# Pinscape_Pico_-_Pro_SMD_Expansion_Board.net
KiCad netlist of a schematic drawn in EAGLE
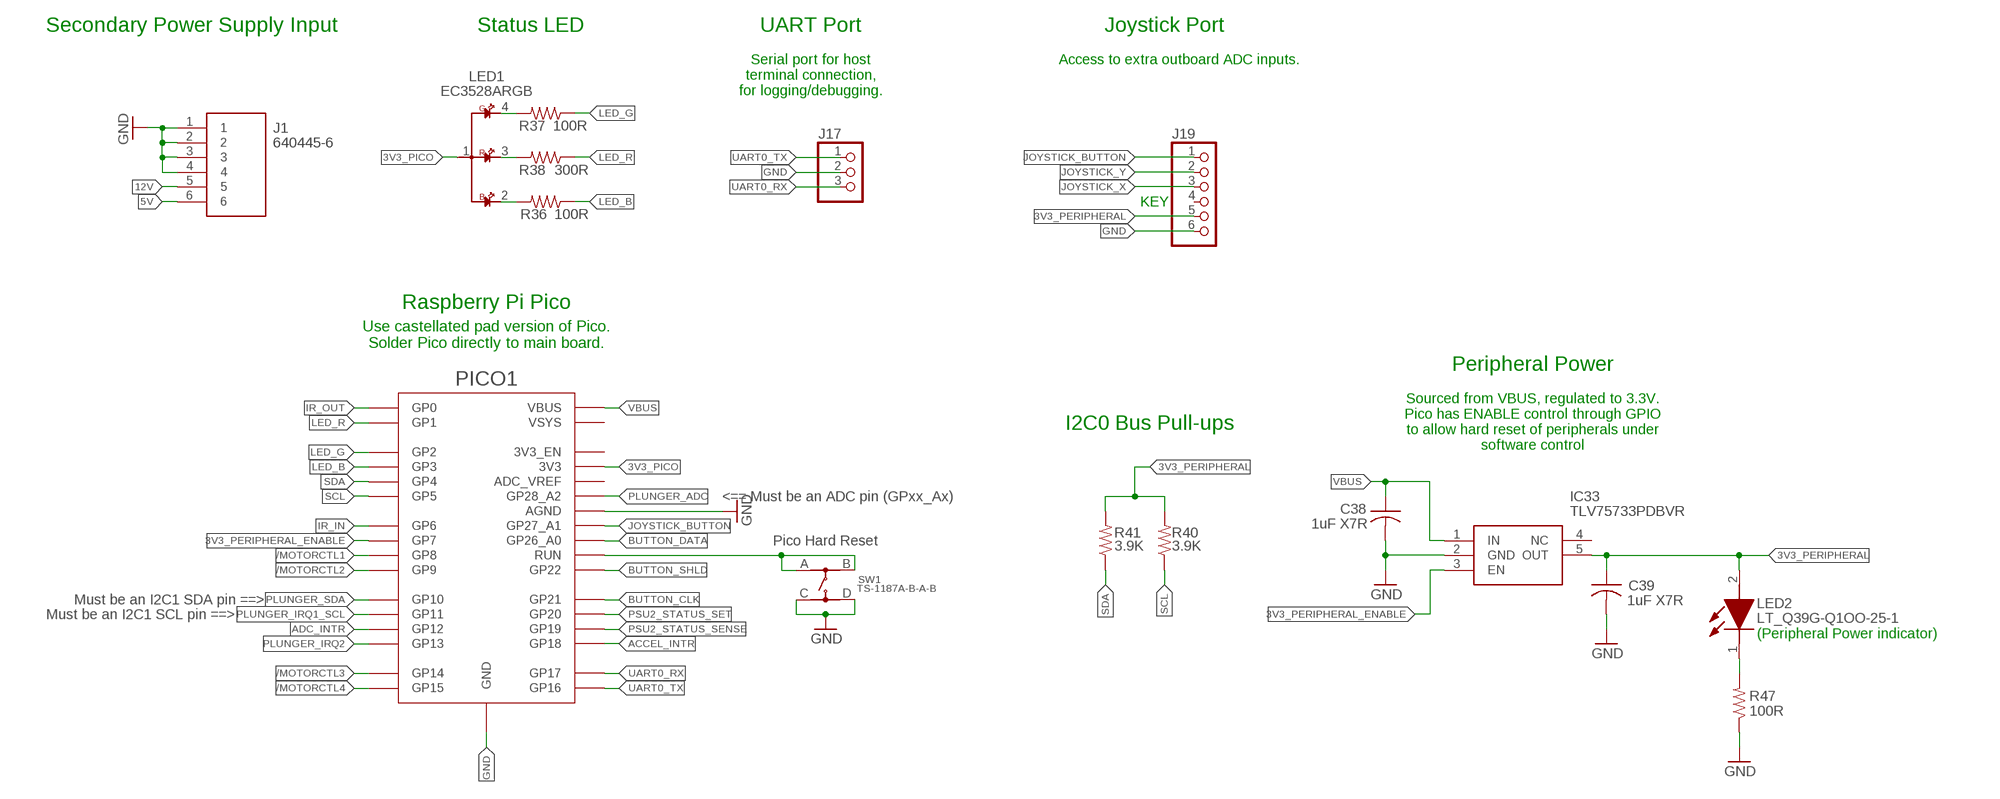
[diagram p0: schematic, sheet 1]
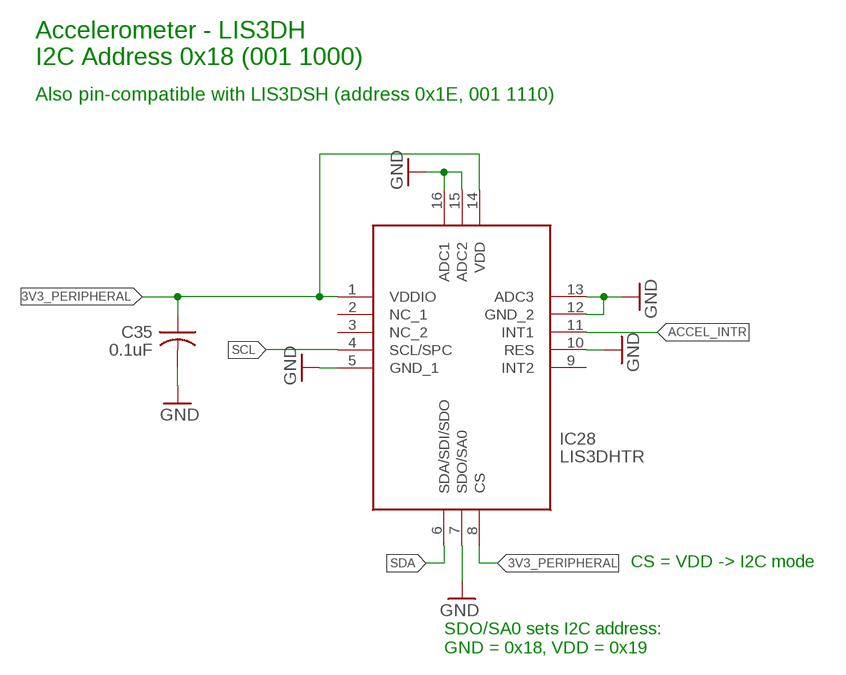
[diagram p1: schematic, sheet 2]
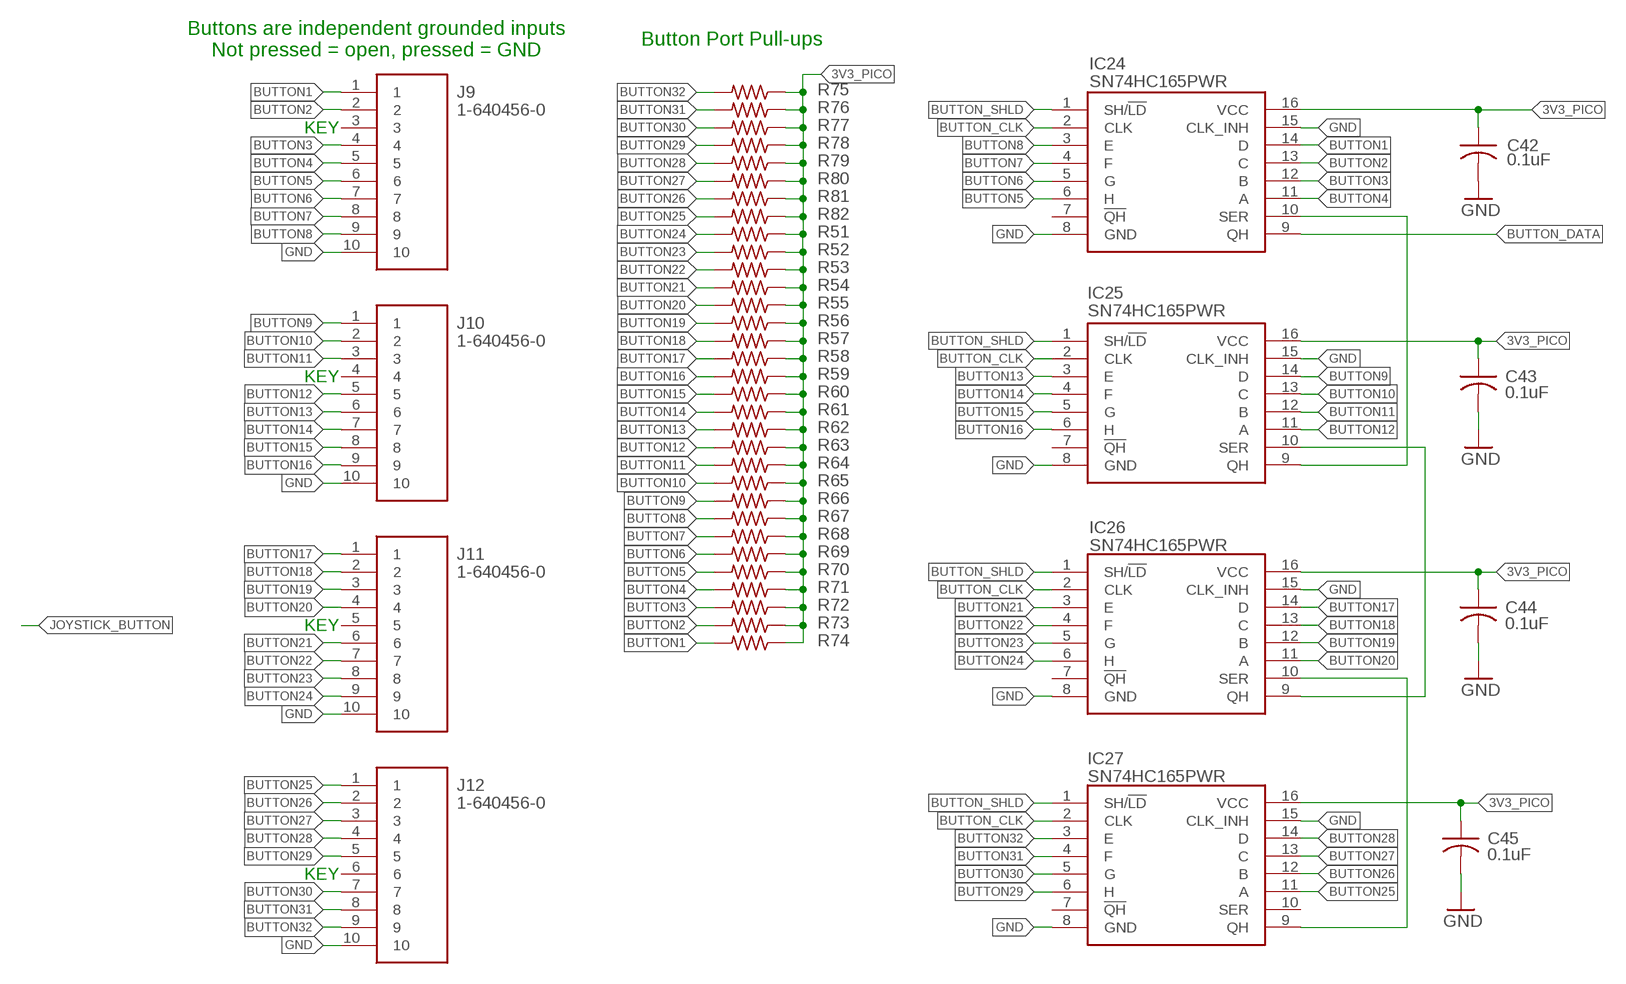
[diagram p2: schematic, sheet 3]
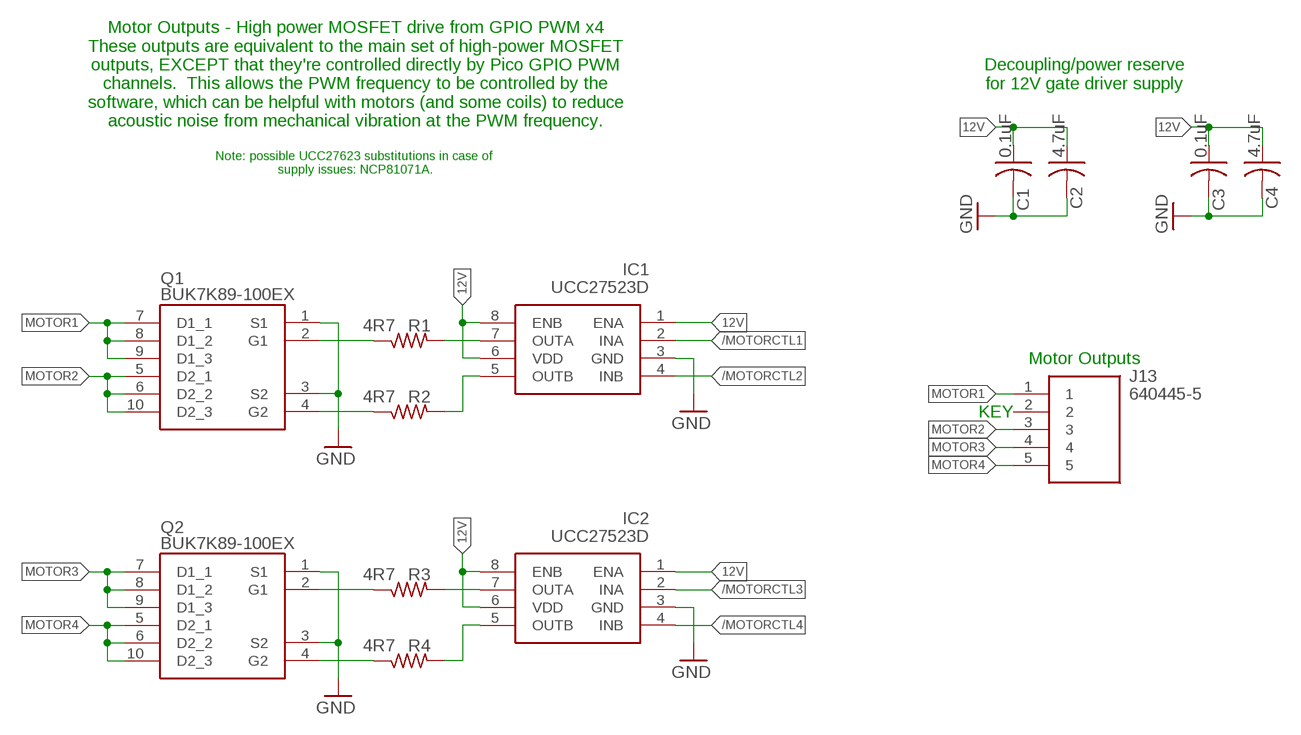
[diagram p3: schematic, sheet 4]
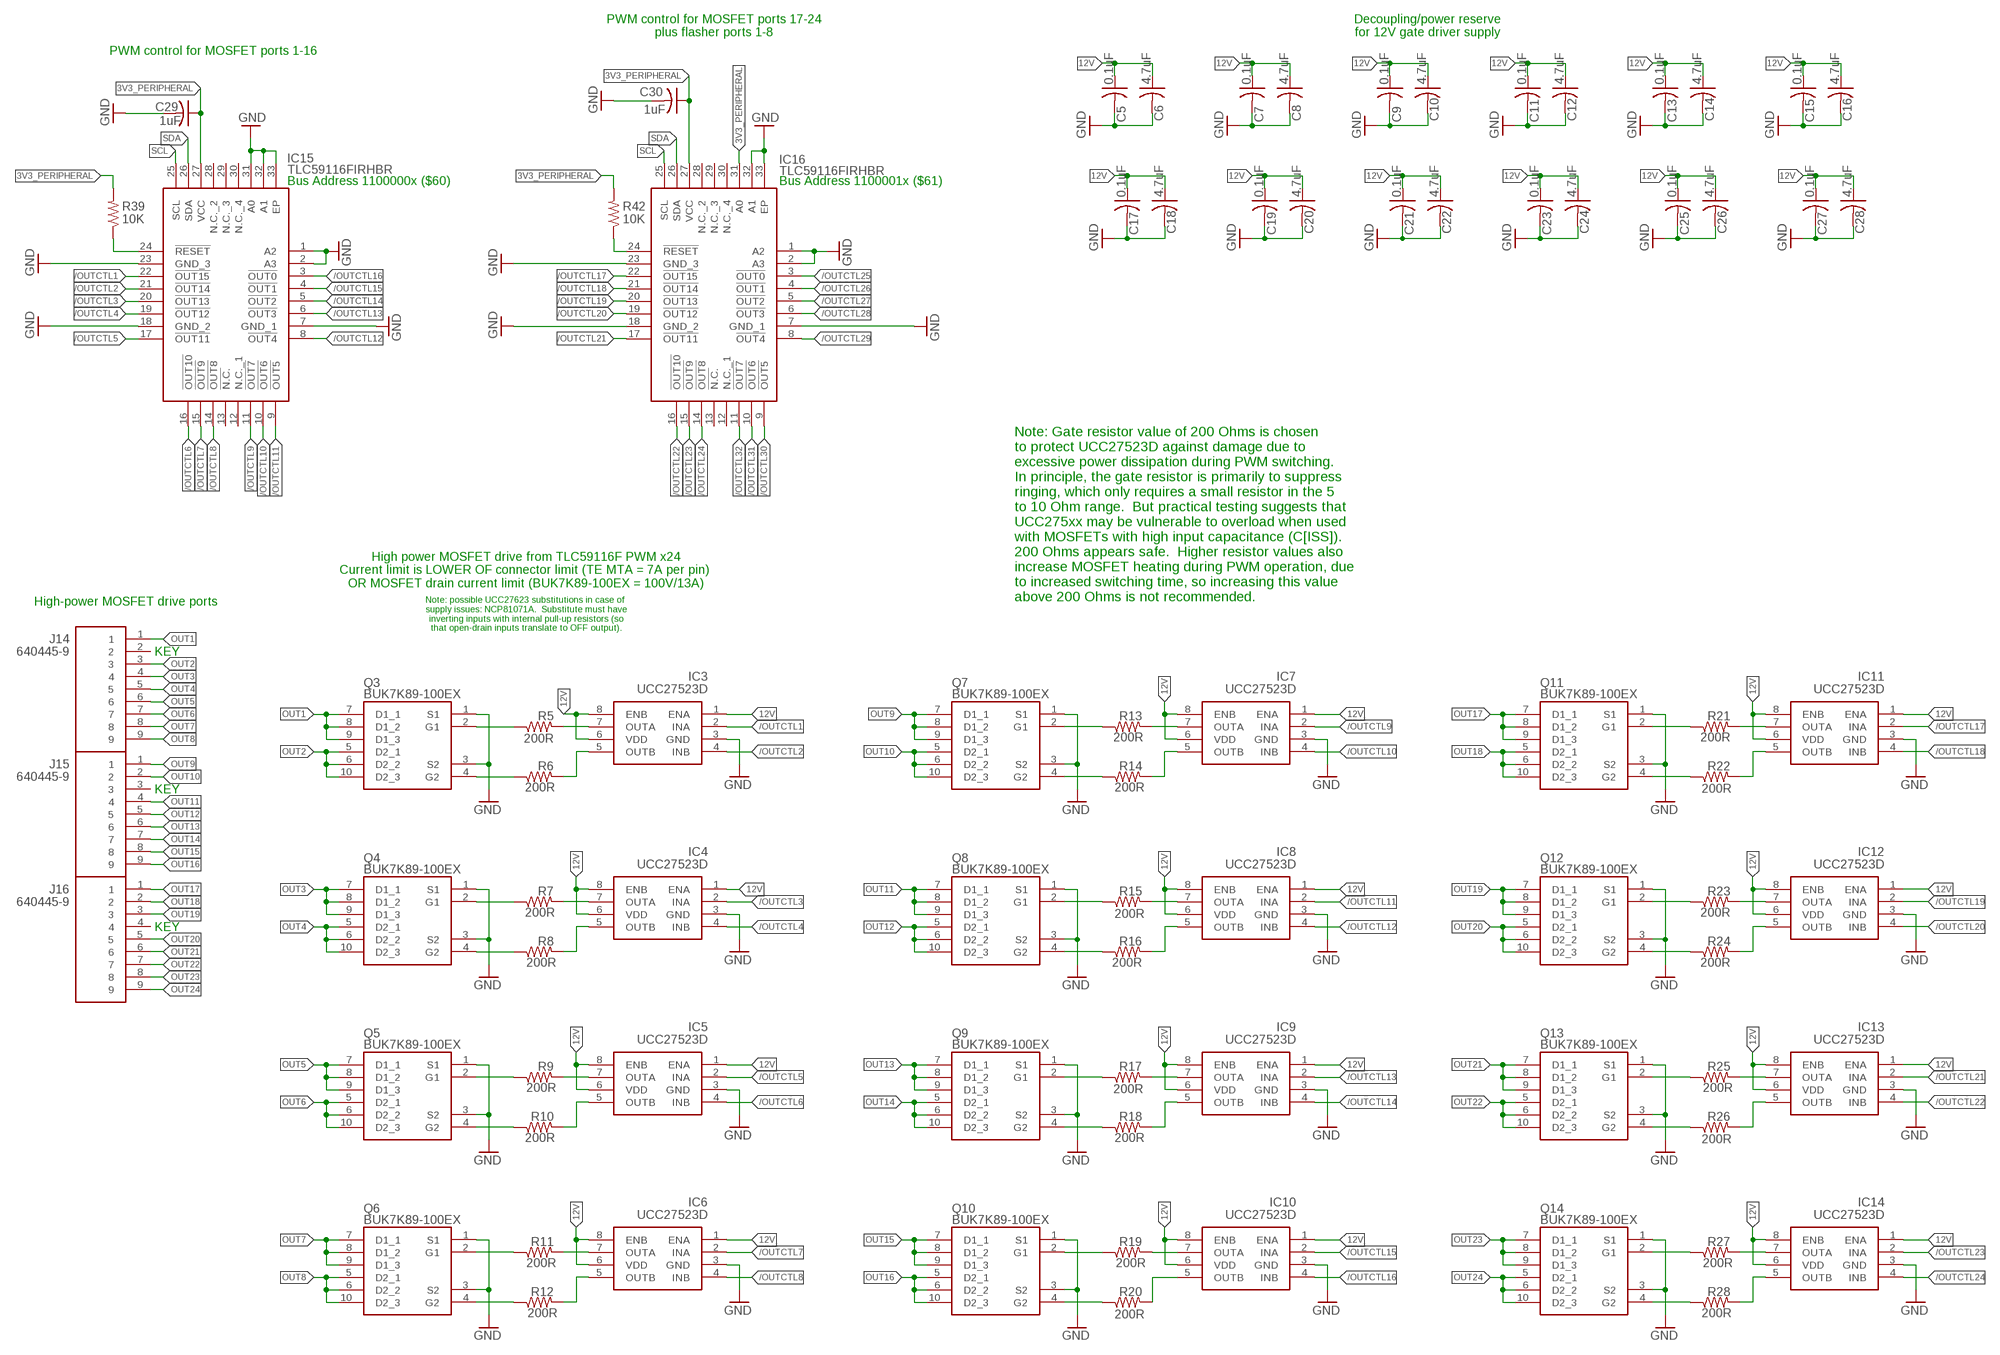
[diagram p4: schematic, sheet 5]
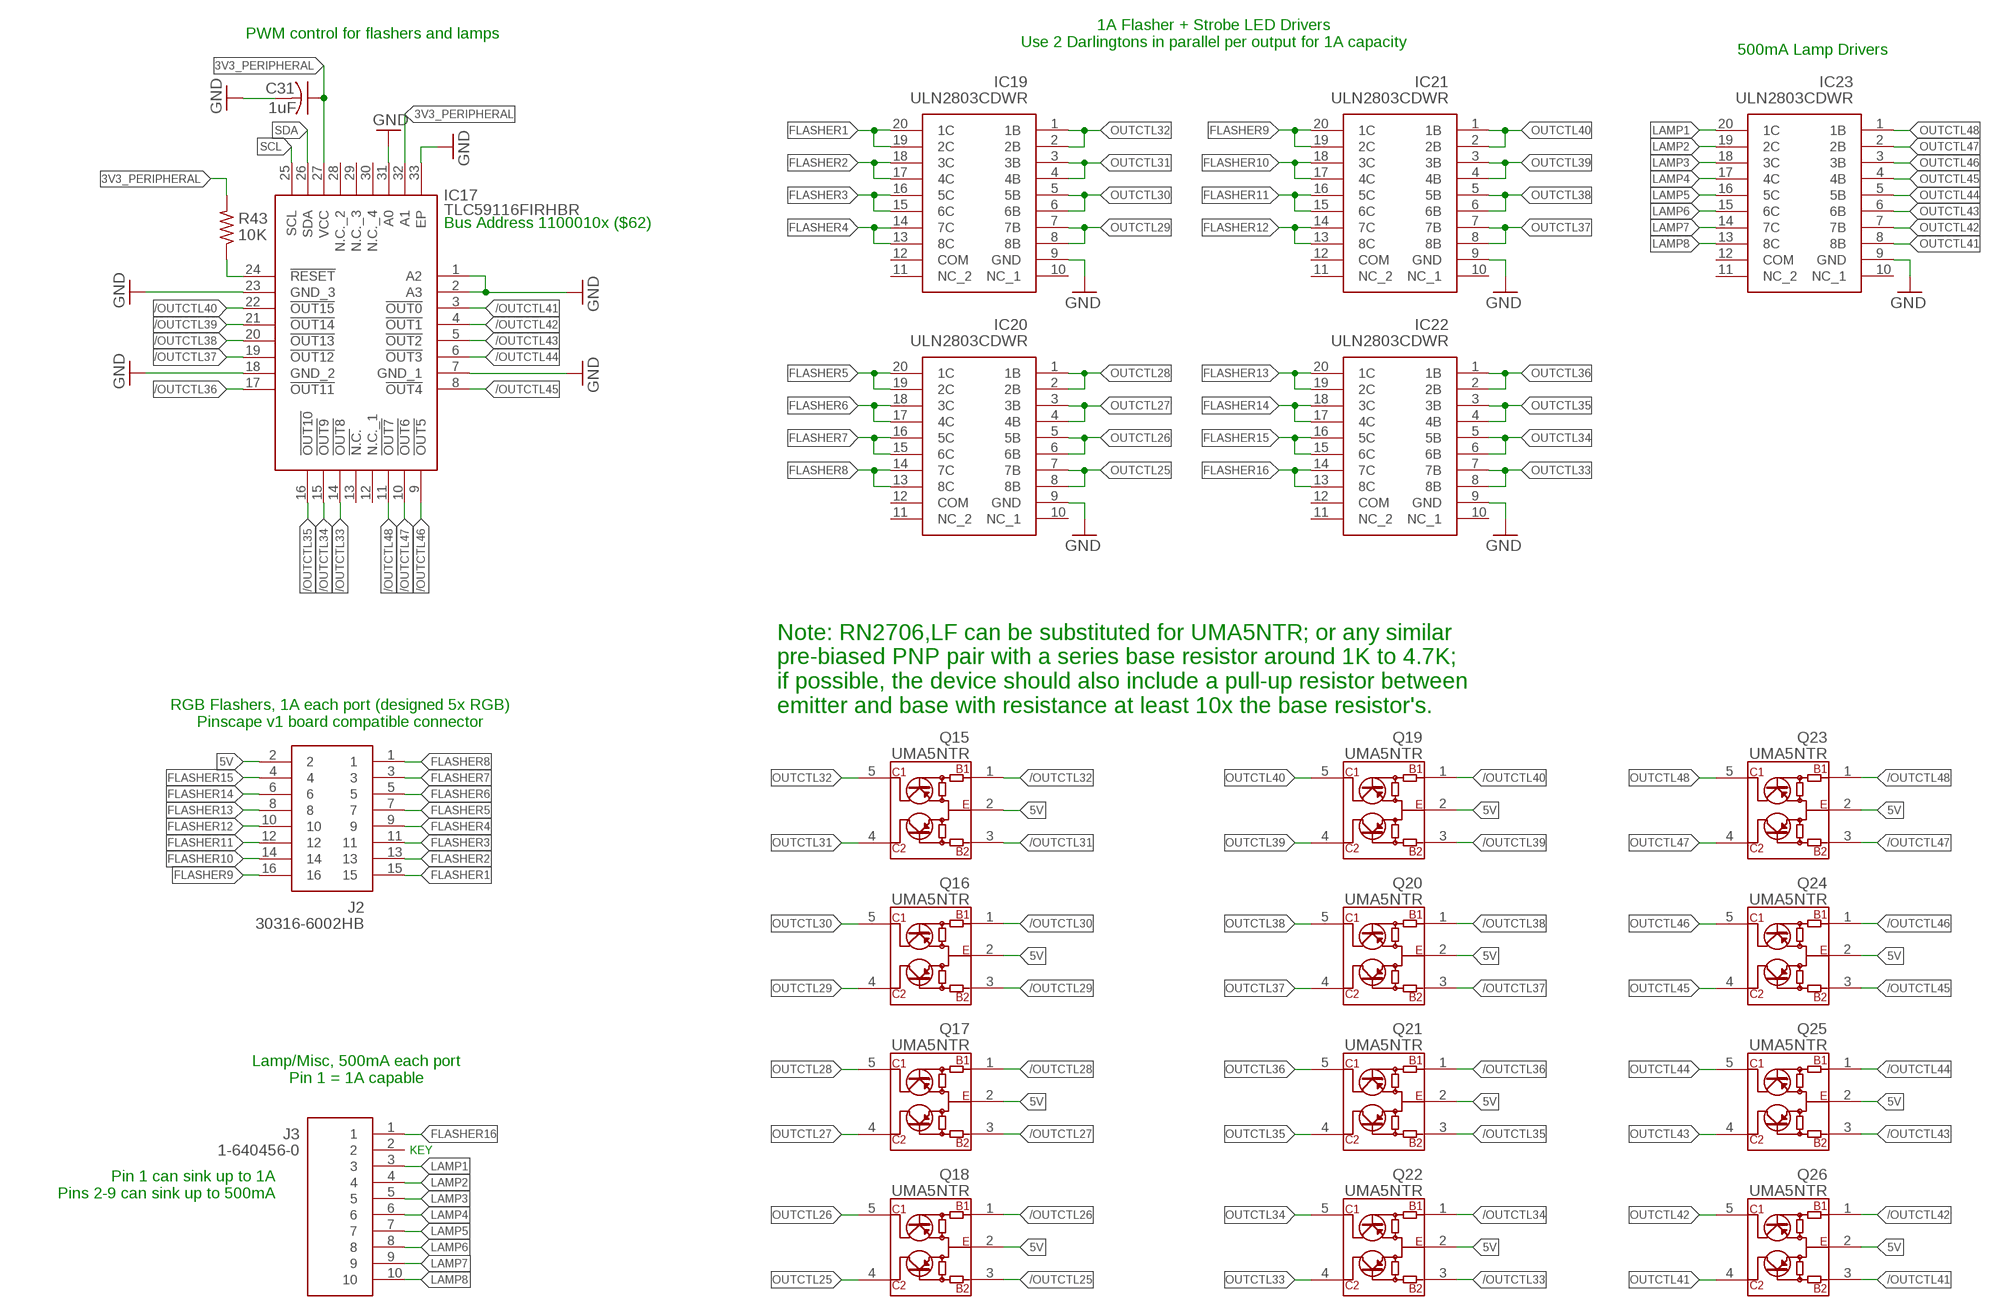
[diagram p5: schematic, sheet 6]
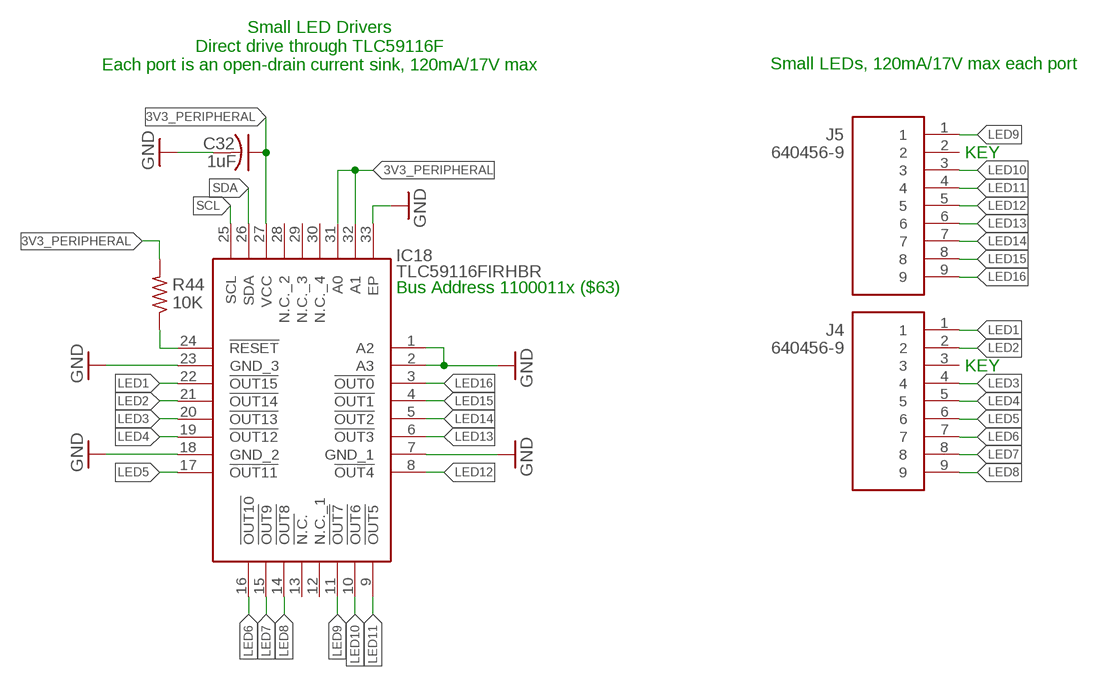
[diagram p6: schematic, sheet 7]
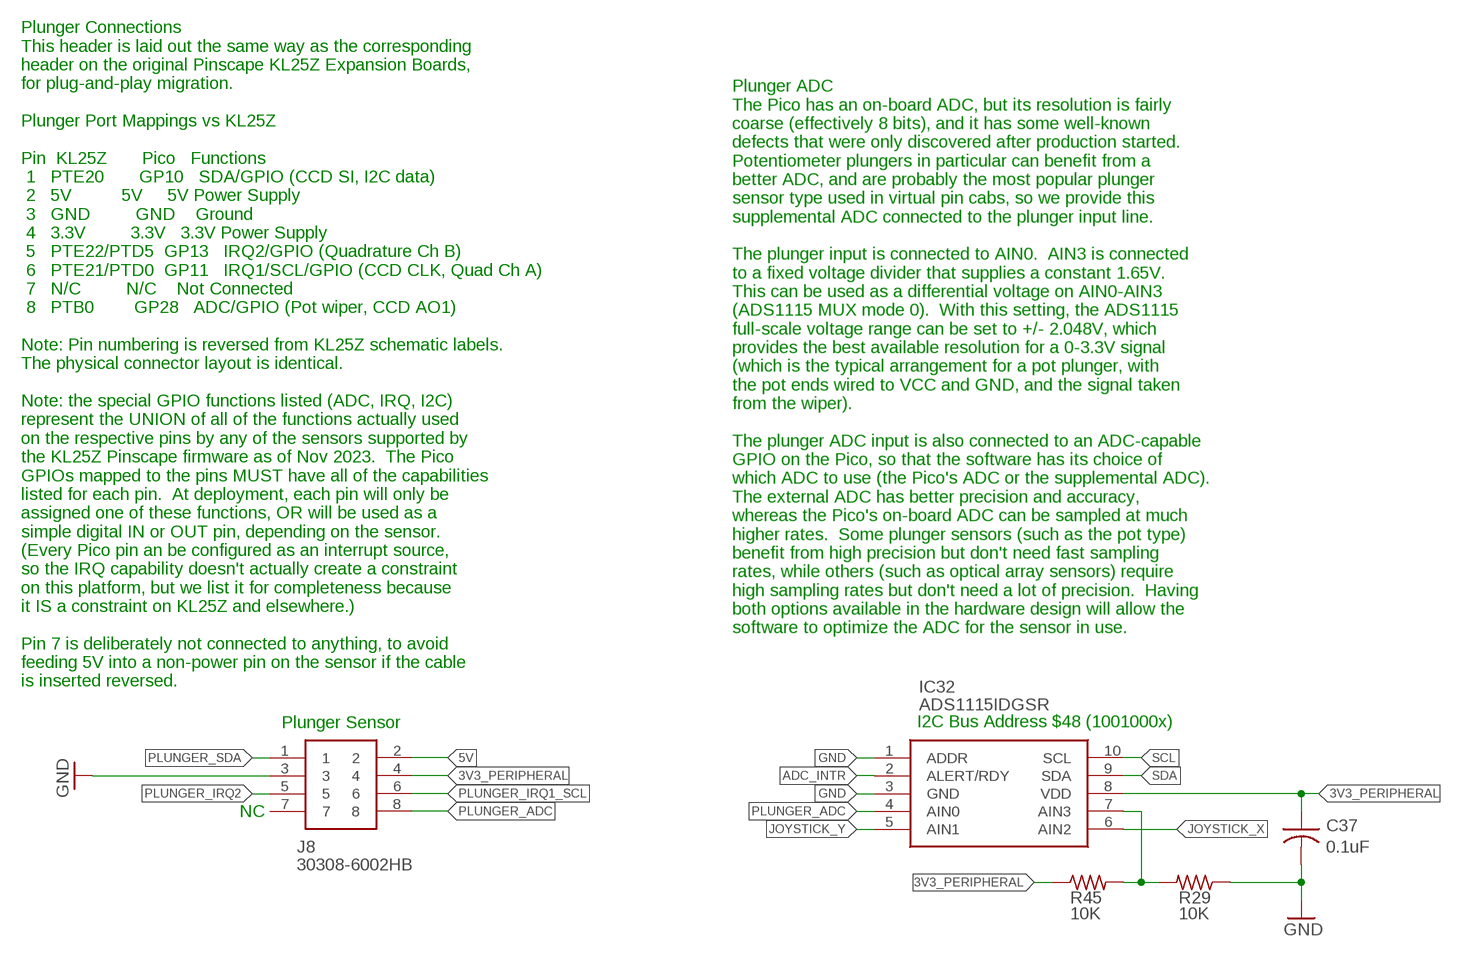
[diagram p7: schematic, sheet 8]
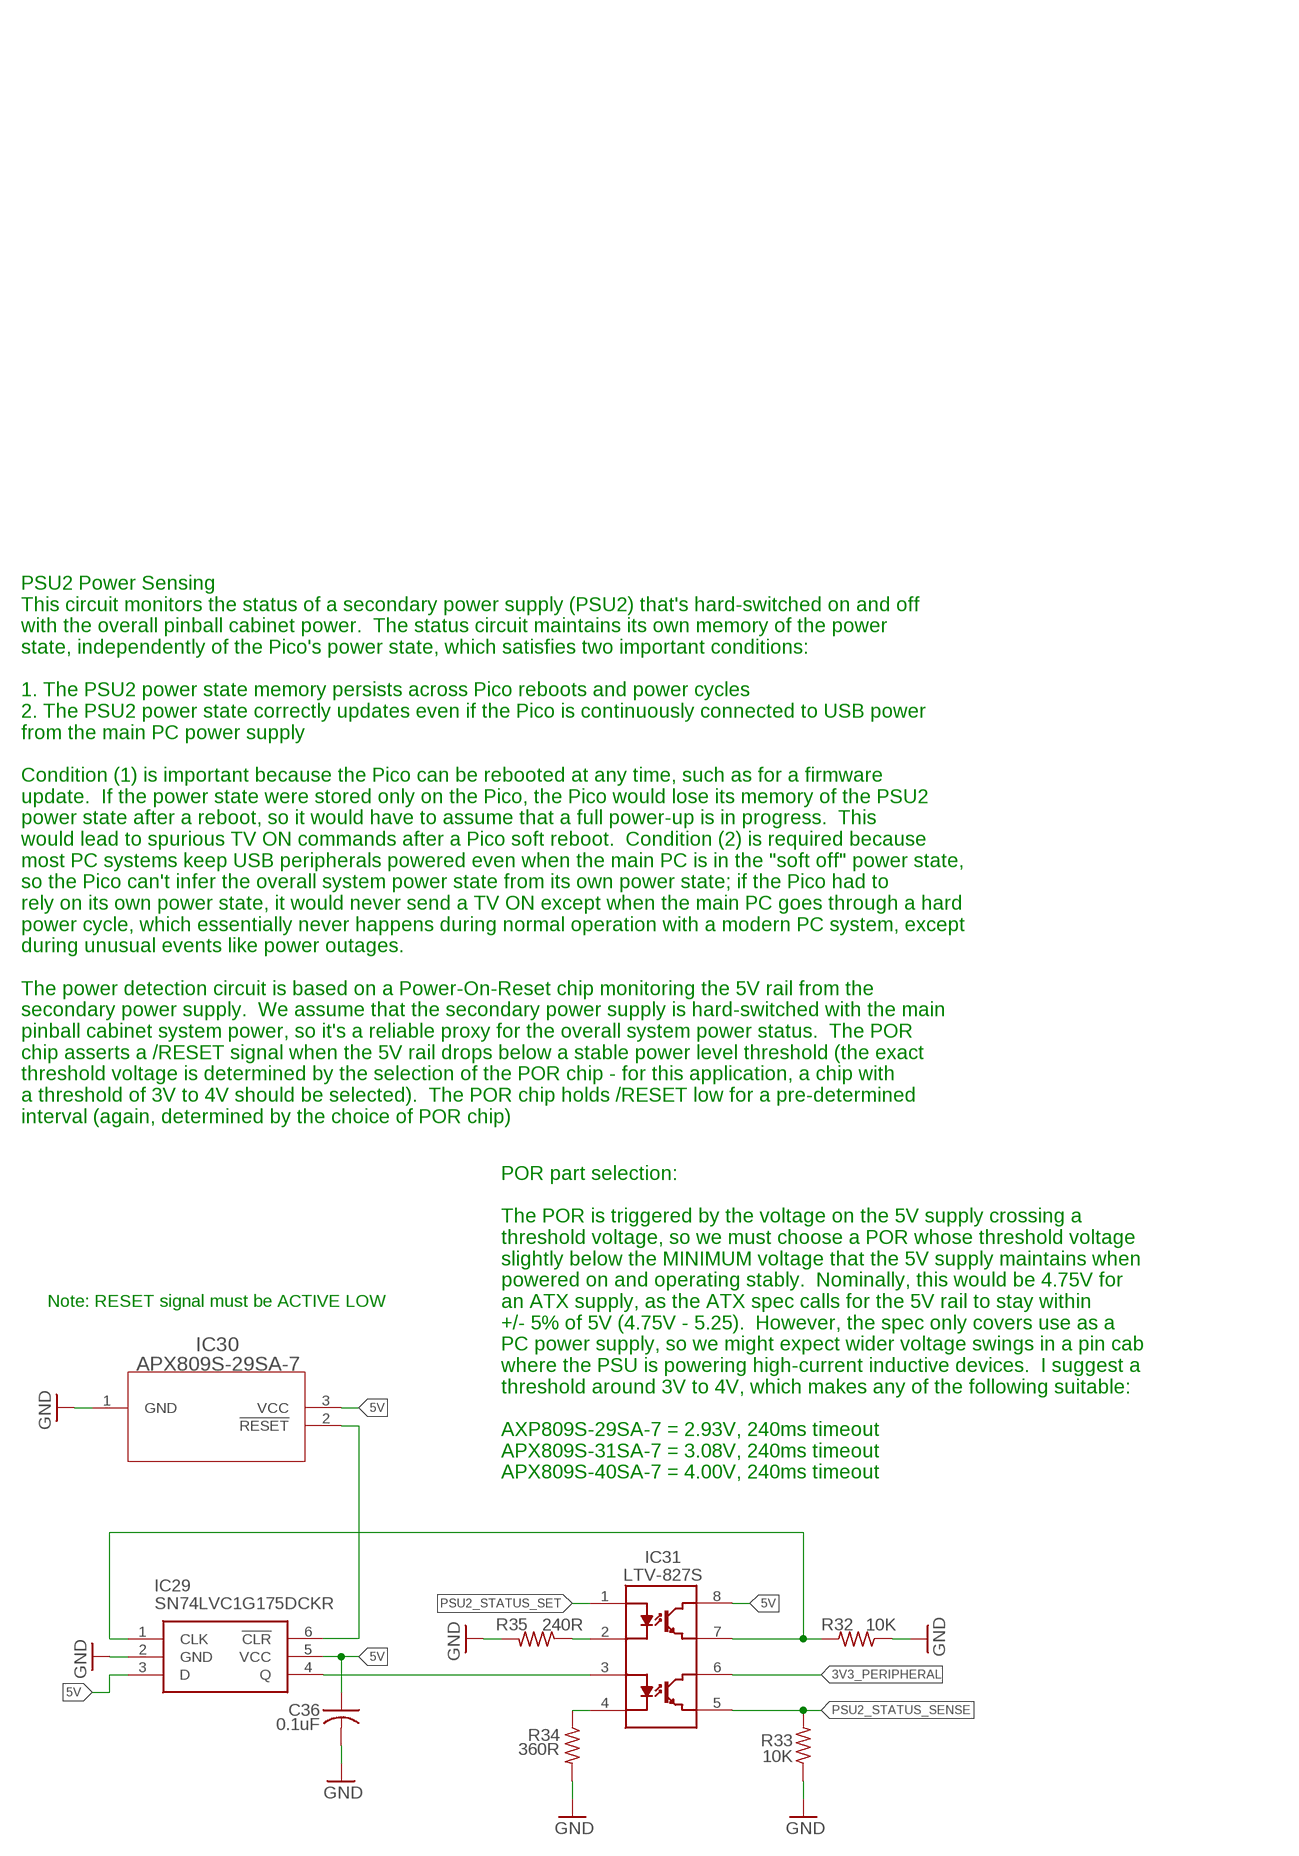
[diagram p8: schematic, sheet 9]
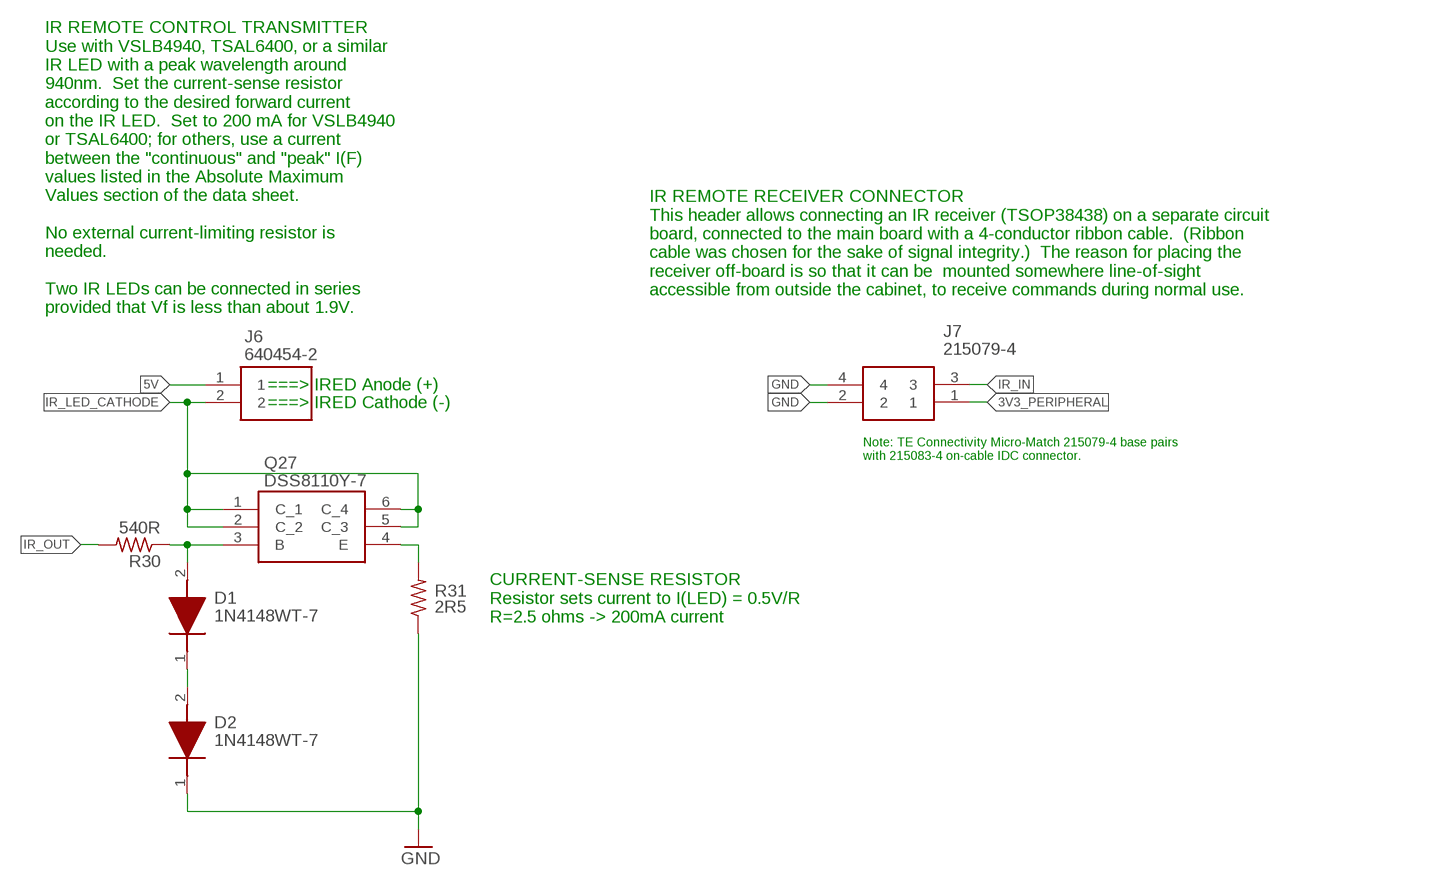
[diagram p9: schematic, sheet 10]
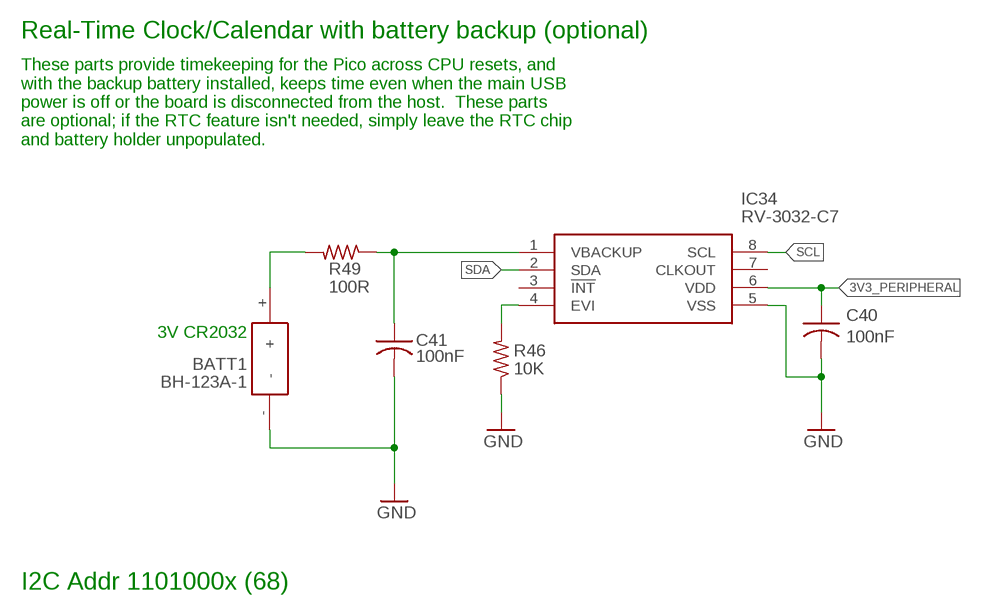
[diagram p10: schematic, sheet 11]
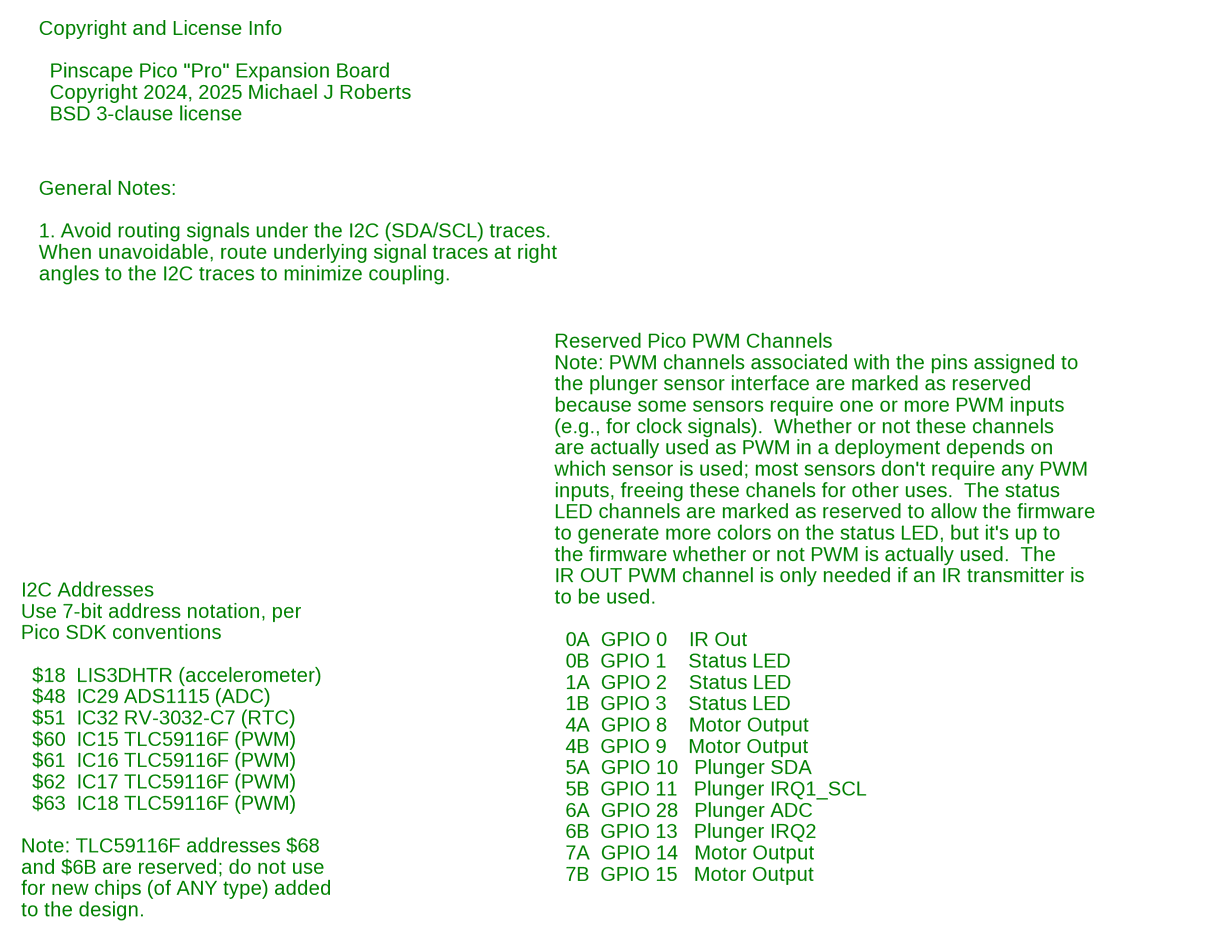
[diagram p11: schematic, sheet 12]

(export (version "E")
  (design (tool "Eeschema 10.0.6"))
  (components
    (comp (ref "C31")
      (value "1uF")
      (footprint "eagle-import:C0402")
      (libsource (lib "eagle-import") (part "C-USC0402"))
    )
    (comp (ref "IC17")
      (value "TLC59116FIRHBR")
      (footprint "eagle-import:QFN50P500X500X100-33N")
      (fields (field (name "MOUSER_PART_NUMBER") "595-TLC59116FIRHBR"))
      (libsource (lib "eagle-import") (part "TLC59116FIRHBR"))
    )
    (comp (ref "IC19")
      (value "ULN2803CDWR")
      (footprint "eagle-import:SOIC127P1030X265-20N")
      (fields (field (name "MOUSER_PART_NUMBER") "595-ULN2803CDWR"))
      (libsource (lib "eagle-import") (part "ULN2803CDWR"))
    )
    (comp (ref "IC20")
      (value "ULN2803CDWR")
      (footprint "eagle-import:SOIC127P1030X265-20N")
      (fields (field (name "MOUSER_PART_NUMBER") "595-ULN2803CDWR"))
      (libsource (lib "eagle-import") (part "ULN2803CDWR"))
    )
    (comp (ref "IC21")
      (value "ULN2803CDWR")
      (footprint "eagle-import:SOIC127P1030X265-20N")
      (fields (field (name "MOUSER_PART_NUMBER") "595-ULN2803CDWR"))
      (libsource (lib "eagle-import") (part "ULN2803CDWR"))
    )
    (comp (ref "IC22")
      (value "ULN2803CDWR")
      (footprint "eagle-import:SOIC127P1030X265-20N")
      (fields (field (name "MOUSER_PART_NUMBER") "595-ULN2803CDWR"))
      (libsource (lib "eagle-import") (part "ULN2803CDWR"))
    )
    (comp (ref "IC23")
      (value "ULN2803CDWR")
      (footprint "eagle-import:SOIC127P1030X265-20N")
      (fields (field (name "MOUSER_PART_NUMBER") "595-ULN2803CDWR"))
      (libsource (lib "eagle-import") (part "ULN2803CDWR"))
    )
    (comp (ref "J2")
      (value "30316-6002HB")
      (footprint "eagle-import:3M-30316-6002HB")
      (fields (field (name "MOUSER_PART_NUMBER") "517-30316-6002"))
      (libsource (lib "eagle-import") (part "30316-6002HB"))
    )
    (comp (ref "J3")
      (value "1-640456-0")
      (footprint "eagle-import:SHDR10W66P0X254_1X10_2540X572X")
      (fields (field (name "MOUSER_PART_NUMBER") "571-16404560"))
      (libsource (lib "eagle-import") (part "1-640456-0"))
    )
    (comp (ref "Q15")
      (value "UMA5NTR")
      (footprint "eagle-import:SOT65P210X100-5N")
      (fields (field (name "MOUSER_PART_NUMBER") "755-UMA5NTR"))
      (libsource (lib "eagle-import") (part "UMA5NTR"))
    )
    (comp (ref "Q16")
      (value "UMA5NTR")
      (footprint "eagle-import:SOT65P210X100-5N")
      (fields (field (name "MOUSER_PART_NUMBER") "755-UMA5NTR"))
      (libsource (lib "eagle-import") (part "UMA5NTR"))
    )
    (comp (ref "Q17")
      (value "UMA5NTR")
      (footprint "eagle-import:SOT65P210X100-5N")
      (fields (field (name "MOUSER_PART_NUMBER") "755-UMA5NTR"))
      (libsource (lib "eagle-import") (part "UMA5NTR"))
    )
    (comp (ref "Q18")
      (value "UMA5NTR")
      (footprint "eagle-import:SOT65P210X100-5N")
      (fields (field (name "MOUSER_PART_NUMBER") "755-UMA5NTR"))
      (libsource (lib "eagle-import") (part "UMA5NTR"))
    )
    (comp (ref "Q19")
      (value "UMA5NTR")
      (footprint "eagle-import:SOT65P210X100-5N")
      (fields (field (name "MOUSER_PART_NUMBER") "755-UMA5NTR"))
      (libsource (lib "eagle-import") (part "UMA5NTR"))
    )
    (comp (ref "Q20")
      (value "UMA5NTR")
      (footprint "eagle-import:SOT65P210X100-5N")
      (fields (field (name "MOUSER_PART_NUMBER") "755-UMA5NTR"))
      (libsource (lib "eagle-import") (part "UMA5NTR"))
    )
    (comp (ref "Q21")
      (value "UMA5NTR")
      (footprint "eagle-import:SOT65P210X100-5N")
      (fields (field (name "MOUSER_PART_NUMBER") "755-UMA5NTR"))
      (libsource (lib "eagle-import") (part "UMA5NTR"))
    )
    (comp (ref "Q22")
      (value "UMA5NTR")
      (footprint "eagle-import:SOT65P210X100-5N")
      (fields (field (name "MOUSER_PART_NUMBER") "755-UMA5NTR"))
      (libsource (lib "eagle-import") (part "UMA5NTR"))
    )
    (comp (ref "Q23")
      (value "UMA5NTR")
      (footprint "eagle-import:SOT65P210X100-5N")
      (fields (field (name "MOUSER_PART_NUMBER") "755-UMA5NTR"))
      (libsource (lib "eagle-import") (part "UMA5NTR"))
    )
    (comp (ref "Q24")
      (value "UMA5NTR")
      (footprint "eagle-import:SOT65P210X100-5N")
      (fields (field (name "MOUSER_PART_NUMBER") "755-UMA5NTR"))
      (libsource (lib "eagle-import") (part "UMA5NTR"))
    )
    (comp (ref "Q25")
      (value "UMA5NTR")
      (footprint "eagle-import:SOT65P210X100-5N")
      (fields (field (name "MOUSER_PART_NUMBER") "755-UMA5NTR"))
      (libsource (lib "eagle-import") (part "UMA5NTR"))
    )
    (comp (ref "Q26")
      (value "UMA5NTR")
      (footprint "eagle-import:SOT65P210X100-5N")
      (fields (field (name "MOUSER_PART_NUMBER") "755-UMA5NTR"))
      (libsource (lib "eagle-import") (part "UMA5NTR"))
    )
    (comp (ref "R43")
      (value "10K")
      (footprint "eagle-import:R0402")
      (libsource (lib "eagle-import") (part "resistor_R-US_R0402"))
    )
    (comp (ref "D1")
      (value "1N4148WT-7")
      (footprint "eagle-import:1N4148WT7")
      (fields (field (name "MOUSER_PART_NUMBER") "621-1N4148WT"))
      (libsource (lib "eagle-import") (part "1N4148WT-7"))
    )
    (comp (ref "D2")
      (value "1N4148WT-7")
      (footprint "eagle-import:1N4148WT7")
      (fields (field (name "MOUSER_PART_NUMBER") "621-1N4148WT"))
      (libsource (lib "eagle-import") (part "1N4148WT-7"))
    )
    (comp (ref "J6")
      (value "640454-2")
      (footprint "eagle-import:HDRV2W66P0X254_1X2_762X572X100")
      (fields (field (name "MOUSER_PART_NUMBER") "571-640454-2"))
      (libsource (lib "eagle-import") (part "640454-2"))
    )
    (comp (ref "J7")
      (value "215079-4")
      (footprint "eagle-import:2150794")
      (fields (field (name "MOUSER_PART_NUMBER") "571-215079-4"))
      (libsource (lib "eagle-import") (part "215079-4"))
    )
    (comp (ref "Q27")
      (value "DSS8110Y-7")
      (footprint "eagle-import:SOT65P210X110-6N")
      (fields (field (name "MOUSER_PART_NUMBER") "621-DSS8110Y-7"))
      (libsource (lib "eagle-import") (part "DSS8110Y-7"))
    )
    (comp (ref "R30")
      (value "540R")
      (footprint "eagle-import:R0402")
      (libsource (lib "eagle-import") (part "resistor_R-US_R0402"))
    )
    (comp (ref "R31")
      (value "2R5")
      (footprint "eagle-import:R0603")
      (libsource (lib "eagle-import") (part "R-US_R0603"))
    )
    (comp (ref "C37")
      (value "0.1uF")
      (footprint "eagle-import:C0402")
      (libsource (lib "eagle-import") (part "C-USC0402"))
    )
    (comp (ref "IC32")
      (value "ADS1115IDGSR")
      (footprint "eagle-import:SOP50P490X110-10N")
      (fields (field (name "MOUSER_PART_NUMBER") "595-ADS1115IDGSR"))
      (libsource (lib "eagle-import") (part "ADS1115IDGSR"))
    )
    (comp (ref "J8")
      (value "30308-6002HB")
      (footprint "eagle-import:SHDR8W69P254_2X4_1780X878X955P")
      (libsource (lib "eagle-import") (part "30308-6002HB"))
    )
    (comp (ref "R29")
      (value "10K")
      (footprint "eagle-import:R0603")
      (libsource (lib "eagle-import") (part "resistor_R-US_R0603"))
    )
    (comp (ref "R45")
      (value "10K")
      (footprint "eagle-import:R0603")
      (libsource (lib "eagle-import") (part "resistor_R-US_R0603"))
    )
    (comp (ref "C36")
      (value "0.1uF")
      (footprint "eagle-import:C0402")
      (libsource (lib "eagle-import") (part "C-USC0402"))
    )
    (comp (ref "IC29")
      (value "SN74LVC1G175DCKR")
      (footprint "eagle-import:SOP65P210X110-6N")
      (fields (field (name "MOUSER_PART_NUMBER") "595-SN74LVC1G175DCKR"))
      (libsource (lib "eagle-import") (part "SN74LVC1G175DCKR"))
    )
    (comp (ref "IC30")
      (value "APX809S-29SA-7")
      (footprint "eagle-import:SOT23_DIO")
      (fields
        (field (name "MANUFACTURER_PART_NUMBER") "APX809S-40SA-7")
        (field (name "MANUFACTURER_PART_NUMBER_1") "APX809S-40SA-7")
        (field (name "COPYRIGHT") "Copyright (C) 2023 Ultra Librarian. All rights reserved.")
      )
      (libsource (lib "eagle-import") (part "APX809S-40SA-7"))
    )
    (comp (ref "IC31")
      (value "LTV-827S")
      (footprint "eagle-import:SOP254P1016X460-8N")
      (fields (field (name "MOUSER_PART_NUMBER") "859-LTV-827S"))
      (libsource (lib "eagle-import") (part "LTV-827S"))
    )
    (comp (ref "R32")
      (value "10K")
      (footprint "eagle-import:R0402")
      (fields (field (name "PARTNO") "660-MS1/4DCT52R1002"))
      (libsource (lib "eagle-import") (part "resistor_R-US_R0402"))
    )
    (comp (ref "R33")
      (value "10K")
      (footprint "eagle-import:R0402")
      (fields (field (name "PARTNO") "660-MS1/4DCT52R1002"))
      (libsource (lib "eagle-import") (part "resistor_R-US_R0402"))
    )
    (comp (ref "R34")
      (value "360R")
      (footprint "eagle-import:R0402")
      (fields (field (name "PARTNO") "660-MS1/4DCT52R1002"))
      (libsource (lib "eagle-import") (part "resistor_R-US_R0402"))
    )
    (comp (ref "R35")
      (value "240R")
      (footprint "eagle-import:R0402")
      (fields (field (name "PARTNO") "594-SFR16S0005600FR5"))
      (libsource (lib "eagle-import") (part "resistor_R-US_R0402"))
    )
    (comp (ref "BATT1")
      (value "BH-123A-1")
      (footprint "eagle-import:BH-123A-1")
      (libsource (lib "eagle-import") (part "BH-123A-1"))
    )
    (comp (ref "C40")
      (value "100nF")
      (footprint "eagle-import:C0402")
      (libsource (lib "eagle-import") (part "C-USC0402"))
    )
    (comp (ref "C41")
      (value "100nF")
      (footprint "eagle-import:C0402")
      (libsource (lib "eagle-import") (part "C-USC0402"))
    )
    (comp (ref "IC34")
      (value "RV-3032-C7")
      (footprint "eagle-import:RV3032C7")
      (fields (field (name "MANUFACTURER_PART_NUMBER") "RV-3032-C7 32.768KHZ-2.5PPM-TA-QC"))
      (libsource (lib "eagle-import") (part "RV-3032-C7_32.768KHZ-2.5PPM-TA"))
    )
    (comp (ref "R46")
      (value "10K")
      (footprint "eagle-import:R0402")
      (libsource (lib "eagle-import") (part "resistor_R-US_R0402"))
    )
    (comp (ref "R49")
      (value "100R")
      (footprint "eagle-import:R0402")
      (libsource (lib "eagle-import") (part "resistor_R-US_R0402"))
    )
    (comp (ref "C1")
      (value "0.1uF")
      (footprint "eagle-import:C0402")
      (libsource (lib "eagle-import") (part "resistor_C-USC0402"))
    )
    (comp (ref "C2")
      (value "4.7uF")
      (footprint "eagle-import:C1206")
      (libsource (lib "eagle-import") (part "resistor_C-USC1206"))
    )
    (comp (ref "C3")
      (value "0.1uF")
      (footprint "eagle-import:C0402")
      (libsource (lib "eagle-import") (part "resistor_C-USC0402"))
    )
    (comp (ref "C4")
      (value "4.7uF")
      (footprint "eagle-import:C1206")
      (libsource (lib "eagle-import") (part "resistor_C-USC1206"))
    )
    (comp (ref "IC1")
      (value "UCC27523D")
      (footprint "eagle-import:SOIC127P600X175-8N")
      (fields
        (field (name "MANUFACTURER_PART_NUMBER") "UCC27523DR")
        (field (name "MOUSER_PART_NUMBER") "595-UCC27523DR")
      )
      (libsource (lib "eagle-import") (part "UCC27523DR"))
    )
    (comp (ref "IC2")
      (value "UCC27523D")
      (footprint "eagle-import:SOIC127P600X175-8N")
      (fields
        (field (name "MANUFACTURER_PART_NUMBER") "UCC27523DR")
        (field (name "MOUSER_PART_NUMBER") "595-UCC27523DR")
      )
      (libsource (lib "eagle-import") (part "UCC27523DR"))
    )
    (comp (ref "J13")
      (value "640445-5")
      (footprint "eagle-import:HDRV5W117P0X396_1X5_1981X762X1")
      (fields (field (name "MOUSER_PART_NUMBER") "571-640445-5"))
      (libsource (lib "eagle-import") (part "640445-5"))
    )
    (comp (ref "Q1")
      (value "BUK7K89-100EX")
      (footprint "eagle-import:BUK7K89100EX")
      (fields (field (name "MOUSER_PART_NUMBER") "771-BUK7K89-100EX"))
      (libsource (lib "eagle-import") (part "BUK7K89-100EX"))
    )
    (comp (ref "Q2")
      (value "BUK7K89-100EX")
      (footprint "eagle-import:BUK7K89100EX")
      (fields (field (name "MOUSER_PART_NUMBER") "771-BUK7K89-100EX"))
      (libsource (lib "eagle-import") (part "BUK7K89-100EX"))
    )
    (comp (ref "R1")
      (value "4R7")
      (footprint "eagle-import:R0603")
      (libsource (lib "eagle-import") (part "resistor_R-US_R0603"))
    )
    (comp (ref "R2")
      (value "4R7")
      (footprint "eagle-import:R0603")
      (libsource (lib "eagle-import") (part "resistor_R-US_R0603"))
    )
    (comp (ref "R3")
      (value "4R7")
      (footprint "eagle-import:R0603")
      (libsource (lib "eagle-import") (part "resistor_R-US_R0603"))
    )
    (comp (ref "R4")
      (value "4R7")
      (footprint "eagle-import:R0603")
      (libsource (lib "eagle-import") (part "resistor_R-US_R0603"))
    )
    (comp (ref "C42")
      (value "0.1uF")
      (footprint "eagle-import:C0402")
      (libsource (lib "eagle-import") (part "C-USC0402"))
    )
    (comp (ref "C43")
      (value "0.1uF")
      (footprint "eagle-import:C0402")
      (libsource (lib "eagle-import") (part "C-USC0402"))
    )
    (comp (ref "C44")
      (value "0.1uF")
      (footprint "eagle-import:C0402")
      (libsource (lib "eagle-import") (part "C-USC0402"))
    )
    (comp (ref "C45")
      (value "0.1uF")
      (footprint "eagle-import:C0402")
      (libsource (lib "eagle-import") (part "C-USC0402"))
    )
    (comp (ref "IC24")
      (value "SN74HC165PWR")
      (footprint "eagle-import:SOP65P640X120-16N")
      (fields (field (name "MOUSER_PART_NUMBER") "595-SN74HC165PWR"))
      (libsource (lib "eagle-import") (part "SN74HC165PWR"))
    )
    (comp (ref "IC25")
      (value "SN74HC165PWR")
      (footprint "eagle-import:SOP65P640X120-16N")
      (fields (field (name "MOUSER_PART_NUMBER") "595-SN74HC165PWR"))
      (libsource (lib "eagle-import") (part "SN74HC165PWR"))
    )
    (comp (ref "IC26")
      (value "SN74HC165PWR")
      (footprint "eagle-import:SOP65P640X120-16N")
      (fields (field (name "MOUSER_PART_NUMBER") "595-SN74HC165PWR"))
      (libsource (lib "eagle-import") (part "SN74HC165PWR"))
    )
    (comp (ref "IC27")
      (value "SN74HC165PWR")
      (footprint "eagle-import:SOP65P640X120-16N")
      (fields (field (name "MOUSER_PART_NUMBER") "595-SN74HC165PWR"))
      (libsource (lib "eagle-import") (part "SN74HC165PWR"))
    )
    (comp (ref "J9")
      (value "1-640456-0")
      (footprint "eagle-import:SHDR10W66P0X254_1X10_2540X572X")
      (fields (field (name "MOUSER_PART_NUMBER") "571-16404560"))
      (libsource (lib "eagle-import") (part "1-640456-0"))
    )
    (comp (ref "J10")
      (value "1-640456-0")
      (footprint "eagle-import:SHDR10W66P0X254_1X10_2540X572X")
      (fields (field (name "MOUSER_PART_NUMBER") "571-16404560"))
      (libsource (lib "eagle-import") (part "1-640456-0"))
    )
    (comp (ref "J11")
      (value "1-640456-0")
      (footprint "eagle-import:SHDR10W66P0X254_1X10_2540X572X")
      (fields (field (name "MOUSER_PART_NUMBER") "571-16404560"))
      (libsource (lib "eagle-import") (part "1-640456-0"))
    )
    (comp (ref "J12")
      (value "1-640456-0")
      (footprint "eagle-import:SHDR10W66P0X254_1X10_2540X572X")
      (fields (field (name "MOUSER_PART_NUMBER") "571-16404560"))
      (libsource (lib "eagle-import") (part "1-640456-0"))
    )
    (comp (ref "R51")
      (value "10k")
      (footprint "eagle-import:R0402")
      (libsource (lib "eagle-import") (part "resistor_R-US_R0402"))
    )
    (comp (ref "R52")
      (value "10k")
      (footprint "eagle-import:R0402")
      (libsource (lib "eagle-import") (part "resistor_R-US_R0402"))
    )
    (comp (ref "R53")
      (value "10k")
      (footprint "eagle-import:R0402")
      (libsource (lib "eagle-import") (part "resistor_R-US_R0402"))
    )
    (comp (ref "R54")
      (value "10k")
      (footprint "eagle-import:R0402")
      (libsource (lib "eagle-import") (part "resistor_R-US_R0402"))
    )
    (comp (ref "R55")
      (value "10k")
      (footprint "eagle-import:R0402")
      (libsource (lib "eagle-import") (part "resistor_R-US_R0402"))
    )
    (comp (ref "R56")
      (value "10k")
      (footprint "eagle-import:R0402")
      (libsource (lib "eagle-import") (part "resistor_R-US_R0402"))
    )
    (comp (ref "R57")
      (value "10k")
      (footprint "eagle-import:R0402")
      (libsource (lib "eagle-import") (part "resistor_R-US_R0402"))
    )
    (comp (ref "R58")
      (value "10k")
      (footprint "eagle-import:R0402")
      (libsource (lib "eagle-import") (part "resistor_R-US_R0402"))
    )
    (comp (ref "R59")
      (value "10k")
      (footprint "eagle-import:R0402")
      (libsource (lib "eagle-import") (part "resistor_R-US_R0402"))
    )
    (comp (ref "R60")
      (value "10k")
      (footprint "eagle-import:R0402")
      (libsource (lib "eagle-import") (part "resistor_R-US_R0402"))
    )
    (comp (ref "R61")
      (value "10k")
      (footprint "eagle-import:R0402")
      (libsource (lib "eagle-import") (part "resistor_R-US_R0402"))
    )
    (comp (ref "R62")
      (value "10k")
      (footprint "eagle-import:R0402")
      (libsource (lib "eagle-import") (part "resistor_R-US_R0402"))
    )
    (comp (ref "R63")
      (value "10k")
      (footprint "eagle-import:R0402")
      (libsource (lib "eagle-import") (part "resistor_R-US_R0402"))
    )
    (comp (ref "R64")
      (value "10k")
      (footprint "eagle-import:R0402")
      (libsource (lib "eagle-import") (part "resistor_R-US_R0402"))
    )
    (comp (ref "R65")
      (value "10k")
      (footprint "eagle-import:R0402")
      (libsource (lib "eagle-import") (part "resistor_R-US_R0402"))
    )
    (comp (ref "R66")
      (value "10k")
      (footprint "eagle-import:R0402")
      (libsource (lib "eagle-import") (part "resistor_R-US_R0402"))
    )
    (comp (ref "R67")
      (value "10k")
      (footprint "eagle-import:R0402")
      (libsource (lib "eagle-import") (part "resistor_R-US_R0402"))
    )
    (comp (ref "R68")
      (value "10k")
      (footprint "eagle-import:R0402")
      (libsource (lib "eagle-import") (part "resistor_R-US_R0402"))
    )
    (comp (ref "R69")
      (value "10k")
      (footprint "eagle-import:R0402")
      (libsource (lib "eagle-import") (part "resistor_R-US_R0402"))
    )
    (comp (ref "R70")
      (value "10k")
      (footprint "eagle-import:R0402")
      (libsource (lib "eagle-import") (part "resistor_R-US_R0402"))
    )
    (comp (ref "R71")
      (value "10k")
      (footprint "eagle-import:R0402")
      (libsource (lib "eagle-import") (part "resistor_R-US_R0402"))
    )
    (comp (ref "R72")
      (value "10k")
      (footprint "eagle-import:R0402")
      (libsource (lib "eagle-import") (part "resistor_R-US_R0402"))
    )
    (comp (ref "R73")
      (value "10k")
      (footprint "eagle-import:R0402")
      (libsource (lib "eagle-import") (part "resistor_R-US_R0402"))
    )
    (comp (ref "R74")
      (value "10k")
      (footprint "eagle-import:R0402")
      (libsource (lib "eagle-import") (part "resistor_R-US_R0402"))
    )
    (comp (ref "R75")
      (value "10k")
      (footprint "eagle-import:R0402")
      (libsource (lib "eagle-import") (part "resistor_R-US_R0402"))
    )
    (comp (ref "R76")
      (value "10k")
      (footprint "eagle-import:R0402")
      (libsource (lib "eagle-import") (part "resistor_R-US_R0402"))
    )
    (comp (ref "R77")
      (value "10k")
      (footprint "eagle-import:R0402")
      (libsource (lib "eagle-import") (part "resistor_R-US_R0402"))
    )
    (comp (ref "R78")
      (value "10k")
      (footprint "eagle-import:R0402")
      (libsource (lib "eagle-import") (part "resistor_R-US_R0402"))
    )
    (comp (ref "R79")
      (value "10k")
      (footprint "eagle-import:R0402")
      (libsource (lib "eagle-import") (part "resistor_R-US_R0402"))
    )
    (comp (ref "R80")
      (value "10k")
      (footprint "eagle-import:R0402")
      (libsource (lib "eagle-import") (part "resistor_R-US_R0402"))
    )
    (comp (ref "R81")
      (value "10k")
      (footprint "eagle-import:R0402")
      (libsource (lib "eagle-import") (part "resistor_R-US_R0402"))
    )
    (comp (ref "R82")
      (value "10k")
      (footprint "eagle-import:R0402")
      (libsource (lib "eagle-import") (part "resistor_R-US_R0402"))
    )
    (comp (ref "C35")
      (value "0.1uF")
      (footprint "eagle-import:C0402")
      (libsource (lib "eagle-import") (part "C-USC0402"))
    )
    (comp (ref "IC28")
      (value "LIS3DHTR")
      (footprint "eagle-import:LIS3DHTR")
      (fields (field (name "MOUSER_PART_NUMBER") "511-LIS3DHTR"))
      (libsource (lib "eagle-import") (part "LIS3DHTR"))
    )
    (comp (ref "C38")
      (value "1uF X7R")
      (footprint "eagle-import:C1206")
      (libsource (lib "eagle-import") (part "resistor_C-USC1206"))
    )
    (comp (ref "C39")
      (value "1uF X7R")
      (footprint "eagle-import:C1206")
      (libsource (lib "eagle-import") (part "resistor_C-USC1206"))
    )
    (comp (ref "IC33")
      (value "TLV75733PDBVR")
      (footprint "eagle-import:SOT95P280X145-5N")
      (fields (field (name "MOUSER_PART_NUMBER") "595-TLV75733PDBVR"))
      (libsource (lib "eagle-import") (part "TLV75733PDBVR"))
    )
    (comp (ref "J1")
      (value "640445-6")
      (footprint "eagle-import:SHDR6W183P0X396_1X6_2377X762X1")
      (fields (field (name "MOUSER_PART_NUMBER") "571-6404456"))
      (libsource (lib "eagle-import") (part "640445-6"))
    )
    (comp (ref "J17")
      (value "PINHD-1X3")
      (footprint "eagle-import:1X03")
      (libsource (lib "eagle-import") (part "PINHD-1X3"))
    )
    (comp (ref "J19")
      (value "PINHD-1X6")
      (footprint "eagle-import:1X06")
      (libsource (lib "eagle-import") (part "PINHD-1X6"))
    )
    (comp (ref "LED1")
      (value "EC3528ARGB")
      (footprint "eagle-import:EC3528ARGB")
      (libsource (lib "eagle-import") (part "EC3528ARGB"))
    )
    (comp (ref "LED2")
      (value "LT_Q39G-Q1OO-25-1")
      (footprint "eagle-import:LEDC1608X40N")
      (fields (field (name "ARROW_PART_NUMBER") "LT Q39G-Q1OO-25-1"))
      (libsource (lib "eagle-import") (part "LT_Q39G-Q1OO-25-1"))
    )
    (comp (ref "PICO1")
      (value "PICO")
      (footprint "eagle-import:RPI_PICO_TH_NO_DEBUG")
      (libsource (lib "eagle-import") (part "RPI_PICO_NO_DEBUG"))
    )
    (comp (ref "R36")
      (value "100R")
      (footprint "eagle-import:R0402")
      (libsource (lib "eagle-import") (part "resistor_R-US_R0402"))
    )
    (comp (ref "R37")
      (value "100R")
      (footprint "eagle-import:R0402")
      (libsource (lib "eagle-import") (part "resistor_R-US_R0402"))
    )
    (comp (ref "R38")
      (value "300R")
      (footprint "eagle-import:R0402")
      (libsource (lib "eagle-import") (part "resistor_R-US_R0402"))
    )
    (comp (ref "R40")
      (value "3.9K")
      (footprint "eagle-import:R0603")
      (libsource (lib "eagle-import") (part "resistor_R-US_R0603"))
    )
    (comp (ref "R41")
      (value "3.9K")
      (footprint "eagle-import:R0603")
      (libsource (lib "eagle-import") (part "resistor_R-US_R0603"))
    )
    (comp (ref "R47")
      (value "100R")
      (footprint "eagle-import:R0402")
      (libsource (lib "eagle-import") (part "resistor_R-US_R0402"))
    )
    (comp (ref "SW1")
      (value "TS-1187A-B-A-B")
      (footprint "eagle-import:TS-1187A-B-A-B")
      (libsource (lib "eagle-import") (part "TS-1187A-B-A-B"))
    )
    (comp (ref "C5")
      (value "0.1uF")
      (footprint "eagle-import:C0402")
      (libsource (lib "eagle-import") (part "resistor_C-USC0402"))
    )
    (comp (ref "C6")
      (value "4.7uF")
      (footprint "eagle-import:C1206")
      (libsource (lib "eagle-import") (part "resistor_C-USC1206"))
    )
    (comp (ref "C7")
      (value "0.1uF")
      (footprint "eagle-import:C0402")
      (libsource (lib "eagle-import") (part "resistor_C-USC0402"))
    )
    (comp (ref "C8")
      (value "4.7uF")
      (footprint "eagle-import:C1206")
      (libsource (lib "eagle-import") (part "resistor_C-USC1206"))
    )
    (comp (ref "C9")
      (value "0.1uF")
      (footprint "eagle-import:C0402")
      (libsource (lib "eagle-import") (part "resistor_C-USC0402"))
    )
    (comp (ref "C10")
      (value "4.7uF")
      (footprint "eagle-import:C1206")
      (libsource (lib "eagle-import") (part "resistor_C-USC1206"))
    )
    (comp (ref "C11")
      (value "0.1uF")
      (footprint "eagle-import:C0402")
      (libsource (lib "eagle-import") (part "resistor_C-USC0402"))
    )
    (comp (ref "C12")
      (value "4.7uF")
      (footprint "eagle-import:C1206")
      (libsource (lib "eagle-import") (part "resistor_C-USC1206"))
    )
    (comp (ref "C13")
      (value "0.1uF")
      (footprint "eagle-import:C0402")
      (libsource (lib "eagle-import") (part "resistor_C-USC0402"))
    )
    (comp (ref "C14")
      (value "4.7uF")
      (footprint "eagle-import:C1206")
      (libsource (lib "eagle-import") (part "resistor_C-USC1206"))
    )
    (comp (ref "C15")
      (value "0.1uF")
      (footprint "eagle-import:C0402")
      (libsource (lib "eagle-import") (part "resistor_C-USC0402"))
    )
    (comp (ref "C16")
      (value "4.7uF")
      (footprint "eagle-import:C1206")
      (libsource (lib "eagle-import") (part "resistor_C-USC1206"))
    )
    (comp (ref "C17")
      (value "0.1uF")
      (footprint "eagle-import:C0402")
      (libsource (lib "eagle-import") (part "resistor_C-USC0402"))
    )
    (comp (ref "C18")
      (value "4.7uF")
      (footprint "eagle-import:C1206")
      (libsource (lib "eagle-import") (part "resistor_C-USC1206"))
    )
    (comp (ref "C19")
      (value "0.1uF")
      (footprint "eagle-import:C0402")
      (libsource (lib "eagle-import") (part "resistor_C-USC0402"))
    )
    (comp (ref "C20")
      (value "4.7uF")
      (footprint "eagle-import:C1206")
      (libsource (lib "eagle-import") (part "resistor_C-USC1206"))
    )
    (comp (ref "C21")
      (value "0.1uF")
      (footprint "eagle-import:C0402")
      (libsource (lib "eagle-import") (part "resistor_C-USC0402"))
    )
    (comp (ref "C22")
      (value "4.7uF")
      (footprint "eagle-import:C1206")
      (libsource (lib "eagle-import") (part "resistor_C-USC1206"))
    )
    (comp (ref "C23")
      (value "0.1uF")
      (footprint "eagle-import:C0402")
      (libsource (lib "eagle-import") (part "resistor_C-USC0402"))
    )
    (comp (ref "C24")
      (value "4.7uF")
      (footprint "eagle-import:C1206")
      (libsource (lib "eagle-import") (part "resistor_C-USC1206"))
    )
    (comp (ref "C25")
      (value "0.1uF")
      (footprint "eagle-import:C0402")
      (libsource (lib "eagle-import") (part "resistor_C-USC0402"))
    )
    (comp (ref "C26")
      (value "4.7uF")
      (footprint "eagle-import:C1206")
      (libsource (lib "eagle-import") (part "resistor_C-USC1206"))
    )
    (comp (ref "C27")
      (value "0.1uF")
      (footprint "eagle-import:C0402")
      (libsource (lib "eagle-import") (part "resistor_C-USC0402"))
    )
    (comp (ref "C28")
      (value "4.7uF")
      (footprint "eagle-import:C1206")
      (libsource (lib "eagle-import") (part "resistor_C-USC1206"))
    )
    (comp (ref "C29")
      (value "1uF")
      (footprint "eagle-import:C0402")
      (libsource (lib "eagle-import") (part "C-USC0402"))
    )
    (comp (ref "C30")
      (value "1uF")
      (footprint "eagle-import:C0402")
      (libsource (lib "eagle-import") (part "C-USC0402"))
    )
    (comp (ref "IC3")
      (value "UCC27523D")
      (footprint "eagle-import:SOIC127P600X175-8N")
      (fields
        (field (name "MANUFACTURER_PART_NUMBER") "UCC27523DR")
        (field (name "MOUSER_PART_NUMBER") "595-UCC27523DR")
      )
      (libsource (lib "eagle-import") (part "UCC27523DR"))
    )
    (comp (ref "IC4")
      (value "UCC27523D")
      (footprint "eagle-import:SOIC127P600X175-8N")
      (fields
        (field (name "MANUFACTURER_PART_NUMBER") "UCC27523DR")
        (field (name "MOUSER_PART_NUMBER") "595-UCC27523DR")
      )
      (libsource (lib "eagle-import") (part "UCC27523DR"))
    )
    (comp (ref "IC5")
      (value "UCC27523D")
      (footprint "eagle-import:SOIC127P600X175-8N")
      (fields
        (field (name "MANUFACTURER_PART_NUMBER") "UCC27523DR")
        (field (name "MOUSER_PART_NUMBER") "595-UCC27523DR")
      )
      (libsource (lib "eagle-import") (part "UCC27523DR"))
    )
    (comp (ref "IC6")
      (value "UCC27523D")
      (footprint "eagle-import:SOIC127P600X175-8N")
      (fields
        (field (name "MANUFACTURER_PART_NUMBER") "UCC27523DR")
        (field (name "MOUSER_PART_NUMBER") "595-UCC27523DR")
      )
      (libsource (lib "eagle-import") (part "UCC27523DR"))
    )
    (comp (ref "IC7")
      (value "UCC27523D")
      (footprint "eagle-import:SOIC127P600X175-8N")
      (fields
        (field (name "MANUFACTURER_PART_NUMBER") "UCC27523DR")
        (field (name "MOUSER_PART_NUMBER") "595-UCC27523DR")
      )
      (libsource (lib "eagle-import") (part "UCC27523DR"))
    )
    (comp (ref "IC8")
      (value "UCC27523D")
      (footprint "eagle-import:SOIC127P600X175-8N")
      (fields
        (field (name "MANUFACTURER_PART_NUMBER") "UCC27523DR")
        (field (name "MOUSER_PART_NUMBER") "595-UCC27523DR")
      )
      (libsource (lib "eagle-import") (part "UCC27523DR"))
    )
    (comp (ref "IC9")
      (value "UCC27523D")
      (footprint "eagle-import:SOIC127P600X175-8N")
      (fields
        (field (name "MANUFACTURER_PART_NUMBER") "UCC27523DR")
        (field (name "MOUSER_PART_NUMBER") "595-UCC27523DR")
      )
      (libsource (lib "eagle-import") (part "UCC27523DR"))
    )
    (comp (ref "IC10")
      (value "UCC27523D")
      (footprint "eagle-import:SOIC127P600X175-8N")
      (fields
        (field (name "MANUFACTURER_PART_NUMBER") "UCC27523DR")
        (field (name "MOUSER_PART_NUMBER") "595-UCC27523DR")
      )
      (libsource (lib "eagle-import") (part "UCC27523DR"))
    )
    (comp (ref "IC11")
      (value "UCC27523D")
      (footprint "eagle-import:SOIC127P600X175-8N")
      (fields
        (field (name "MANUFACTURER_PART_NUMBER") "UCC27523DR")
        (field (name "MOUSER_PART_NUMBER") "595-UCC27523DR")
      )
      (libsource (lib "eagle-import") (part "UCC27523DR"))
    )
    (comp (ref "IC12")
      (value "UCC27523D")
      (footprint "eagle-import:SOIC127P600X175-8N")
      (fields
        (field (name "MANUFACTURER_PART_NUMBER") "UCC27523DR")
        (field (name "MOUSER_PART_NUMBER") "595-UCC27523DR")
      )
      (libsource (lib "eagle-import") (part "UCC27523DR"))
    )
    (comp (ref "IC13")
      (value "UCC27523D")
      (footprint "eagle-import:SOIC127P600X175-8N")
      (fields
        (field (name "MANUFACTURER_PART_NUMBER") "UCC27523DR")
        (field (name "MOUSER_PART_NUMBER") "595-UCC27523DR")
      )
      (libsource (lib "eagle-import") (part "UCC27523DR"))
    )
    (comp (ref "IC14")
      (value "UCC27523D")
      (footprint "eagle-import:SOIC127P600X175-8N")
      (fields
        (field (name "MANUFACTURER_PART_NUMBER") "UCC27523DR")
        (field (name "MOUSER_PART_NUMBER") "595-UCC27523DR")
      )
      (libsource (lib "eagle-import") (part "UCC27523DR"))
    )
    (comp (ref "IC15")
      (value "TLC59116FIRHBR")
      (footprint "eagle-import:QFN50P500X500X100-33N")
      (fields (field (name "MOUSER_PART_NUMBER") "595-TLC59116FIRHBR"))
      (libsource (lib "eagle-import") (part "TLC59116FIRHBR"))
    )
    (comp (ref "IC16")
      (value "TLC59116FIRHBR")
      (footprint "eagle-import:QFN50P500X500X100-33N")
      (fields (field (name "MOUSER_PART_NUMBER") "595-TLC59116FIRHBR"))
      (libsource (lib "eagle-import") (part "TLC59116FIRHBR"))
    )
    (comp (ref "J14")
      (value "640445-9")
      (footprint "eagle-import:SHDR9W117P0X396_1X9_3566X762X1")
      (fields (field (name "MOUSER_PART_NUMBER") "571-6404459"))
      (libsource (lib "eagle-import") (part "640445-9"))
    )
    (comp (ref "J15")
      (value "640445-9")
      (footprint "eagle-import:SHDR9W117P0X396_1X9_3566X762X1")
      (fields (field (name "MOUSER_PART_NUMBER") "571-6404459"))
      (libsource (lib "eagle-import") (part "640445-9"))
    )
    (comp (ref "J16")
      (value "640445-9")
      (footprint "eagle-import:SHDR9W117P0X396_1X9_3566X762X1")
      (fields (field (name "MOUSER_PART_NUMBER") "571-6404459"))
      (libsource (lib "eagle-import") (part "640445-9"))
    )
    (comp (ref "Q3")
      (value "BUK7K89-100EX")
      (footprint "eagle-import:BUK7K89100EX")
      (fields (field (name "MOUSER_PART_NUMBER") "771-BUK7K89-100EX"))
      (libsource (lib "eagle-import") (part "BUK7K89-100EX"))
    )
    (comp (ref "Q4")
      (value "BUK7K89-100EX")
      (footprint "eagle-import:BUK7K89100EX")
      (fields (field (name "MOUSER_PART_NUMBER") "771-BUK7K89-100EX"))
      (libsource (lib "eagle-import") (part "BUK7K89-100EX"))
    )
    (comp (ref "Q5")
      (value "BUK7K89-100EX")
      (footprint "eagle-import:BUK7K89100EX")
      (fields (field (name "MOUSER_PART_NUMBER") "771-BUK7K89-100EX"))
      (libsource (lib "eagle-import") (part "BUK7K89-100EX"))
    )
    (comp (ref "Q6")
      (value "BUK7K89-100EX")
      (footprint "eagle-import:BUK7K89100EX")
      (fields (field (name "MOUSER_PART_NUMBER") "771-BUK7K89-100EX"))
      (libsource (lib "eagle-import") (part "BUK7K89-100EX"))
    )
    (comp (ref "Q7")
      (value "BUK7K89-100EX")
      (footprint "eagle-import:BUK7K89100EX")
      (fields (field (name "MOUSER_PART_NUMBER") "771-BUK7K89-100EX"))
      (libsource (lib "eagle-import") (part "BUK7K89-100EX"))
    )
    (comp (ref "Q8")
      (value "BUK7K89-100EX")
      (footprint "eagle-import:BUK7K89100EX")
      (fields (field (name "MOUSER_PART_NUMBER") "771-BUK7K89-100EX"))
      (libsource (lib "eagle-import") (part "BUK7K89-100EX"))
    )
    (comp (ref "Q9")
      (value "BUK7K89-100EX")
      (footprint "eagle-import:BUK7K89100EX")
      (fields (field (name "MOUSER_PART_NUMBER") "771-BUK7K89-100EX"))
      (libsource (lib "eagle-import") (part "BUK7K89-100EX"))
    )
    (comp (ref "Q10")
      (value "BUK7K89-100EX")
      (footprint "eagle-import:BUK7K89100EX")
      (fields (field (name "MOUSER_PART_NUMBER") "771-BUK7K89-100EX"))
      (libsource (lib "eagle-import") (part "BUK7K89-100EX"))
    )
    (comp (ref "Q11")
      (value "BUK7K89-100EX")
      (footprint "eagle-import:BUK7K89100EX")
      (fields (field (name "MOUSER_PART_NUMBER") "771-BUK7K89-100EX"))
      (libsource (lib "eagle-import") (part "BUK7K89-100EX"))
    )
    (comp (ref "Q12")
      (value "BUK7K89-100EX")
      (footprint "eagle-import:BUK7K89100EX")
      (fields (field (name "MOUSER_PART_NUMBER") "771-BUK7K89-100EX"))
      (libsource (lib "eagle-import") (part "BUK7K89-100EX"))
    )
    (comp (ref "Q13")
      (value "BUK7K89-100EX")
      (footprint "eagle-import:BUK7K89100EX")
      (fields (field (name "MOUSER_PART_NUMBER") "771-BUK7K89-100EX"))
      (libsource (lib "eagle-import") (part "BUK7K89-100EX"))
    )
    (comp (ref "Q14")
      (value "BUK7K89-100EX")
      (footprint "eagle-import:BUK7K89100EX")
      (fields (field (name "MOUSER_PART_NUMBER") "771-BUK7K89-100EX"))
      (libsource (lib "eagle-import") (part "BUK7K89-100EX"))
    )
    (comp (ref "R5")
      (value "200R")
      (footprint "eagle-import:R0603")
      (libsource (lib "eagle-import") (part "resistor_R-US_R0603"))
    )
    (comp (ref "R6")
      (value "200R")
      (footprint "eagle-import:R0603")
      (libsource (lib "eagle-import") (part "resistor_R-US_R0603"))
    )
    (comp (ref "R7")
      (value "200R")
      (footprint "eagle-import:R0603")
      (libsource (lib "eagle-import") (part "resistor_R-US_R0603"))
    )
    (comp (ref "R8")
      (value "200R")
      (footprint "eagle-import:R0603")
      (libsource (lib "eagle-import") (part "resistor_R-US_R0603"))
    )
    (comp (ref "R9")
      (value "200R")
      (footprint "eagle-import:R0603")
      (libsource (lib "eagle-import") (part "resistor_R-US_R0603"))
    )
    (comp (ref "R10")
      (value "200R")
      (footprint "eagle-import:R0603")
      (libsource (lib "eagle-import") (part "resistor_R-US_R0603"))
    )
    (comp (ref "R11")
      (value "200R")
      (footprint "eagle-import:R0603")
      (libsource (lib "eagle-import") (part "resistor_R-US_R0603"))
    )
    (comp (ref "R12")
      (value "200R")
      (footprint "eagle-import:R0603")
      (libsource (lib "eagle-import") (part "resistor_R-US_R0603"))
    )
    (comp (ref "R13")
      (value "200R")
      (footprint "eagle-import:R0603")
      (libsource (lib "eagle-import") (part "resistor_R-US_R0603"))
    )
    (comp (ref "R14")
      (value "200R")
      (footprint "eagle-import:R0603")
      (libsource (lib "eagle-import") (part "resistor_R-US_R0603"))
    )
    (comp (ref "R15")
      (value "200R")
      (footprint "eagle-import:R0603")
      (libsource (lib "eagle-import") (part "resistor_R-US_R0603"))
    )
    (comp (ref "R16")
      (value "200R")
      (footprint "eagle-import:R0603")
      (libsource (lib "eagle-import") (part "resistor_R-US_R0603"))
    )
    (comp (ref "R17")
      (value "200R")
      (footprint "eagle-import:R0603")
      (libsource (lib "eagle-import") (part "resistor_R-US_R0603"))
    )
    (comp (ref "R18")
      (value "200R")
      (footprint "eagle-import:R0603")
      (libsource (lib "eagle-import") (part "resistor_R-US_R0603"))
    )
    (comp (ref "R19")
      (value "200R")
      (footprint "eagle-import:R0603")
      (libsource (lib "eagle-import") (part "resistor_R-US_R0603"))
    )
    (comp (ref "R20")
      (value "200R")
      (footprint "eagle-import:R0603")
      (libsource (lib "eagle-import") (part "resistor_R-US_R0603"))
    )
    (comp (ref "R21")
      (value "200R")
      (footprint "eagle-import:R0603")
      (libsource (lib "eagle-import") (part "resistor_R-US_R0603"))
    )
    (comp (ref "R22")
      (value "200R")
      (footprint "eagle-import:R0603")
      (libsource (lib "eagle-import") (part "resistor_R-US_R0603"))
    )
    (comp (ref "R23")
      (value "200R")
      (footprint "eagle-import:R0603")
      (libsource (lib "eagle-import") (part "resistor_R-US_R0603"))
    )
    (comp (ref "R24")
      (value "200R")
      (footprint "eagle-import:R0603")
      (libsource (lib "eagle-import") (part "resistor_R-US_R0603"))
    )
    (comp (ref "R25")
      (value "200R")
      (footprint "eagle-import:R0603")
      (libsource (lib "eagle-import") (part "resistor_R-US_R0603"))
    )
    (comp (ref "R26")
      (value "200R")
      (footprint "eagle-import:R0603")
      (libsource (lib "eagle-import") (part "resistor_R-US_R0603"))
    )
    (comp (ref "R27")
      (value "200R")
      (footprint "eagle-import:R0603")
      (libsource (lib "eagle-import") (part "resistor_R-US_R0603"))
    )
    (comp (ref "R28")
      (value "200R")
      (footprint "eagle-import:R0603")
      (libsource (lib "eagle-import") (part "resistor_R-US_R0603"))
    )
    (comp (ref "R39")
      (value "10K")
      (footprint "eagle-import:R0402")
      (libsource (lib "eagle-import") (part "resistor_R-US_R0402"))
    )
    (comp (ref "R42")
      (value "10K")
      (footprint "eagle-import:R0402")
      (libsource (lib "eagle-import") (part "resistor_R-US_R0402"))
    )
    (comp (ref "C32")
      (value "1uF")
      (footprint "eagle-import:C0402")
      (libsource (lib "eagle-import") (part "C-USC0402"))
    )
    (comp (ref "IC18")
      (value "TLC59116FIRHBR")
      (footprint "eagle-import:QFN50P500X500X100-33N")
      (fields (field (name "MOUSER_PART_NUMBER") "595-TLC59116FIRHBR"))
      (libsource (lib "eagle-import") (part "TLC59116FIRHBR"))
    )
    (comp (ref "J4")
      (value "640456-9")
      (footprint "eagle-import:SHDR9W66P0X254_1X9_2286X572X10")
      (fields (field (name "MOUSER_PART_NUMBER") "571-6404569"))
      (libsource (lib "eagle-import") (part "640456-9"))
    )
    (comp (ref "J5")
      (value "640456-9")
      (footprint "eagle-import:SHDR9W66P0X254_1X9_2286X572X10")
      (fields (field (name "MOUSER_PART_NUMBER") "571-6404569"))
      (libsource (lib "eagle-import") (part "640456-9"))
    )
    (comp (ref "R44")
      (value "10K")
      (footprint "eagle-import:R0402")
      (libsource (lib "eagle-import") (part "resistor_R-US_R0402"))
    )
  )
  (nets
    (net (code "1") (name "3V3_PERIPHERAL") (class "Default")
      (node (ref "C29") (pin "1") (pinfunction "1_1") (pintype "passive"))
      (node (ref "C30") (pin "1") (pinfunction "1_1") (pintype "passive"))
      (node (ref "C31") (pin "1") (pinfunction "1_1") (pintype "passive"))
      (node (ref "C32") (pin "1") (pinfunction "1_1") (pintype "passive"))
      (node (ref "C35") (pin "1") (pinfunction "1_1") (pintype "passive"))
      (node (ref "C37") (pin "1") (pinfunction "1_1") (pintype "passive"))
      (node (ref "C39") (pin "1") (pinfunction "1_1") (pintype "passive"))
      (node (ref "C40") (pin "1") (pinfunction "1_1") (pintype "passive"))
      (node (ref "IC15") (pin "27") (pinfunction "VCC_27") (pintype "bidirectional"))
      (node (ref "IC16") (pin "27") (pinfunction "VCC_27") (pintype "bidirectional"))
      (node (ref "IC16") (pin "31") (pinfunction "A0_31") (pintype "bidirectional"))
      (node (ref "IC17") (pin "27") (pinfunction "VCC_27") (pintype "bidirectional"))
      (node (ref "IC17") (pin "32") (pinfunction "A1_32") (pintype "bidirectional"))
      (node (ref "IC18") (pin "27") (pinfunction "VCC_27") (pintype "bidirectional"))
      (node (ref "IC18") (pin "31") (pinfunction "A0_31") (pintype "bidirectional"))
      (node (ref "IC18") (pin "32") (pinfunction "A1_32") (pintype "bidirectional"))
      (node (ref "IC28") (pin "1") (pinfunction "VDDIO_1") (pintype "power_in"))
      (node (ref "IC28") (pin "14") (pinfunction "VDD_14") (pintype "power_in"))
      (node (ref "IC28") (pin "8") (pinfunction "CS_8") (pintype "input"))
      (node (ref "IC31") (pin "6") (pinfunction "C_1_6") (pintype "bidirectional"))
      (node (ref "IC32") (pin "8") (pinfunction "VDD_8") (pintype "bidirectional"))
      (node (ref "IC33") (pin "5") (pinfunction "OUT_5") (pintype "output"))
      (node (ref "IC34") (pin "6") (pinfunction "VDD_6") (pintype "bidirectional"))
      (node (ref "J19") (pin "5") (pinfunction "5_5") (pintype "passive"))
      (node (ref "J7") (pin "1") (pinfunction "1_1") (pintype "bidirectional"))
      (node (ref "J8") (pin "4") (pinfunction "4_4") (pintype "bidirectional"))
      (node (ref "LED2") (pin "2") (pinfunction "A_2") (pintype "bidirectional"))
      (node (ref "R39") (pin "2") (pinfunction "2_2") (pintype "passive"))
      (node (ref "R40") (pin "2") (pinfunction "2_2") (pintype "passive"))
      (node (ref "R41") (pin "2") (pinfunction "2_2") (pintype "passive"))
      (node (ref "R42") (pin "2") (pinfunction "2_2") (pintype "passive"))
      (node (ref "R43") (pin "2") (pinfunction "2_2") (pintype "passive"))
      (node (ref "R44") (pin "2") (pinfunction "2_2") (pintype "passive"))
      (node (ref "R45") (pin "1") (pinfunction "1_1") (pintype "passive"))
    )
    (net (code "2") (name "3V3_PERIPHERAL_ENABLE") (class "Default")
      (node (ref "IC33") (pin "3") (pinfunction "EN_3") (pintype "input"))
      (node (ref "PICO1") (pin "GP7") (pinfunction "GP7_GP7") (pintype "bidirectional"))
    )
    (net (code "3") (name "3V3_PICO") (class "Default")
      (node (ref "C42") (pin "1") (pinfunction "1_1") (pintype "passive"))
      (node (ref "C43") (pin "1") (pinfunction "1_1") (pintype "passive"))
      (node (ref "C44") (pin "1") (pinfunction "1_1") (pintype "passive"))
      (node (ref "C45") (pin "1") (pinfunction "1_1") (pintype "passive"))
      (node (ref "IC24") (pin "16") (pinfunction "VCC_16") (pintype "bidirectional"))
      (node (ref "IC25") (pin "16") (pinfunction "VCC_16") (pintype "bidirectional"))
      (node (ref "IC26") (pin "16") (pinfunction "VCC_16") (pintype "bidirectional"))
      (node (ref "IC27") (pin "16") (pinfunction "VCC_16") (pintype "bidirectional"))
      (node (ref "LED1") (pin "1") (pinfunction "1_1") (pintype "bidirectional"))
      (node (ref "PICO1") (pin "3V3") (pinfunction "3V3_3V3") (pintype "bidirectional"))
      (node (ref "R51") (pin "1") (pinfunction "1_1") (pintype "passive"))
      (node (ref "R52") (pin "1") (pinfunction "1_1") (pintype "passive"))
      (node (ref "R53") (pin "1") (pinfunction "1_1") (pintype "passive"))
      (node (ref "R54") (pin "1") (pinfunction "1_1") (pintype "passive"))
      (node (ref "R55") (pin "1") (pinfunction "1_1") (pintype "passive"))
      (node (ref "R56") (pin "1") (pinfunction "1_1") (pintype "passive"))
      (node (ref "R57") (pin "1") (pinfunction "1_1") (pintype "passive"))
      (node (ref "R58") (pin "1") (pinfunction "1_1") (pintype "passive"))
      (node (ref "R59") (pin "1") (pinfunction "1_1") (pintype "passive"))
      (node (ref "R60") (pin "1") (pinfunction "1_1") (pintype "passive"))
      (node (ref "R61") (pin "1") (pinfunction "1_1") (pintype "passive"))
      (node (ref "R62") (pin "1") (pinfunction "1_1") (pintype "passive"))
      (node (ref "R63") (pin "1") (pinfunction "1_1") (pintype "passive"))
      (node (ref "R64") (pin "1") (pinfunction "1_1") (pintype "passive"))
      (node (ref "R65") (pin "1") (pinfunction "1_1") (pintype "passive"))
      (node (ref "R66") (pin "1") (pinfunction "1_1") (pintype "passive"))
      (node (ref "R67") (pin "1") (pinfunction "1_1") (pintype "passive"))
      (node (ref "R68") (pin "1") (pinfunction "1_1") (pintype "passive"))
      (node (ref "R69") (pin "1") (pinfunction "1_1") (pintype "passive"))
      (node (ref "R70") (pin "1") (pinfunction "1_1") (pintype "passive"))
      (node (ref "R71") (pin "1") (pinfunction "1_1") (pintype "passive"))
      (node (ref "R72") (pin "1") (pinfunction "1_1") (pintype "passive"))
      (node (ref "R73") (pin "1") (pinfunction "1_1") (pintype "passive"))
      (node (ref "R74") (pin "1") (pinfunction "1_1") (pintype "passive"))
      (node (ref "R75") (pin "1") (pinfunction "1_1") (pintype "passive"))
      (node (ref "R76") (pin "1") (pinfunction "1_1") (pintype "passive"))
      (node (ref "R77") (pin "1") (pinfunction "1_1") (pintype "passive"))
      (node (ref "R78") (pin "1") (pinfunction "1_1") (pintype "passive"))
      (node (ref "R79") (pin "1") (pinfunction "1_1") (pintype "passive"))
      (node (ref "R80") (pin "1") (pinfunction "1_1") (pintype "passive"))
      (node (ref "R81") (pin "1") (pinfunction "1_1") (pintype "passive"))
      (node (ref "R82") (pin "1") (pinfunction "1_1") (pintype "passive"))
    )
    (net (code "4") (name "5V") (class "Default")
      (node (ref "C36") (pin "1") (pinfunction "1_1") (pintype "passive"))
      (node (ref "IC29") (pin "3") (pinfunction "D_3") (pintype "bidirectional"))
      (node (ref "IC29") (pin "5") (pinfunction "VCC_5") (pintype "bidirectional"))
      (node (ref "IC30") (pin "3") (pinfunction "VCC_3") (pintype "power_in"))
      (node (ref "IC31") (pin "8") (pinfunction "C_2_8") (pintype "bidirectional"))
      (node (ref "J1") (pin "6") (pinfunction "6_6") (pintype "bidirectional"))
      (node (ref "J2") (pin "2") (pinfunction "2_2") (pintype "bidirectional"))
      (node (ref "J6") (pin "1") (pinfunction "1_1") (pintype "bidirectional"))
      (node (ref "J8") (pin "2") (pinfunction "2_2") (pintype "bidirectional"))
      (node (ref "Q15") (pin "2") (pinfunction "E_2") (pintype "bidirectional"))
      (node (ref "Q16") (pin "2") (pinfunction "E_2") (pintype "bidirectional"))
      (node (ref "Q17") (pin "2") (pinfunction "E_2") (pintype "bidirectional"))
      (node (ref "Q18") (pin "2") (pinfunction "E_2") (pintype "bidirectional"))
      (node (ref "Q19") (pin "2") (pinfunction "E_2") (pintype "bidirectional"))
      (node (ref "Q20") (pin "2") (pinfunction "E_2") (pintype "bidirectional"))
      (node (ref "Q21") (pin "2") (pinfunction "E_2") (pintype "bidirectional"))
      (node (ref "Q22") (pin "2") (pinfunction "E_2") (pintype "bidirectional"))
      (node (ref "Q23") (pin "2") (pinfunction "E_2") (pintype "bidirectional"))
      (node (ref "Q24") (pin "2") (pinfunction "E_2") (pintype "bidirectional"))
      (node (ref "Q25") (pin "2") (pinfunction "E_2") (pintype "bidirectional"))
      (node (ref "Q26") (pin "2") (pinfunction "E_2") (pintype "bidirectional"))
    )
    (net (code "5") (name "12V") (class "Default")
      (node (ref "C1") (pin "1") (pinfunction "1_1") (pintype "passive"))
      (node (ref "C10") (pin "1") (pinfunction "1_1") (pintype "passive"))
      (node (ref "C11") (pin "1") (pinfunction "1_1") (pintype "passive"))
      (node (ref "C12") (pin "1") (pinfunction "1_1") (pintype "passive"))
      (node (ref "C13") (pin "1") (pinfunction "1_1") (pintype "passive"))
      (node (ref "C14") (pin "1") (pinfunction "1_1") (pintype "passive"))
      (node (ref "C15") (pin "1") (pinfunction "1_1") (pintype "passive"))
      (node (ref "C16") (pin "1") (pinfunction "1_1") (pintype "passive"))
      (node (ref "C17") (pin "1") (pinfunction "1_1") (pintype "passive"))
      (node (ref "C18") (pin "1") (pinfunction "1_1") (pintype "passive"))
      (node (ref "C19") (pin "1") (pinfunction "1_1") (pintype "passive"))
      (node (ref "C2") (pin "1") (pinfunction "1_1") (pintype "passive"))
      (node (ref "C20") (pin "1") (pinfunction "1_1") (pintype "passive"))
      (node (ref "C21") (pin "1") (pinfunction "1_1") (pintype "passive"))
      (node (ref "C22") (pin "1") (pinfunction "1_1") (pintype "passive"))
      (node (ref "C23") (pin "1") (pinfunction "1_1") (pintype "passive"))
      (node (ref "C24") (pin "1") (pinfunction "1_1") (pintype "passive"))
      (node (ref "C25") (pin "1") (pinfunction "1_1") (pintype "passive"))
      (node (ref "C26") (pin "1") (pinfunction "1_1") (pintype "passive"))
      (node (ref "C27") (pin "1") (pinfunction "1_1") (pintype "passive"))
      (node (ref "C28") (pin "1") (pinfunction "1_1") (pintype "passive"))
      (node (ref "C3") (pin "1") (pinfunction "1_1") (pintype "passive"))
      (node (ref "C4") (pin "1") (pinfunction "1_1") (pintype "passive"))
      (node (ref "C5") (pin "1") (pinfunction "1_1") (pintype "passive"))
      (node (ref "C6") (pin "1") (pinfunction "1_1") (pintype "passive"))
      (node (ref "C7") (pin "1") (pinfunction "1_1") (pintype "passive"))
      (node (ref "C8") (pin "1") (pinfunction "1_1") (pintype "passive"))
      (node (ref "C9") (pin "1") (pinfunction "1_1") (pintype "passive"))
      (node (ref "IC1") (pin "1") (pinfunction "ENA_1") (pintype "bidirectional"))
      (node (ref "IC1") (pin "6") (pinfunction "VDD_6") (pintype "bidirectional"))
      (node (ref "IC1") (pin "8") (pinfunction "ENB_8") (pintype "bidirectional"))
      (node (ref "IC10") (pin "1") (pinfunction "ENA_1") (pintype "bidirectional"))
      (node (ref "IC10") (pin "6") (pinfunction "VDD_6") (pintype "bidirectional"))
      (node (ref "IC10") (pin "8") (pinfunction "ENB_8") (pintype "bidirectional"))
      (node (ref "IC11") (pin "1") (pinfunction "ENA_1") (pintype "bidirectional"))
      (node (ref "IC11") (pin "6") (pinfunction "VDD_6") (pintype "bidirectional"))
      (node (ref "IC11") (pin "8") (pinfunction "ENB_8") (pintype "bidirectional"))
      (node (ref "IC12") (pin "1") (pinfunction "ENA_1") (pintype "bidirectional"))
      (node (ref "IC12") (pin "6") (pinfunction "VDD_6") (pintype "bidirectional"))
      (node (ref "IC12") (pin "8") (pinfunction "ENB_8") (pintype "bidirectional"))
      (node (ref "IC13") (pin "1") (pinfunction "ENA_1") (pintype "bidirectional"))
      (node (ref "IC13") (pin "6") (pinfunction "VDD_6") (pintype "bidirectional"))
      (node (ref "IC13") (pin "8") (pinfunction "ENB_8") (pintype "bidirectional"))
      (node (ref "IC14") (pin "1") (pinfunction "ENA_1") (pintype "bidirectional"))
      (node (ref "IC14") (pin "6") (pinfunction "VDD_6") (pintype "bidirectional"))
      (node (ref "IC14") (pin "8") (pinfunction "ENB_8") (pintype "bidirectional"))
      (node (ref "IC2") (pin "1") (pinfunction "ENA_1") (pintype "bidirectional"))
      (node (ref "IC2") (pin "6") (pinfunction "VDD_6") (pintype "bidirectional"))
      (node (ref "IC2") (pin "8") (pinfunction "ENB_8") (pintype "bidirectional"))
      (node (ref "IC3") (pin "1") (pinfunction "ENA_1") (pintype "bidirectional"))
      (node (ref "IC3") (pin "6") (pinfunction "VDD_6") (pintype "bidirectional"))
      (node (ref "IC3") (pin "8") (pinfunction "ENB_8") (pintype "bidirectional"))
      (node (ref "IC4") (pin "1") (pinfunction "ENA_1") (pintype "bidirectional"))
      (node (ref "IC4") (pin "6") (pinfunction "VDD_6") (pintype "bidirectional"))
      (node (ref "IC4") (pin "8") (pinfunction "ENB_8") (pintype "bidirectional"))
      (node (ref "IC5") (pin "1") (pinfunction "ENA_1") (pintype "bidirectional"))
      (node (ref "IC5") (pin "6") (pinfunction "VDD_6") (pintype "bidirectional"))
      (node (ref "IC5") (pin "8") (pinfunction "ENB_8") (pintype "bidirectional"))
      (node (ref "IC6") (pin "1") (pinfunction "ENA_1") (pintype "bidirectional"))
      (node (ref "IC6") (pin "6") (pinfunction "VDD_6") (pintype "bidirectional"))
      (node (ref "IC6") (pin "8") (pinfunction "ENB_8") (pintype "bidirectional"))
      (node (ref "IC7") (pin "1") (pinfunction "ENA_1") (pintype "bidirectional"))
      (node (ref "IC7") (pin "6") (pinfunction "VDD_6") (pintype "bidirectional"))
      (node (ref "IC7") (pin "8") (pinfunction "ENB_8") (pintype "bidirectional"))
      (node (ref "IC8") (pin "1") (pinfunction "ENA_1") (pintype "bidirectional"))
      (node (ref "IC8") (pin "6") (pinfunction "VDD_6") (pintype "bidirectional"))
      (node (ref "IC8") (pin "8") (pinfunction "ENB_8") (pintype "bidirectional"))
      (node (ref "IC9") (pin "1") (pinfunction "ENA_1") (pintype "bidirectional"))
      (node (ref "IC9") (pin "6") (pinfunction "VDD_6") (pintype "bidirectional"))
      (node (ref "IC9") (pin "8") (pinfunction "ENB_8") (pintype "bidirectional"))
      (node (ref "J1") (pin "5") (pinfunction "5_5") (pintype "bidirectional"))
    )
    (net (code "6") (name "ACCEL_INTR") (class "Default")
      (node (ref "IC28") (pin "11") (pinfunction "INT1_11") (pintype "input"))
      (node (ref "PICO1") (pin "GP18") (pinfunction "GP18_GP18") (pintype "bidirectional"))
    )
    (net (code "7") (name "ADC_INTR") (class "Default")
      (node (ref "IC32") (pin "2") (pinfunction "ALERT/RDY_2") (pintype "bidirectional"))
      (node (ref "PICO1") (pin "GP12") (pinfunction "GP12_GP12") (pintype "bidirectional"))
    )
    (net (code "8") (name "BUTTON1") (class "Default")
      (node (ref "IC24") (pin "14") (pinfunction "D_14") (pintype "bidirectional"))
      (node (ref "J9") (pin "1") (pinfunction "1_1") (pintype "bidirectional"))
      (node (ref "R74") (pin "2") (pinfunction "2_2") (pintype "passive"))
    )
    (net (code "9") (name "BUTTON2") (class "Default")
      (node (ref "IC24") (pin "13") (pinfunction "C_13") (pintype "bidirectional"))
      (node (ref "J9") (pin "2") (pinfunction "2_2") (pintype "bidirectional"))
      (node (ref "R73") (pin "2") (pinfunction "2_2") (pintype "passive"))
    )
    (net (code "10") (name "BUTTON3") (class "Default")
      (node (ref "IC24") (pin "12") (pinfunction "B_12") (pintype "bidirectional"))
      (node (ref "J9") (pin "4") (pinfunction "4_4") (pintype "bidirectional"))
      (node (ref "R72") (pin "2") (pinfunction "2_2") (pintype "passive"))
    )
    (net (code "11") (name "BUTTON4") (class "Default")
      (node (ref "IC24") (pin "11") (pinfunction "A_11") (pintype "bidirectional"))
      (node (ref "J9") (pin "5") (pinfunction "5_5") (pintype "bidirectional"))
      (node (ref "R71") (pin "2") (pinfunction "2_2") (pintype "passive"))
    )
    (net (code "12") (name "BUTTON5") (class "Default")
      (node (ref "IC24") (pin "6") (pinfunction "H_6") (pintype "bidirectional"))
      (node (ref "J9") (pin "6") (pinfunction "6_6") (pintype "bidirectional"))
      (node (ref "R70") (pin "2") (pinfunction "2_2") (pintype "passive"))
    )
    (net (code "13") (name "BUTTON6") (class "Default")
      (node (ref "IC24") (pin "5") (pinfunction "G_5") (pintype "bidirectional"))
      (node (ref "J9") (pin "7") (pinfunction "7_7") (pintype "bidirectional"))
      (node (ref "R69") (pin "2") (pinfunction "2_2") (pintype "passive"))
    )
    (net (code "14") (name "BUTTON7") (class "Default")
      (node (ref "IC24") (pin "4") (pinfunction "F_4") (pintype "bidirectional"))
      (node (ref "J9") (pin "8") (pinfunction "8_8") (pintype "bidirectional"))
      (node (ref "R68") (pin "2") (pinfunction "2_2") (pintype "passive"))
    )
    (net (code "15") (name "BUTTON8") (class "Default")
      (node (ref "IC24") (pin "3") (pinfunction "E_3") (pintype "bidirectional"))
      (node (ref "J9") (pin "9") (pinfunction "9_9") (pintype "bidirectional"))
      (node (ref "R67") (pin "2") (pinfunction "2_2") (pintype "passive"))
    )
    (net (code "16") (name "BUTTON9") (class "Default")
      (node (ref "IC25") (pin "14") (pinfunction "D_14") (pintype "bidirectional"))
      (node (ref "J10") (pin "1") (pinfunction "1_1") (pintype "bidirectional"))
      (node (ref "R66") (pin "2") (pinfunction "2_2") (pintype "passive"))
    )
    (net (code "17") (name "BUTTON10") (class "Default")
      (node (ref "IC25") (pin "13") (pinfunction "C_13") (pintype "bidirectional"))
      (node (ref "J10") (pin "2") (pinfunction "2_2") (pintype "bidirectional"))
      (node (ref "R65") (pin "2") (pinfunction "2_2") (pintype "passive"))
    )
    (net (code "18") (name "BUTTON11") (class "Default")
      (node (ref "IC25") (pin "12") (pinfunction "B_12") (pintype "bidirectional"))
      (node (ref "J10") (pin "3") (pinfunction "3_3") (pintype "bidirectional"))
      (node (ref "R64") (pin "2") (pinfunction "2_2") (pintype "passive"))
    )
    (net (code "19") (name "BUTTON12") (class "Default")
      (node (ref "IC25") (pin "11") (pinfunction "A_11") (pintype "bidirectional"))
      (node (ref "J10") (pin "5") (pinfunction "5_5") (pintype "bidirectional"))
      (node (ref "R63") (pin "2") (pinfunction "2_2") (pintype "passive"))
    )
    (net (code "20") (name "BUTTON13") (class "Default")
      (node (ref "IC25") (pin "3") (pinfunction "E_3") (pintype "bidirectional"))
      (node (ref "J10") (pin "6") (pinfunction "6_6") (pintype "bidirectional"))
      (node (ref "R62") (pin "2") (pinfunction "2_2") (pintype "passive"))
    )
    (net (code "21") (name "BUTTON14") (class "Default")
      (node (ref "IC25") (pin "4") (pinfunction "F_4") (pintype "bidirectional"))
      (node (ref "J10") (pin "7") (pinfunction "7_7") (pintype "bidirectional"))
      (node (ref "R61") (pin "2") (pinfunction "2_2") (pintype "passive"))
    )
    (net (code "22") (name "BUTTON15") (class "Default")
      (node (ref "IC25") (pin "5") (pinfunction "G_5") (pintype "bidirectional"))
      (node (ref "J10") (pin "8") (pinfunction "8_8") (pintype "bidirectional"))
      (node (ref "R60") (pin "2") (pinfunction "2_2") (pintype "passive"))
    )
    (net (code "23") (name "BUTTON16") (class "Default")
      (node (ref "IC25") (pin "6") (pinfunction "H_6") (pintype "bidirectional"))
      (node (ref "J10") (pin "9") (pinfunction "9_9") (pintype "bidirectional"))
      (node (ref "R59") (pin "2") (pinfunction "2_2") (pintype "passive"))
    )
    (net (code "24") (name "BUTTON17") (class "Default")
      (node (ref "IC26") (pin "14") (pinfunction "D_14") (pintype "bidirectional"))
      (node (ref "J11") (pin "1") (pinfunction "1_1") (pintype "bidirectional"))
      (node (ref "R58") (pin "2") (pinfunction "2_2") (pintype "passive"))
    )
    (net (code "25") (name "BUTTON18") (class "Default")
      (node (ref "IC26") (pin "13") (pinfunction "C_13") (pintype "bidirectional"))
      (node (ref "J11") (pin "2") (pinfunction "2_2") (pintype "bidirectional"))
      (node (ref "R57") (pin "2") (pinfunction "2_2") (pintype "passive"))
    )
    (net (code "26") (name "BUTTON19") (class "Default")
      (node (ref "IC26") (pin "12") (pinfunction "B_12") (pintype "bidirectional"))
      (node (ref "J11") (pin "3") (pinfunction "3_3") (pintype "bidirectional"))
      (node (ref "R56") (pin "2") (pinfunction "2_2") (pintype "passive"))
    )
    (net (code "27") (name "BUTTON20") (class "Default")
      (node (ref "IC26") (pin "11") (pinfunction "A_11") (pintype "bidirectional"))
      (node (ref "J11") (pin "4") (pinfunction "4_4") (pintype "bidirectional"))
      (node (ref "R55") (pin "2") (pinfunction "2_2") (pintype "passive"))
    )
    (net (code "28") (name "BUTTON21") (class "Default")
      (node (ref "IC26") (pin "3") (pinfunction "E_3") (pintype "bidirectional"))
      (node (ref "J11") (pin "6") (pinfunction "6_6") (pintype "bidirectional"))
      (node (ref "R54") (pin "2") (pinfunction "2_2") (pintype "passive"))
    )
    (net (code "29") (name "BUTTON22") (class "Default")
      (node (ref "IC26") (pin "4") (pinfunction "F_4") (pintype "bidirectional"))
      (node (ref "J11") (pin "7") (pinfunction "7_7") (pintype "bidirectional"))
      (node (ref "R53") (pin "2") (pinfunction "2_2") (pintype "passive"))
    )
    (net (code "30") (name "BUTTON23") (class "Default")
      (node (ref "IC26") (pin "5") (pinfunction "G_5") (pintype "bidirectional"))
      (node (ref "J11") (pin "8") (pinfunction "8_8") (pintype "bidirectional"))
      (node (ref "R52") (pin "2") (pinfunction "2_2") (pintype "passive"))
    )
    (net (code "31") (name "BUTTON24") (class "Default")
      (node (ref "IC26") (pin "6") (pinfunction "H_6") (pintype "bidirectional"))
      (node (ref "J11") (pin "9") (pinfunction "9_9") (pintype "bidirectional"))
      (node (ref "R51") (pin "2") (pinfunction "2_2") (pintype "passive"))
    )
    (net (code "32") (name "BUTTON25") (class "Default")
      (node (ref "IC27") (pin "11") (pinfunction "A_11") (pintype "bidirectional"))
      (node (ref "J12") (pin "1") (pinfunction "1_1") (pintype "bidirectional"))
      (node (ref "R82") (pin "2") (pinfunction "2_2") (pintype "passive"))
    )
    (net (code "33") (name "BUTTON26") (class "Default")
      (node (ref "IC27") (pin "12") (pinfunction "B_12") (pintype "bidirectional"))
      (node (ref "J12") (pin "2") (pinfunction "2_2") (pintype "bidirectional"))
      (node (ref "R81") (pin "2") (pinfunction "2_2") (pintype "passive"))
    )
    (net (code "34") (name "BUTTON27") (class "Default")
      (node (ref "IC27") (pin "13") (pinfunction "C_13") (pintype "bidirectional"))
      (node (ref "J12") (pin "3") (pinfunction "3_3") (pintype "bidirectional"))
      (node (ref "R80") (pin "2") (pinfunction "2_2") (pintype "passive"))
    )
    (net (code "35") (name "BUTTON28") (class "Default")
      (node (ref "IC27") (pin "14") (pinfunction "D_14") (pintype "bidirectional"))
      (node (ref "J12") (pin "4") (pinfunction "4_4") (pintype "bidirectional"))
      (node (ref "R79") (pin "2") (pinfunction "2_2") (pintype "passive"))
    )
    (net (code "36") (name "BUTTON29") (class "Default")
      (node (ref "IC27") (pin "6") (pinfunction "H_6") (pintype "bidirectional"))
      (node (ref "J12") (pin "5") (pinfunction "5_5") (pintype "bidirectional"))
      (node (ref "R78") (pin "2") (pinfunction "2_2") (pintype "passive"))
    )
    (net (code "37") (name "BUTTON30") (class "Default")
      (node (ref "IC27") (pin "5") (pinfunction "G_5") (pintype "bidirectional"))
      (node (ref "J12") (pin "7") (pinfunction "7_7") (pintype "bidirectional"))
      (node (ref "R77") (pin "2") (pinfunction "2_2") (pintype "passive"))
    )
    (net (code "38") (name "BUTTON31") (class "Default")
      (node (ref "IC27") (pin "4") (pinfunction "F_4") (pintype "bidirectional"))
      (node (ref "J12") (pin "8") (pinfunction "8_8") (pintype "bidirectional"))
      (node (ref "R76") (pin "2") (pinfunction "2_2") (pintype "passive"))
    )
    (net (code "39") (name "BUTTON32") (class "Default")
      (node (ref "IC27") (pin "3") (pinfunction "E_3") (pintype "bidirectional"))
      (node (ref "J12") (pin "9") (pinfunction "9_9") (pintype "bidirectional"))
      (node (ref "R75") (pin "2") (pinfunction "2_2") (pintype "passive"))
    )
    (net (code "40") (name "BUTTON_CLK") (class "Default")
      (node (ref "IC24") (pin "2") (pinfunction "CLK_2") (pintype "bidirectional"))
      (node (ref "IC25") (pin "2") (pinfunction "CLK_2") (pintype "bidirectional"))
      (node (ref "IC26") (pin "2") (pinfunction "CLK_2") (pintype "bidirectional"))
      (node (ref "IC27") (pin "2") (pinfunction "CLK_2") (pintype "bidirectional"))
      (node (ref "PICO1") (pin "GP21") (pinfunction "GP21_GP21") (pintype "bidirectional"))
    )
    (net (code "41") (name "BUTTON_DATA") (class "Default")
      (node (ref "IC24") (pin "9") (pinfunction "QH_9") (pintype "bidirectional"))
      (node (ref "PICO1") (pin "GP26_A0") (pinfunction "GP26_A0_GP26_A0") (pintype "bidirectional"))
    )
    (net (code "42") (name "BUTTON_SHLD") (class "Default")
      (node (ref "IC24") (pin "1") (pinfunction "SH/~{LD}_1") (pintype "bidirectional"))
      (node (ref "IC25") (pin "1") (pinfunction "SH/~{LD}_1") (pintype "bidirectional"))
      (node (ref "IC26") (pin "1") (pinfunction "SH/~{LD}_1") (pintype "bidirectional"))
      (node (ref "IC27") (pin "1") (pinfunction "SH/~{LD}_1") (pintype "bidirectional"))
      (node (ref "PICO1") (pin "GP22") (pinfunction "GP22_GP22") (pintype "bidirectional"))
    )
    (net (code "43") (name "FLASHER1") (class "Default")
      (node (ref "IC19") (pin "19") (pinfunction "2C_19") (pintype "bidirectional"))
      (node (ref "IC19") (pin "20") (pinfunction "1C_20") (pintype "bidirectional"))
      (node (ref "J2") (pin "15") (pinfunction "15_15") (pintype "bidirectional"))
    )
    (net (code "44") (name "FLASHER2") (class "Default")
      (node (ref "IC19") (pin "17") (pinfunction "4C_17") (pintype "bidirectional"))
      (node (ref "IC19") (pin "18") (pinfunction "3C_18") (pintype "bidirectional"))
      (node (ref "J2") (pin "13") (pinfunction "13_13") (pintype "bidirectional"))
    )
    (net (code "45") (name "FLASHER3") (class "Default")
      (node (ref "IC19") (pin "15") (pinfunction "6C_15") (pintype "bidirectional"))
      (node (ref "IC19") (pin "16") (pinfunction "5C_16") (pintype "bidirectional"))
      (node (ref "J2") (pin "11") (pinfunction "11_11") (pintype "bidirectional"))
    )
    (net (code "46") (name "FLASHER4") (class "Default")
      (node (ref "IC19") (pin "13") (pinfunction "8C_13") (pintype "bidirectional"))
      (node (ref "IC19") (pin "14") (pinfunction "7C_14") (pintype "bidirectional"))
      (node (ref "J2") (pin "9") (pinfunction "9_9") (pintype "bidirectional"))
    )
    (net (code "47") (name "FLASHER5") (class "Default")
      (node (ref "IC20") (pin "19") (pinfunction "2C_19") (pintype "bidirectional"))
      (node (ref "IC20") (pin "20") (pinfunction "1C_20") (pintype "bidirectional"))
      (node (ref "J2") (pin "7") (pinfunction "7_7") (pintype "bidirectional"))
    )
    (net (code "48") (name "FLASHER6") (class "Default")
      (node (ref "IC20") (pin "17") (pinfunction "4C_17") (pintype "bidirectional"))
      (node (ref "IC20") (pin "18") (pinfunction "3C_18") (pintype "bidirectional"))
      (node (ref "J2") (pin "5") (pinfunction "5_5") (pintype "bidirectional"))
    )
    (net (code "49") (name "FLASHER7") (class "Default")
      (node (ref "IC20") (pin "15") (pinfunction "6C_15") (pintype "bidirectional"))
      (node (ref "IC20") (pin "16") (pinfunction "5C_16") (pintype "bidirectional"))
      (node (ref "J2") (pin "3") (pinfunction "3_3") (pintype "bidirectional"))
    )
    (net (code "50") (name "FLASHER8") (class "Default")
      (node (ref "IC20") (pin "13") (pinfunction "8C_13") (pintype "bidirectional"))
      (node (ref "IC20") (pin "14") (pinfunction "7C_14") (pintype "bidirectional"))
      (node (ref "J2") (pin "1") (pinfunction "1_1") (pintype "bidirectional"))
    )
    (net (code "51") (name "FLASHER9") (class "Default")
      (node (ref "IC21") (pin "19") (pinfunction "2C_19") (pintype "bidirectional"))
      (node (ref "IC21") (pin "20") (pinfunction "1C_20") (pintype "bidirectional"))
      (node (ref "J2") (pin "16") (pinfunction "16_16") (pintype "bidirectional"))
    )
    (net (code "52") (name "FLASHER10") (class "Default")
      (node (ref "IC21") (pin "17") (pinfunction "4C_17") (pintype "bidirectional"))
      (node (ref "IC21") (pin "18") (pinfunction "3C_18") (pintype "bidirectional"))
      (node (ref "J2") (pin "14") (pinfunction "14_14") (pintype "bidirectional"))
    )
    (net (code "53") (name "FLASHER11") (class "Default")
      (node (ref "IC21") (pin "15") (pinfunction "6C_15") (pintype "bidirectional"))
      (node (ref "IC21") (pin "16") (pinfunction "5C_16") (pintype "bidirectional"))
      (node (ref "J2") (pin "12") (pinfunction "12_12") (pintype "bidirectional"))
    )
    (net (code "54") (name "FLASHER12") (class "Default")
      (node (ref "IC21") (pin "13") (pinfunction "8C_13") (pintype "bidirectional"))
      (node (ref "IC21") (pin "14") (pinfunction "7C_14") (pintype "bidirectional"))
      (node (ref "J2") (pin "10") (pinfunction "10_10") (pintype "bidirectional"))
    )
    (net (code "55") (name "FLASHER13") (class "Default")
      (node (ref "IC22") (pin "19") (pinfunction "2C_19") (pintype "bidirectional"))
      (node (ref "IC22") (pin "20") (pinfunction "1C_20") (pintype "bidirectional"))
      (node (ref "J2") (pin "8") (pinfunction "8_8") (pintype "bidirectional"))
    )
    (net (code "56") (name "FLASHER14") (class "Default")
      (node (ref "IC22") (pin "17") (pinfunction "4C_17") (pintype "bidirectional"))
      (node (ref "IC22") (pin "18") (pinfunction "3C_18") (pintype "bidirectional"))
      (node (ref "J2") (pin "6") (pinfunction "6_6") (pintype "bidirectional"))
    )
    (net (code "57") (name "FLASHER15") (class "Default")
      (node (ref "IC22") (pin "15") (pinfunction "6C_15") (pintype "bidirectional"))
      (node (ref "IC22") (pin "16") (pinfunction "5C_16") (pintype "bidirectional"))
      (node (ref "J2") (pin "4") (pinfunction "4_4") (pintype "bidirectional"))
    )
    (net (code "58") (name "FLASHER16") (class "Default")
      (node (ref "IC22") (pin "13") (pinfunction "8C_13") (pintype "bidirectional"))
      (node (ref "IC22") (pin "14") (pinfunction "7C_14") (pintype "bidirectional"))
      (node (ref "J3") (pin "1") (pinfunction "1_1") (pintype "bidirectional"))
    )
    (net (code "59") (name "GND") (class "Default")
      (node (ref "BATT1") (pin "-") (pinfunction "-_-") (pintype "bidirectional"))
      (node (ref "C1") (pin "2") (pinfunction "2_2") (pintype "passive"))
      (node (ref "C10") (pin "2") (pinfunction "2_2") (pintype "passive"))
      (node (ref "C11") (pin "2") (pinfunction "2_2") (pintype "passive"))
      (node (ref "C12") (pin "2") (pinfunction "2_2") (pintype "passive"))
      (node (ref "C13") (pin "2") (pinfunction "2_2") (pintype "passive"))
      (node (ref "C14") (pin "2") (pinfunction "2_2") (pintype "passive"))
      (node (ref "C15") (pin "2") (pinfunction "2_2") (pintype "passive"))
      (node (ref "C16") (pin "2") (pinfunction "2_2") (pintype "passive"))
      (node (ref "C17") (pin "2") (pinfunction "2_2") (pintype "passive"))
      (node (ref "C18") (pin "2") (pinfunction "2_2") (pintype "passive"))
      (node (ref "C19") (pin "2") (pinfunction "2_2") (pintype "passive"))
      (node (ref "C2") (pin "2") (pinfunction "2_2") (pintype "passive"))
      (node (ref "C20") (pin "2") (pinfunction "2_2") (pintype "passive"))
      (node (ref "C21") (pin "2") (pinfunction "2_2") (pintype "passive"))
      (node (ref "C22") (pin "2") (pinfunction "2_2") (pintype "passive"))
      (node (ref "C23") (pin "2") (pinfunction "2_2") (pintype "passive"))
      (node (ref "C24") (pin "2") (pinfunction "2_2") (pintype "passive"))
      (node (ref "C25") (pin "2") (pinfunction "2_2") (pintype "passive"))
      (node (ref "C26") (pin "2") (pinfunction "2_2") (pintype "passive"))
      (node (ref "C27") (pin "2") (pinfunction "2_2") (pintype "passive"))
      (node (ref "C28") (pin "2") (pinfunction "2_2") (pintype "passive"))
      (node (ref "C29") (pin "2") (pinfunction "2_2") (pintype "passive"))
      (node (ref "C3") (pin "2") (pinfunction "2_2") (pintype "passive"))
      (node (ref "C30") (pin "2") (pinfunction "2_2") (pintype "passive"))
      (node (ref "C31") (pin "2") (pinfunction "2_2") (pintype "passive"))
      (node (ref "C32") (pin "2") (pinfunction "2_2") (pintype "passive"))
      (node (ref "C35") (pin "2") (pinfunction "2_2") (pintype "passive"))
      (node (ref "C36") (pin "2") (pinfunction "2_2") (pintype "passive"))
      (node (ref "C37") (pin "2") (pinfunction "2_2") (pintype "passive"))
      (node (ref "C38") (pin "2") (pinfunction "2_2") (pintype "passive"))
      (node (ref "C39") (pin "2") (pinfunction "2_2") (pintype "passive"))
      (node (ref "C4") (pin "2") (pinfunction "2_2") (pintype "passive"))
      (node (ref "C40") (pin "2") (pinfunction "2_2") (pintype "passive"))
      (node (ref "C41") (pin "2") (pinfunction "2_2") (pintype "passive"))
      (node (ref "C42") (pin "2") (pinfunction "2_2") (pintype "passive"))
      (node (ref "C43") (pin "2") (pinfunction "2_2") (pintype "passive"))
      (node (ref "C44") (pin "2") (pinfunction "2_2") (pintype "passive"))
      (node (ref "C45") (pin "2") (pinfunction "2_2") (pintype "passive"))
      (node (ref "C5") (pin "2") (pinfunction "2_2") (pintype "passive"))
      (node (ref "C6") (pin "2") (pinfunction "2_2") (pintype "passive"))
      (node (ref "C7") (pin "2") (pinfunction "2_2") (pintype "passive"))
      (node (ref "C8") (pin "2") (pinfunction "2_2") (pintype "passive"))
      (node (ref "C9") (pin "2") (pinfunction "2_2") (pintype "passive"))
      (node (ref "D2") (pin "1") (pinfunction "K_1") (pintype "bidirectional"))
      (node (ref "IC1") (pin "3") (pinfunction "GND_3") (pintype "bidirectional"))
      (node (ref "IC10") (pin "3") (pinfunction "GND_3") (pintype "bidirectional"))
      (node (ref "IC11") (pin "3") (pinfunction "GND_3") (pintype "bidirectional"))
      (node (ref "IC12") (pin "3") (pinfunction "GND_3") (pintype "bidirectional"))
      (node (ref "IC13") (pin "3") (pinfunction "GND_3") (pintype "bidirectional"))
      (node (ref "IC14") (pin "3") (pinfunction "GND_3") (pintype "bidirectional"))
      (node (ref "IC15") (pin "1") (pinfunction "A2_1") (pintype "bidirectional"))
      (node (ref "IC15") (pin "18") (pinfunction "GND_2_18") (pintype "bidirectional"))
      (node (ref "IC15") (pin "2") (pinfunction "A3_2") (pintype "bidirectional"))
      (node (ref "IC15") (pin "23") (pinfunction "GND_3_23") (pintype "bidirectional"))
      (node (ref "IC15") (pin "31") (pinfunction "A0_31") (pintype "bidirectional"))
      (node (ref "IC15") (pin "32") (pinfunction "A1_32") (pintype "bidirectional"))
      (node (ref "IC15") (pin "33") (pinfunction "EP_33") (pintype "bidirectional"))
      (node (ref "IC15") (pin "7") (pinfunction "GND_1_7") (pintype "bidirectional"))
      (node (ref "IC16") (pin "1") (pinfunction "A2_1") (pintype "bidirectional"))
      (node (ref "IC16") (pin "18") (pinfunction "GND_2_18") (pintype "bidirectional"))
      (node (ref "IC16") (pin "2") (pinfunction "A3_2") (pintype "bidirectional"))
      (node (ref "IC16") (pin "23") (pinfunction "GND_3_23") (pintype "bidirectional"))
      (node (ref "IC16") (pin "32") (pinfunction "A1_32") (pintype "bidirectional"))
      (node (ref "IC16") (pin "33") (pinfunction "EP_33") (pintype "bidirectional"))
      (node (ref "IC16") (pin "7") (pinfunction "GND_1_7") (pintype "bidirectional"))
      (node (ref "IC17") (pin "1") (pinfunction "A2_1") (pintype "bidirectional"))
      (node (ref "IC17") (pin "18") (pinfunction "GND_2_18") (pintype "bidirectional"))
      (node (ref "IC17") (pin "2") (pinfunction "A3_2") (pintype "bidirectional"))
      (node (ref "IC17") (pin "23") (pinfunction "GND_3_23") (pintype "bidirectional"))
      (node (ref "IC17") (pin "31") (pinfunction "A0_31") (pintype "bidirectional"))
      (node (ref "IC17") (pin "33") (pinfunction "EP_33") (pintype "bidirectional"))
      (node (ref "IC17") (pin "7") (pinfunction "GND_1_7") (pintype "bidirectional"))
      (node (ref "IC18") (pin "1") (pinfunction "A2_1") (pintype "bidirectional"))
      (node (ref "IC18") (pin "18") (pinfunction "GND_2_18") (pintype "bidirectional"))
      (node (ref "IC18") (pin "2") (pinfunction "A3_2") (pintype "bidirectional"))
      (node (ref "IC18") (pin "23") (pinfunction "GND_3_23") (pintype "bidirectional"))
      (node (ref "IC18") (pin "33") (pinfunction "EP_33") (pintype "bidirectional"))
      (node (ref "IC18") (pin "7") (pinfunction "GND_1_7") (pintype "bidirectional"))
      (node (ref "IC19") (pin "9") (pinfunction "GND_9") (pintype "bidirectional"))
      (node (ref "IC2") (pin "3") (pinfunction "GND_3") (pintype "bidirectional"))
      (node (ref "IC20") (pin "9") (pinfunction "GND_9") (pintype "bidirectional"))
      (node (ref "IC21") (pin "9") (pinfunction "GND_9") (pintype "bidirectional"))
      (node (ref "IC22") (pin "9") (pinfunction "GND_9") (pintype "bidirectional"))
      (node (ref "IC23") (pin "9") (pinfunction "GND_9") (pintype "bidirectional"))
      (node (ref "IC24") (pin "15") (pinfunction "CLK_INH_15") (pintype "bidirectional"))
      (node (ref "IC24") (pin "8") (pinfunction "GND_8") (pintype "bidirectional"))
      (node (ref "IC25") (pin "15") (pinfunction "CLK_INH_15") (pintype "bidirectional"))
      (node (ref "IC25") (pin "8") (pinfunction "GND_8") (pintype "bidirectional"))
      (node (ref "IC26") (pin "15") (pinfunction "CLK_INH_15") (pintype "bidirectional"))
      (node (ref "IC26") (pin "8") (pinfunction "GND_8") (pintype "bidirectional"))
      (node (ref "IC27") (pin "15") (pinfunction "CLK_INH_15") (pintype "bidirectional"))
      (node (ref "IC27") (pin "8") (pinfunction "GND_8") (pintype "bidirectional"))
      (node (ref "IC28") (pin "10") (pinfunction "RES_10") (pintype "bidirectional"))
      (node (ref "IC28") (pin "12") (pinfunction "GND_2_12") (pintype "power_in"))
      (node (ref "IC28") (pin "13") (pinfunction "ADC3_13") (pintype "bidirectional"))
      (node (ref "IC28") (pin "15") (pinfunction "ADC2_15") (pintype "bidirectional"))
      (node (ref "IC28") (pin "16") (pinfunction "ADC1_16") (pintype "bidirectional"))
      (node (ref "IC28") (pin "5") (pinfunction "GND_1_5") (pintype "power_in"))
      (node (ref "IC28") (pin "7") (pinfunction "SDO/SA0_7") (pintype "bidirectional"))
      (node (ref "IC29") (pin "2") (pinfunction "GND_2") (pintype "bidirectional"))
      (node (ref "IC3") (pin "3") (pinfunction "GND_3") (pintype "bidirectional"))
      (node (ref "IC30") (pin "1") (pinfunction "GND_1") (pintype "passive"))
      (node (ref "IC32") (pin "1") (pinfunction "ADDR_1") (pintype "bidirectional"))
      (node (ref "IC32") (pin "3") (pinfunction "GND_3") (pintype "bidirectional"))
      (node (ref "IC33") (pin "2") (pinfunction "GND_2") (pintype "power_in"))
      (node (ref "IC34") (pin "5") (pinfunction "VSS_5") (pintype "bidirectional"))
      (node (ref "IC4") (pin "3") (pinfunction "GND_3") (pintype "bidirectional"))
      (node (ref "IC5") (pin "3") (pinfunction "GND_3") (pintype "bidirectional"))
      (node (ref "IC6") (pin "3") (pinfunction "GND_3") (pintype "bidirectional"))
      (node (ref "IC7") (pin "3") (pinfunction "GND_3") (pintype "bidirectional"))
      (node (ref "IC8") (pin "3") (pinfunction "GND_3") (pintype "bidirectional"))
      (node (ref "IC9") (pin "3") (pinfunction "GND_3") (pintype "bidirectional"))
      (node (ref "J1") (pin "1") (pinfunction "1_1") (pintype "bidirectional"))
      (node (ref "J1") (pin "2") (pinfunction "2_2") (pintype "bidirectional"))
      (node (ref "J1") (pin "3") (pinfunction "3_3") (pintype "bidirectional"))
      (node (ref "J1") (pin "4") (pinfunction "4_4") (pintype "bidirectional"))
      (node (ref "J10") (pin "10") (pinfunction "10_10") (pintype "bidirectional"))
      (node (ref "J11") (pin "10") (pinfunction "10_10") (pintype "bidirectional"))
      (node (ref "J12") (pin "10") (pinfunction "10_10") (pintype "bidirectional"))
      (node (ref "J17") (pin "2") (pinfunction "2_2") (pintype "passive"))
      (node (ref "J19") (pin "6") (pinfunction "6_6") (pintype "passive"))
      (node (ref "J7") (pin "2") (pinfunction "2_2") (pintype "bidirectional"))
      (node (ref "J7") (pin "4") (pinfunction "4_4") (pintype "bidirectional"))
      (node (ref "J8") (pin "3") (pinfunction "3_3") (pintype "bidirectional"))
      (node (ref "J9") (pin "10") (pinfunction "10_10") (pintype "bidirectional"))
      (node (ref "PICO1") (pin "AGND") (pinfunction "AGND_AGND") (pintype "bidirectional"))
      (node (ref "PICO1") (pin "GND@1") (pinfunction "GND_GND@1") (pintype "bidirectional"))
      (node (ref "PICO1") (pin "GND@2") (pinfunction "GND_GND@2") (pintype "bidirectional"))
      (node (ref "PICO1") (pin "GND@3") (pinfunction "GND_GND@3") (pintype "bidirectional"))
      (node (ref "PICO1") (pin "GND@4") (pinfunction "GND_GND@4") (pintype "bidirectional"))
      (node (ref "PICO1") (pin "GND@6") (pinfunction "GND_GND@6") (pintype "bidirectional"))
      (node (ref "PICO1") (pin "GND@7") (pinfunction "GND_GND@7") (pintype "bidirectional"))
      (node (ref "PICO1") (pin "GND@8") (pinfunction "GND_GND@8") (pintype "bidirectional"))
      (node (ref "Q1") (pin "1") (pinfunction "S1_1") (pintype "bidirectional"))
      (node (ref "Q1") (pin "3") (pinfunction "S2_3") (pintype "bidirectional"))
      (node (ref "Q10") (pin "1") (pinfunction "S1_1") (pintype "bidirectional"))
      (node (ref "Q10") (pin "3") (pinfunction "S2_3") (pintype "bidirectional"))
      (node (ref "Q11") (pin "1") (pinfunction "S1_1") (pintype "bidirectional"))
      (node (ref "Q11") (pin "3") (pinfunction "S2_3") (pintype "bidirectional"))
      (node (ref "Q12") (pin "1") (pinfunction "S1_1") (pintype "bidirectional"))
      (node (ref "Q12") (pin "3") (pinfunction "S2_3") (pintype "bidirectional"))
      (node (ref "Q13") (pin "1") (pinfunction "S1_1") (pintype "bidirectional"))
      (node (ref "Q13") (pin "3") (pinfunction "S2_3") (pintype "bidirectional"))
      (node (ref "Q14") (pin "1") (pinfunction "S1_1") (pintype "bidirectional"))
      (node (ref "Q14") (pin "3") (pinfunction "S2_3") (pintype "bidirectional"))
      (node (ref "Q2") (pin "1") (pinfunction "S1_1") (pintype "bidirectional"))
      (node (ref "Q2") (pin "3") (pinfunction "S2_3") (pintype "bidirectional"))
      (node (ref "Q3") (pin "1") (pinfunction "S1_1") (pintype "bidirectional"))
      (node (ref "Q3") (pin "3") (pinfunction "S2_3") (pintype "bidirectional"))
      (node (ref "Q4") (pin "1") (pinfunction "S1_1") (pintype "bidirectional"))
      (node (ref "Q4") (pin "3") (pinfunction "S2_3") (pintype "bidirectional"))
      (node (ref "Q5") (pin "1") (pinfunction "S1_1") (pintype "bidirectional"))
      (node (ref "Q5") (pin "3") (pinfunction "S2_3") (pintype "bidirectional"))
      (node (ref "Q6") (pin "1") (pinfunction "S1_1") (pintype "bidirectional"))
      (node (ref "Q6") (pin "3") (pinfunction "S2_3") (pintype "bidirectional"))
      (node (ref "Q7") (pin "1") (pinfunction "S1_1") (pintype "bidirectional"))
      (node (ref "Q7") (pin "3") (pinfunction "S2_3") (pintype "bidirectional"))
      (node (ref "Q8") (pin "1") (pinfunction "S1_1") (pintype "bidirectional"))
      (node (ref "Q8") (pin "3") (pinfunction "S2_3") (pintype "bidirectional"))
      (node (ref "Q9") (pin "1") (pinfunction "S1_1") (pintype "bidirectional"))
      (node (ref "Q9") (pin "3") (pinfunction "S2_3") (pintype "bidirectional"))
      (node (ref "R29") (pin "1") (pinfunction "1_1") (pintype "passive"))
      (node (ref "R31") (pin "1") (pinfunction "1_1") (pintype "passive"))
      (node (ref "R32") (pin "1") (pinfunction "1_1") (pintype "passive"))
      (node (ref "R33") (pin "1") (pinfunction "1_1") (pintype "passive"))
      (node (ref "R34") (pin "2") (pinfunction "2_2") (pintype "passive"))
      (node (ref "R35") (pin "2") (pinfunction "2_2") (pintype "passive"))
      (node (ref "R46") (pin "1") (pinfunction "1_1") (pintype "passive"))
      (node (ref "R47") (pin "1") (pinfunction "1_1") (pintype "passive"))
      (node (ref "SW1") (pin "C") (pinfunction "C_C") (pintype "bidirectional"))
      (node (ref "SW1") (pin "D") (pinfunction "D_D") (pintype "bidirectional"))
    )
    (net (code "60") (name "IR_IN") (class "Default")
      (node (ref "J7") (pin "3") (pinfunction "3_3") (pintype "bidirectional"))
      (node (ref "PICO1") (pin "GP6") (pinfunction "GP6_GP6") (pintype "bidirectional"))
    )
    (net (code "61") (name "IR_LED_CATHODE") (class "Default")
      (node (ref "J6") (pin "2") (pinfunction "2_2") (pintype "bidirectional"))
      (node (ref "Q27") (pin "1") (pinfunction "C_1_1") (pintype "bidirectional"))
      (node (ref "Q27") (pin "2") (pinfunction "C_2_2") (pintype "bidirectional"))
      (node (ref "Q27") (pin "5") (pinfunction "C_3_5") (pintype "bidirectional"))
      (node (ref "Q27") (pin "6") (pinfunction "C_4_6") (pintype "bidirectional"))
    )
    (net (code "62") (name "IR_OUT") (class "Default")
      (node (ref "PICO1") (pin "GP0") (pinfunction "GP0_GP0") (pintype "bidirectional"))
      (node (ref "R30") (pin "2") (pinfunction "2_2") (pintype "passive"))
    )
    (net (code "63") (name "JOYSTICK_BUTTON") (class "Default")
      (node (ref "J19") (pin "1") (pinfunction "1_1") (pintype "passive"))
      (node (ref "PICO1") (pin "GP27_A1") (pinfunction "GP27_A1_GP27_A1") (pintype "bidirectional"))
    )
    (net (code "64") (name "JOYSTICK_X") (class "Default")
      (node (ref "IC32") (pin "6") (pinfunction "AIN2_6") (pintype "bidirectional"))
      (node (ref "J19") (pin "3") (pinfunction "3_3") (pintype "passive"))
    )
    (net (code "65") (name "JOYSTICK_Y") (class "Default")
      (node (ref "IC32") (pin "5") (pinfunction "AIN1_5") (pintype "bidirectional"))
      (node (ref "J19") (pin "2") (pinfunction "2_2") (pintype "passive"))
    )
    (net (code "66") (name "LAMP1") (class "Default")
      (node (ref "IC23") (pin "20") (pinfunction "1C_20") (pintype "bidirectional"))
      (node (ref "J3") (pin "3") (pinfunction "3_3") (pintype "bidirectional"))
    )
    (net (code "67") (name "LAMP2") (class "Default")
      (node (ref "IC23") (pin "19") (pinfunction "2C_19") (pintype "bidirectional"))
      (node (ref "J3") (pin "4") (pinfunction "4_4") (pintype "bidirectional"))
    )
    (net (code "68") (name "LAMP3") (class "Default")
      (node (ref "IC23") (pin "18") (pinfunction "3C_18") (pintype "bidirectional"))
      (node (ref "J3") (pin "5") (pinfunction "5_5") (pintype "bidirectional"))
    )
    (net (code "69") (name "LAMP4") (class "Default")
      (node (ref "IC23") (pin "17") (pinfunction "4C_17") (pintype "bidirectional"))
      (node (ref "J3") (pin "6") (pinfunction "6_6") (pintype "bidirectional"))
    )
    (net (code "70") (name "LAMP5") (class "Default")
      (node (ref "IC23") (pin "16") (pinfunction "5C_16") (pintype "bidirectional"))
      (node (ref "J3") (pin "7") (pinfunction "7_7") (pintype "bidirectional"))
    )
    (net (code "71") (name "LAMP6") (class "Default")
      (node (ref "IC23") (pin "15") (pinfunction "6C_15") (pintype "bidirectional"))
      (node (ref "J3") (pin "8") (pinfunction "8_8") (pintype "bidirectional"))
    )
    (net (code "72") (name "LAMP7") (class "Default")
      (node (ref "IC23") (pin "14") (pinfunction "7C_14") (pintype "bidirectional"))
      (node (ref "J3") (pin "9") (pinfunction "9_9") (pintype "bidirectional"))
    )
    (net (code "73") (name "LAMP8") (class "Default")
      (node (ref "IC23") (pin "13") (pinfunction "8C_13") (pintype "bidirectional"))
      (node (ref "J3") (pin "10") (pinfunction "10_10") (pintype "bidirectional"))
    )
    (net (code "74") (name "LED1") (class "Default")
      (node (ref "IC18") (pin "22") (pinfunction "~{OUT15}_22") (pintype "bidirectional"))
      (node (ref "J4") (pin "1") (pinfunction "1_1") (pintype "bidirectional"))
    )
    (net (code "75") (name "LED2") (class "Default")
      (node (ref "IC18") (pin "21") (pinfunction "~{OUT14}_21") (pintype "bidirectional"))
      (node (ref "J4") (pin "2") (pinfunction "2_2") (pintype "bidirectional"))
    )
    (net (code "76") (name "LED3") (class "Default")
      (node (ref "IC18") (pin "20") (pinfunction "~{OUT13}_20") (pintype "bidirectional"))
      (node (ref "J4") (pin "4") (pinfunction "4_4") (pintype "bidirectional"))
    )
    (net (code "77") (name "LED4") (class "Default")
      (node (ref "IC18") (pin "19") (pinfunction "~{OUT12}_19") (pintype "bidirectional"))
      (node (ref "J4") (pin "5") (pinfunction "5_5") (pintype "bidirectional"))
    )
    (net (code "78") (name "LED5") (class "Default")
      (node (ref "IC18") (pin "17") (pinfunction "~{OUT11}_17") (pintype "bidirectional"))
      (node (ref "J4") (pin "6") (pinfunction "6_6") (pintype "bidirectional"))
    )
    (net (code "79") (name "LED6") (class "Default")
      (node (ref "IC18") (pin "16") (pinfunction "~{OUT10}_16") (pintype "bidirectional"))
      (node (ref "J4") (pin "7") (pinfunction "7_7") (pintype "bidirectional"))
    )
    (net (code "80") (name "LED7") (class "Default")
      (node (ref "IC18") (pin "15") (pinfunction "~{OUT9}_15") (pintype "bidirectional"))
      (node (ref "J4") (pin "8") (pinfunction "8_8") (pintype "bidirectional"))
    )
    (net (code "81") (name "LED8") (class "Default")
      (node (ref "IC18") (pin "14") (pinfunction "~{OUT8}_14") (pintype "bidirectional"))
      (node (ref "J4") (pin "9") (pinfunction "9_9") (pintype "bidirectional"))
    )
    (net (code "82") (name "LED9") (class "Default")
      (node (ref "IC18") (pin "11") (pinfunction "~{OUT7}_11") (pintype "bidirectional"))
      (node (ref "J5") (pin "1") (pinfunction "1_1") (pintype "bidirectional"))
    )
    (net (code "83") (name "LED10") (class "Default")
      (node (ref "IC18") (pin "10") (pinfunction "~{OUT6}_10") (pintype "bidirectional"))
      (node (ref "J5") (pin "3") (pinfunction "3_3") (pintype "bidirectional"))
    )
    (net (code "84") (name "LED11") (class "Default")
      (node (ref "IC18") (pin "9") (pinfunction "~{OUT5}_9") (pintype "bidirectional"))
      (node (ref "J5") (pin "4") (pinfunction "4_4") (pintype "bidirectional"))
    )
    (net (code "85") (name "LED12") (class "Default")
      (node (ref "IC18") (pin "8") (pinfunction "~{OUT4}_8") (pintype "bidirectional"))
      (node (ref "J5") (pin "5") (pinfunction "5_5") (pintype "bidirectional"))
    )
    (net (code "86") (name "LED13") (class "Default")
      (node (ref "IC18") (pin "6") (pinfunction "~{OUT3}_6") (pintype "bidirectional"))
      (node (ref "J5") (pin "6") (pinfunction "6_6") (pintype "bidirectional"))
    )
    (net (code "87") (name "LED14") (class "Default")
      (node (ref "IC18") (pin "5") (pinfunction "~{OUT2}_5") (pintype "bidirectional"))
      (node (ref "J5") (pin "7") (pinfunction "7_7") (pintype "bidirectional"))
    )
    (net (code "88") (name "LED15") (class "Default")
      (node (ref "IC18") (pin "4") (pinfunction "~{OUT1}_4") (pintype "bidirectional"))
      (node (ref "J5") (pin "8") (pinfunction "8_8") (pintype "bidirectional"))
    )
    (net (code "89") (name "LED16") (class "Default")
      (node (ref "IC18") (pin "3") (pinfunction "~{OUT0}_3") (pintype "bidirectional"))
      (node (ref "J5") (pin "9") (pinfunction "9_9") (pintype "bidirectional"))
    )
    (net (code "90") (name "LED_B") (class "Default")
      (node (ref "PICO1") (pin "GP3") (pinfunction "GP3_GP3") (pintype "bidirectional"))
      (node (ref "R36") (pin "1") (pinfunction "1_1") (pintype "passive"))
    )
    (net (code "91") (name "LED_G") (class "Default")
      (node (ref "PICO1") (pin "GP2") (pinfunction "GP2_GP2") (pintype "bidirectional"))
      (node (ref "R37") (pin "1") (pinfunction "1_1") (pintype "passive"))
    )
    (net (code "92") (name "LED_R") (class "Default")
      (node (ref "PICO1") (pin "GP1") (pinfunction "GP1_GP1") (pintype "bidirectional"))
      (node (ref "R38") (pin "1") (pinfunction "1_1") (pintype "passive"))
    )
    (net (code "93") (name "MOTOR1") (class "Default")
      (node (ref "J13") (pin "1") (pinfunction "1_1") (pintype "bidirectional"))
      (node (ref "Q1") (pin "7") (pinfunction "D1_1_7") (pintype "bidirectional"))
      (node (ref "Q1") (pin "8") (pinfunction "D1_2_8") (pintype "bidirectional"))
      (node (ref "Q1") (pin "9") (pinfunction "D1_3_9") (pintype "bidirectional"))
    )
    (net (code "94") (name "MOTOR2") (class "Default")
      (node (ref "J13") (pin "3") (pinfunction "3_3") (pintype "bidirectional"))
      (node (ref "Q1") (pin "10") (pinfunction "D2_3_10") (pintype "bidirectional"))
      (node (ref "Q1") (pin "5") (pinfunction "D2_1_5") (pintype "bidirectional"))
      (node (ref "Q1") (pin "6") (pinfunction "D2_2_6") (pintype "bidirectional"))
    )
    (net (code "95") (name "MOTOR3") (class "Default")
      (node (ref "J13") (pin "4") (pinfunction "4_4") (pintype "bidirectional"))
      (node (ref "Q2") (pin "7") (pinfunction "D1_1_7") (pintype "bidirectional"))
      (node (ref "Q2") (pin "8") (pinfunction "D1_2_8") (pintype "bidirectional"))
      (node (ref "Q2") (pin "9") (pinfunction "D1_3_9") (pintype "bidirectional"))
    )
    (net (code "96") (name "MOTOR4") (class "Default")
      (node (ref "J13") (pin "5") (pinfunction "5_5") (pintype "bidirectional"))
      (node (ref "Q2") (pin "10") (pinfunction "D2_3_10") (pintype "bidirectional"))
      (node (ref "Q2") (pin "5") (pinfunction "D2_1_5") (pintype "bidirectional"))
      (node (ref "Q2") (pin "6") (pinfunction "D2_2_6") (pintype "bidirectional"))
    )
    (net (code "97") (name "Net-(BATT1-Pad+)") (class "Default")
      (node (ref "BATT1") (pin "+") (pinfunction "+_+") (pintype "bidirectional"))
      (node (ref "R49") (pin "2") (pinfunction "2_2") (pintype "passive"))
    )
    (net (code "98") (name "Net-(D1-A)") (class "Default")
      (node (ref "D1") (pin "2") (pinfunction "A_2") (pintype "bidirectional"))
      (node (ref "Q27") (pin "3") (pinfunction "B_3") (pintype "bidirectional"))
      (node (ref "R30") (pin "1") (pinfunction "1_1") (pintype "passive"))
    )
    (net (code "99") (name "Net-(D1-K)") (class "Default")
      (node (ref "D1") (pin "1") (pinfunction "K_1") (pintype "bidirectional"))
      (node (ref "D2") (pin "2") (pinfunction "A_2") (pintype "bidirectional"))
    )
    (net (code "100") (name "Net-(IC1-OUTA)") (class "Default")
      (node (ref "IC1") (pin "7") (pinfunction "OUTA_7") (pintype "bidirectional"))
      (node (ref "R1") (pin "2") (pinfunction "2_2") (pintype "passive"))
    )
    (net (code "101") (name "Net-(IC1-OUTB)") (class "Default")
      (node (ref "IC1") (pin "5") (pinfunction "OUTB_5") (pintype "bidirectional"))
      (node (ref "R2") (pin "2") (pinfunction "2_2") (pintype "passive"))
    )
    (net (code "102") (name "Net-(IC2-OUTA)") (class "Default")
      (node (ref "IC2") (pin "7") (pinfunction "OUTA_7") (pintype "bidirectional"))
      (node (ref "R3") (pin "2") (pinfunction "2_2") (pintype "passive"))
    )
    (net (code "103") (name "Net-(IC2-OUTB)") (class "Default")
      (node (ref "IC2") (pin "5") (pinfunction "OUTB_5") (pintype "bidirectional"))
      (node (ref "R4") (pin "2") (pinfunction "2_2") (pintype "passive"))
    )
    (net (code "104") (name "Net-(IC3-OUTA)") (class "Default")
      (node (ref "IC3") (pin "7") (pinfunction "OUTA_7") (pintype "bidirectional"))
      (node (ref "R5") (pin "2") (pinfunction "2_2") (pintype "passive"))
    )
    (net (code "105") (name "Net-(IC3-OUTB)") (class "Default")
      (node (ref "IC3") (pin "5") (pinfunction "OUTB_5") (pintype "bidirectional"))
      (node (ref "R6") (pin "2") (pinfunction "2_2") (pintype "passive"))
    )
    (net (code "106") (name "Net-(IC4-OUTA)") (class "Default")
      (node (ref "IC4") (pin "7") (pinfunction "OUTA_7") (pintype "bidirectional"))
      (node (ref "R7") (pin "2") (pinfunction "2_2") (pintype "passive"))
    )
    (net (code "107") (name "Net-(IC4-OUTB)") (class "Default")
      (node (ref "IC4") (pin "5") (pinfunction "OUTB_5") (pintype "bidirectional"))
      (node (ref "R8") (pin "2") (pinfunction "2_2") (pintype "passive"))
    )
    (net (code "108") (name "Net-(IC5-OUTA)") (class "Default")
      (node (ref "IC5") (pin "7") (pinfunction "OUTA_7") (pintype "bidirectional"))
      (node (ref "R9") (pin "2") (pinfunction "2_2") (pintype "passive"))
    )
    (net (code "109") (name "Net-(IC5-OUTB)") (class "Default")
      (node (ref "IC5") (pin "5") (pinfunction "OUTB_5") (pintype "bidirectional"))
      (node (ref "R10") (pin "2") (pinfunction "2_2") (pintype "passive"))
    )
    (net (code "110") (name "Net-(IC6-OUTA)") (class "Default")
      (node (ref "IC6") (pin "7") (pinfunction "OUTA_7") (pintype "bidirectional"))
      (node (ref "R11") (pin "2") (pinfunction "2_2") (pintype "passive"))
    )
    (net (code "111") (name "Net-(IC6-OUTB)") (class "Default")
      (node (ref "IC6") (pin "5") (pinfunction "OUTB_5") (pintype "bidirectional"))
      (node (ref "R12") (pin "2") (pinfunction "2_2") (pintype "passive"))
    )
    (net (code "112") (name "Net-(IC7-OUTA)") (class "Default")
      (node (ref "IC7") (pin "7") (pinfunction "OUTA_7") (pintype "bidirectional"))
      (node (ref "R13") (pin "2") (pinfunction "2_2") (pintype "passive"))
    )
    (net (code "113") (name "Net-(IC7-OUTB)") (class "Default")
      (node (ref "IC7") (pin "5") (pinfunction "OUTB_5") (pintype "bidirectional"))
      (node (ref "R14") (pin "2") (pinfunction "2_2") (pintype "passive"))
    )
    (net (code "114") (name "Net-(IC8-OUTA)") (class "Default")
      (node (ref "IC8") (pin "7") (pinfunction "OUTA_7") (pintype "bidirectional"))
      (node (ref "R15") (pin "2") (pinfunction "2_2") (pintype "passive"))
    )
    (net (code "115") (name "Net-(IC8-OUTB)") (class "Default")
      (node (ref "IC8") (pin "5") (pinfunction "OUTB_5") (pintype "bidirectional"))
      (node (ref "R16") (pin "2") (pinfunction "2_2") (pintype "passive"))
    )
    (net (code "116") (name "Net-(IC9-OUTA)") (class "Default")
      (node (ref "IC9") (pin "7") (pinfunction "OUTA_7") (pintype "bidirectional"))
      (node (ref "R17") (pin "2") (pinfunction "2_2") (pintype "passive"))
    )
    (net (code "117") (name "Net-(IC9-OUTB)") (class "Default")
      (node (ref "IC9") (pin "5") (pinfunction "OUTB_5") (pintype "bidirectional"))
      (node (ref "R18") (pin "2") (pinfunction "2_2") (pintype "passive"))
    )
    (net (code "118") (name "Net-(IC10-OUTA)") (class "Default")
      (node (ref "IC10") (pin "7") (pinfunction "OUTA_7") (pintype "bidirectional"))
      (node (ref "R19") (pin "2") (pinfunction "2_2") (pintype "passive"))
    )
    (net (code "119") (name "Net-(IC10-OUTB)") (class "Default")
      (node (ref "IC10") (pin "5") (pinfunction "OUTB_5") (pintype "bidirectional"))
      (node (ref "R20") (pin "2") (pinfunction "2_2") (pintype "passive"))
    )
    (net (code "120") (name "Net-(IC11-OUTA)") (class "Default")
      (node (ref "IC11") (pin "7") (pinfunction "OUTA_7") (pintype "bidirectional"))
      (node (ref "R21") (pin "2") (pinfunction "2_2") (pintype "passive"))
    )
    (net (code "121") (name "Net-(IC11-OUTB)") (class "Default")
      (node (ref "IC11") (pin "5") (pinfunction "OUTB_5") (pintype "bidirectional"))
      (node (ref "R22") (pin "2") (pinfunction "2_2") (pintype "passive"))
    )
    (net (code "122") (name "Net-(IC12-OUTA)") (class "Default")
      (node (ref "IC12") (pin "7") (pinfunction "OUTA_7") (pintype "bidirectional"))
      (node (ref "R23") (pin "2") (pinfunction "2_2") (pintype "passive"))
    )
    (net (code "123") (name "Net-(IC12-OUTB)") (class "Default")
      (node (ref "IC12") (pin "5") (pinfunction "OUTB_5") (pintype "bidirectional"))
      (node (ref "R24") (pin "2") (pinfunction "2_2") (pintype "passive"))
    )
    (net (code "124") (name "Net-(IC13-OUTA)") (class "Default")
      (node (ref "IC13") (pin "7") (pinfunction "OUTA_7") (pintype "bidirectional"))
      (node (ref "R25") (pin "2") (pinfunction "2_2") (pintype "passive"))
    )
    (net (code "125") (name "Net-(IC13-OUTB)") (class "Default")
      (node (ref "IC13") (pin "5") (pinfunction "OUTB_5") (pintype "bidirectional"))
      (node (ref "R26") (pin "2") (pinfunction "2_2") (pintype "passive"))
    )
    (net (code "126") (name "Net-(IC14-OUTA)") (class "Default")
      (node (ref "IC14") (pin "7") (pinfunction "OUTA_7") (pintype "bidirectional"))
      (node (ref "R27") (pin "2") (pinfunction "2_2") (pintype "passive"))
    )
    (net (code "127") (name "Net-(IC14-OUTB)") (class "Default")
      (node (ref "IC14") (pin "5") (pinfunction "OUTB_5") (pintype "bidirectional"))
      (node (ref "R28") (pin "2") (pinfunction "2_2") (pintype "passive"))
    )
    (net (code "128") (name "Net-(IC15-~{RESET})") (class "Default")
      (node (ref "IC15") (pin "24") (pinfunction "~{RESET}_24") (pintype "bidirectional"))
      (node (ref "R39") (pin "1") (pinfunction "1_1") (pintype "passive"))
    )
    (net (code "129") (name "Net-(IC16-~{RESET})") (class "Default")
      (node (ref "IC16") (pin "24") (pinfunction "~{RESET}_24") (pintype "bidirectional"))
      (node (ref "R42") (pin "1") (pinfunction "1_1") (pintype "passive"))
    )
    (net (code "130") (name "Net-(IC17-~{RESET})") (class "Default")
      (node (ref "IC17") (pin "24") (pinfunction "~{RESET}_24") (pintype "bidirectional"))
      (node (ref "R43") (pin "1") (pinfunction "1_1") (pintype "passive"))
    )
    (net (code "131") (name "Net-(IC18-~{RESET})") (class "Default")
      (node (ref "IC18") (pin "24") (pinfunction "~{RESET}_24") (pintype "bidirectional"))
      (node (ref "R44") (pin "1") (pinfunction "1_1") (pintype "passive"))
    )
    (net (code "132") (name "Net-(IC24-SER)") (class "Default")
      (node (ref "IC24") (pin "10") (pinfunction "SER_10") (pintype "bidirectional"))
      (node (ref "IC25") (pin "9") (pinfunction "QH_9") (pintype "bidirectional"))
    )
    (net (code "133") (name "Net-(IC25-SER)") (class "Default")
      (node (ref "IC25") (pin "10") (pinfunction "SER_10") (pintype "bidirectional"))
      (node (ref "IC26") (pin "9") (pinfunction "QH_9") (pintype "bidirectional"))
    )
    (net (code "134") (name "Net-(IC26-SER)") (class "Default")
      (node (ref "IC26") (pin "10") (pinfunction "SER_10") (pintype "bidirectional"))
      (node (ref "IC27") (pin "9") (pinfunction "QH_9") (pintype "bidirectional"))
    )
    (net (code "135") (name "Net-(IC29-CLK)") (class "Default")
      (node (ref "IC29") (pin "1") (pinfunction "CLK_1") (pintype "bidirectional"))
      (node (ref "IC31") (pin "7") (pinfunction "E_2_7") (pintype "bidirectional"))
      (node (ref "R32") (pin "2") (pinfunction "2_2") (pintype "passive"))
    )
    (net (code "136") (name "Net-(IC29-Q)") (class "Default")
      (node (ref "IC29") (pin "4") (pinfunction "Q_4") (pintype "bidirectional"))
      (node (ref "IC31") (pin "3") (pinfunction "A_2_3") (pintype "bidirectional"))
    )
    (net (code "137") (name "Net-(IC29-~{CLR})") (class "Default")
      (node (ref "IC29") (pin "6") (pinfunction "~{CLR}_6") (pintype "bidirectional"))
      (node (ref "IC30") (pin "2") (pinfunction "~{RESET}_2") (pintype "output"))
    )
    (net (code "138") (name "Net-(IC31-K_1)") (class "Default")
      (node (ref "IC31") (pin "2") (pinfunction "K_1_2") (pintype "bidirectional"))
      (node (ref "R35") (pin "1") (pinfunction "1_1") (pintype "passive"))
    )
    (net (code "139") (name "Net-(IC31-K_2)") (class "Default")
      (node (ref "IC31") (pin "4") (pinfunction "K_2_4") (pintype "bidirectional"))
      (node (ref "R34") (pin "1") (pinfunction "1_1") (pintype "passive"))
    )
    (net (code "140") (name "Net-(IC32-AIN3)") (class "Default")
      (node (ref "IC32") (pin "7") (pinfunction "AIN3_7") (pintype "bidirectional"))
      (node (ref "R29") (pin "2") (pinfunction "2_2") (pintype "passive"))
      (node (ref "R45") (pin "2") (pinfunction "2_2") (pintype "passive"))
    )
    (net (code "141") (name "Net-(IC34-EVI)") (class "Default")
      (node (ref "IC34") (pin "4") (pinfunction "EVI_4") (pintype "bidirectional"))
      (node (ref "R46") (pin "2") (pinfunction "2_2") (pintype "passive"))
    )
    (net (code "142") (name "Net-(IC34-VBACKUP)") (class "Default")
      (node (ref "C41") (pin "1") (pinfunction "1_1") (pintype "passive"))
      (node (ref "IC34") (pin "1") (pinfunction "VBACKUP_1") (pintype "bidirectional"))
      (node (ref "R49") (pin "1") (pinfunction "1_1") (pintype "passive"))
    )
    (net (code "143") (name "Net-(LED1-Pad2)") (class "Default")
      (node (ref "LED1") (pin "2") (pinfunction "2_2") (pintype "bidirectional"))
      (node (ref "R36") (pin "2") (pinfunction "2_2") (pintype "passive"))
    )
    (net (code "144") (name "Net-(LED1-Pad3)") (class "Default")
      (node (ref "LED1") (pin "3") (pinfunction "3_3") (pintype "bidirectional"))
      (node (ref "R38") (pin "2") (pinfunction "2_2") (pintype "passive"))
    )
    (net (code "145") (name "Net-(LED1-Pad4)") (class "Default")
      (node (ref "LED1") (pin "4") (pinfunction "4_4") (pintype "bidirectional"))
      (node (ref "R37") (pin "2") (pinfunction "2_2") (pintype "passive"))
    )
    (net (code "146") (name "Net-(LED2-K)") (class "Default")
      (node (ref "LED2") (pin "1") (pinfunction "K_1") (pintype "bidirectional"))
      (node (ref "R47") (pin "2") (pinfunction "2_2") (pintype "passive"))
    )
    (net (code "147") (name "Net-(PICO1-PadRUN)") (class "Default")
      (node (ref "PICO1") (pin "RUN") (pinfunction "RUN_RUN") (pintype "bidirectional"))
      (node (ref "SW1") (pin "A") (pinfunction "A_A") (pintype "bidirectional"))
      (node (ref "SW1") (pin "B") (pinfunction "B_B") (pintype "bidirectional"))
    )
    (net (code "148") (name "Net-(Q1-G1)") (class "Default")
      (node (ref "Q1") (pin "2") (pinfunction "G1_2") (pintype "bidirectional"))
      (node (ref "R1") (pin "1") (pinfunction "1_1") (pintype "passive"))
    )
    (net (code "149") (name "Net-(Q1-G2)") (class "Default")
      (node (ref "Q1") (pin "4") (pinfunction "G2_4") (pintype "bidirectional"))
      (node (ref "R2") (pin "1") (pinfunction "1_1") (pintype "passive"))
    )
    (net (code "150") (name "Net-(Q2-G1)") (class "Default")
      (node (ref "Q2") (pin "2") (pinfunction "G1_2") (pintype "bidirectional"))
      (node (ref "R3") (pin "1") (pinfunction "1_1") (pintype "passive"))
    )
    (net (code "151") (name "Net-(Q2-G2)") (class "Default")
      (node (ref "Q2") (pin "4") (pinfunction "G2_4") (pintype "bidirectional"))
      (node (ref "R4") (pin "1") (pinfunction "1_1") (pintype "passive"))
    )
    (net (code "152") (name "Net-(Q3-G1)") (class "Default")
      (node (ref "Q3") (pin "2") (pinfunction "G1_2") (pintype "bidirectional"))
      (node (ref "R5") (pin "1") (pinfunction "1_1") (pintype "passive"))
    )
    (net (code "153") (name "Net-(Q3-G2)") (class "Default")
      (node (ref "Q3") (pin "4") (pinfunction "G2_4") (pintype "bidirectional"))
      (node (ref "R6") (pin "1") (pinfunction "1_1") (pintype "passive"))
    )
    (net (code "154") (name "Net-(Q4-G1)") (class "Default")
      (node (ref "Q4") (pin "2") (pinfunction "G1_2") (pintype "bidirectional"))
      (node (ref "R7") (pin "1") (pinfunction "1_1") (pintype "passive"))
    )
    (net (code "155") (name "Net-(Q4-G2)") (class "Default")
      (node (ref "Q4") (pin "4") (pinfunction "G2_4") (pintype "bidirectional"))
      (node (ref "R8") (pin "1") (pinfunction "1_1") (pintype "passive"))
    )
    (net (code "156") (name "Net-(Q5-G1)") (class "Default")
      (node (ref "Q5") (pin "2") (pinfunction "G1_2") (pintype "bidirectional"))
      (node (ref "R9") (pin "1") (pinfunction "1_1") (pintype "passive"))
    )
    (net (code "157") (name "Net-(Q5-G2)") (class "Default")
      (node (ref "Q5") (pin "4") (pinfunction "G2_4") (pintype "bidirectional"))
      (node (ref "R10") (pin "1") (pinfunction "1_1") (pintype "passive"))
    )
    (net (code "158") (name "Net-(Q6-G1)") (class "Default")
      (node (ref "Q6") (pin "2") (pinfunction "G1_2") (pintype "bidirectional"))
      (node (ref "R11") (pin "1") (pinfunction "1_1") (pintype "passive"))
    )
    (net (code "159") (name "Net-(Q6-G2)") (class "Default")
      (node (ref "Q6") (pin "4") (pinfunction "G2_4") (pintype "bidirectional"))
      (node (ref "R12") (pin "1") (pinfunction "1_1") (pintype "passive"))
    )
    (net (code "160") (name "Net-(Q7-G1)") (class "Default")
      (node (ref "Q7") (pin "2") (pinfunction "G1_2") (pintype "bidirectional"))
      (node (ref "R13") (pin "1") (pinfunction "1_1") (pintype "passive"))
    )
    (net (code "161") (name "Net-(Q7-G2)") (class "Default")
      (node (ref "Q7") (pin "4") (pinfunction "G2_4") (pintype "bidirectional"))
      (node (ref "R14") (pin "1") (pinfunction "1_1") (pintype "passive"))
    )
    (net (code "162") (name "Net-(Q8-G1)") (class "Default")
      (node (ref "Q8") (pin "2") (pinfunction "G1_2") (pintype "bidirectional"))
      (node (ref "R15") (pin "1") (pinfunction "1_1") (pintype "passive"))
    )
    (net (code "163") (name "Net-(Q8-G2)") (class "Default")
      (node (ref "Q8") (pin "4") (pinfunction "G2_4") (pintype "bidirectional"))
      (node (ref "R16") (pin "1") (pinfunction "1_1") (pintype "passive"))
    )
    (net (code "164") (name "Net-(Q9-G1)") (class "Default")
      (node (ref "Q9") (pin "2") (pinfunction "G1_2") (pintype "bidirectional"))
      (node (ref "R17") (pin "1") (pinfunction "1_1") (pintype "passive"))
    )
    (net (code "165") (name "Net-(Q9-G2)") (class "Default")
      (node (ref "Q9") (pin "4") (pinfunction "G2_4") (pintype "bidirectional"))
      (node (ref "R18") (pin "1") (pinfunction "1_1") (pintype "passive"))
    )
    (net (code "166") (name "Net-(Q10-G1)") (class "Default")
      (node (ref "Q10") (pin "2") (pinfunction "G1_2") (pintype "bidirectional"))
      (node (ref "R19") (pin "1") (pinfunction "1_1") (pintype "passive"))
    )
    (net (code "167") (name "Net-(Q10-G2)") (class "Default")
      (node (ref "Q10") (pin "4") (pinfunction "G2_4") (pintype "bidirectional"))
      (node (ref "R20") (pin "1") (pinfunction "1_1") (pintype "passive"))
    )
    (net (code "168") (name "Net-(Q11-G1)") (class "Default")
      (node (ref "Q11") (pin "2") (pinfunction "G1_2") (pintype "bidirectional"))
      (node (ref "R21") (pin "1") (pinfunction "1_1") (pintype "passive"))
    )
    (net (code "169") (name "Net-(Q11-G2)") (class "Default")
      (node (ref "Q11") (pin "4") (pinfunction "G2_4") (pintype "bidirectional"))
      (node (ref "R22") (pin "1") (pinfunction "1_1") (pintype "passive"))
    )
    (net (code "170") (name "Net-(Q12-G1)") (class "Default")
      (node (ref "Q12") (pin "2") (pinfunction "G1_2") (pintype "bidirectional"))
      (node (ref "R23") (pin "1") (pinfunction "1_1") (pintype "passive"))
    )
    (net (code "171") (name "Net-(Q12-G2)") (class "Default")
      (node (ref "Q12") (pin "4") (pinfunction "G2_4") (pintype "bidirectional"))
      (node (ref "R24") (pin "1") (pinfunction "1_1") (pintype "passive"))
    )
    (net (code "172") (name "Net-(Q13-G1)") (class "Default")
      (node (ref "Q13") (pin "2") (pinfunction "G1_2") (pintype "bidirectional"))
      (node (ref "R25") (pin "1") (pinfunction "1_1") (pintype "passive"))
    )
    (net (code "173") (name "Net-(Q13-G2)") (class "Default")
      (node (ref "Q13") (pin "4") (pinfunction "G2_4") (pintype "bidirectional"))
      (node (ref "R26") (pin "1") (pinfunction "1_1") (pintype "passive"))
    )
    (net (code "174") (name "Net-(Q14-G1)") (class "Default")
      (node (ref "Q14") (pin "2") (pinfunction "G1_2") (pintype "bidirectional"))
      (node (ref "R27") (pin "1") (pinfunction "1_1") (pintype "passive"))
    )
    (net (code "175") (name "Net-(Q14-G2)") (class "Default")
      (node (ref "Q14") (pin "4") (pinfunction "G2_4") (pintype "bidirectional"))
      (node (ref "R28") (pin "1") (pinfunction "1_1") (pintype "passive"))
    )
    (net (code "176") (name "Net-(Q27-E)") (class "Default")
      (node (ref "Q27") (pin "4") (pinfunction "E_4") (pintype "bidirectional"))
      (node (ref "R31") (pin "2") (pinfunction "2_2") (pintype "passive"))
    )
    (net (code "177") (name "OUT1") (class "Default")
      (node (ref "J14") (pin "1") (pinfunction "1_1") (pintype "bidirectional"))
      (node (ref "Q3") (pin "7") (pinfunction "D1_1_7") (pintype "bidirectional"))
      (node (ref "Q3") (pin "8") (pinfunction "D1_2_8") (pintype "bidirectional"))
      (node (ref "Q3") (pin "9") (pinfunction "D1_3_9") (pintype "bidirectional"))
    )
    (net (code "178") (name "OUT2") (class "Default")
      (node (ref "J14") (pin "3") (pinfunction "3_3") (pintype "bidirectional"))
      (node (ref "Q3") (pin "10") (pinfunction "D2_3_10") (pintype "bidirectional"))
      (node (ref "Q3") (pin "5") (pinfunction "D2_1_5") (pintype "bidirectional"))
      (node (ref "Q3") (pin "6") (pinfunction "D2_2_6") (pintype "bidirectional"))
    )
    (net (code "179") (name "OUT3") (class "Default")
      (node (ref "J14") (pin "4") (pinfunction "4_4") (pintype "bidirectional"))
      (node (ref "Q4") (pin "7") (pinfunction "D1_1_7") (pintype "bidirectional"))
      (node (ref "Q4") (pin "8") (pinfunction "D1_2_8") (pintype "bidirectional"))
      (node (ref "Q4") (pin "9") (pinfunction "D1_3_9") (pintype "bidirectional"))
    )
    (net (code "180") (name "OUT4") (class "Default")
      (node (ref "J14") (pin "5") (pinfunction "5_5") (pintype "bidirectional"))
      (node (ref "Q4") (pin "10") (pinfunction "D2_3_10") (pintype "bidirectional"))
      (node (ref "Q4") (pin "5") (pinfunction "D2_1_5") (pintype "bidirectional"))
      (node (ref "Q4") (pin "6") (pinfunction "D2_2_6") (pintype "bidirectional"))
    )
    (net (code "181") (name "OUT5") (class "Default")
      (node (ref "J14") (pin "6") (pinfunction "6_6") (pintype "bidirectional"))
      (node (ref "Q5") (pin "7") (pinfunction "D1_1_7") (pintype "bidirectional"))
      (node (ref "Q5") (pin "8") (pinfunction "D1_2_8") (pintype "bidirectional"))
      (node (ref "Q5") (pin "9") (pinfunction "D1_3_9") (pintype "bidirectional"))
    )
    (net (code "182") (name "OUT6") (class "Default")
      (node (ref "J14") (pin "7") (pinfunction "7_7") (pintype "bidirectional"))
      (node (ref "Q5") (pin "10") (pinfunction "D2_3_10") (pintype "bidirectional"))
      (node (ref "Q5") (pin "5") (pinfunction "D2_1_5") (pintype "bidirectional"))
      (node (ref "Q5") (pin "6") (pinfunction "D2_2_6") (pintype "bidirectional"))
    )
    (net (code "183") (name "OUT7") (class "Default")
      (node (ref "J14") (pin "8") (pinfunction "8_8") (pintype "bidirectional"))
      (node (ref "Q6") (pin "7") (pinfunction "D1_1_7") (pintype "bidirectional"))
      (node (ref "Q6") (pin "8") (pinfunction "D1_2_8") (pintype "bidirectional"))
      (node (ref "Q6") (pin "9") (pinfunction "D1_3_9") (pintype "bidirectional"))
    )
    (net (code "184") (name "OUT8") (class "Default")
      (node (ref "J14") (pin "9") (pinfunction "9_9") (pintype "bidirectional"))
      (node (ref "Q6") (pin "10") (pinfunction "D2_3_10") (pintype "bidirectional"))
      (node (ref "Q6") (pin "5") (pinfunction "D2_1_5") (pintype "bidirectional"))
      (node (ref "Q6") (pin "6") (pinfunction "D2_2_6") (pintype "bidirectional"))
    )
    (net (code "185") (name "OUT9") (class "Default")
      (node (ref "J15") (pin "1") (pinfunction "1_1") (pintype "bidirectional"))
      (node (ref "Q7") (pin "7") (pinfunction "D1_1_7") (pintype "bidirectional"))
      (node (ref "Q7") (pin "8") (pinfunction "D1_2_8") (pintype "bidirectional"))
      (node (ref "Q7") (pin "9") (pinfunction "D1_3_9") (pintype "bidirectional"))
    )
    (net (code "186") (name "OUT10") (class "Default")
      (node (ref "J15") (pin "2") (pinfunction "2_2") (pintype "bidirectional"))
      (node (ref "Q7") (pin "10") (pinfunction "D2_3_10") (pintype "bidirectional"))
      (node (ref "Q7") (pin "5") (pinfunction "D2_1_5") (pintype "bidirectional"))
      (node (ref "Q7") (pin "6") (pinfunction "D2_2_6") (pintype "bidirectional"))
    )
    (net (code "187") (name "OUT11") (class "Default")
      (node (ref "J15") (pin "4") (pinfunction "4_4") (pintype "bidirectional"))
      (node (ref "Q8") (pin "7") (pinfunction "D1_1_7") (pintype "bidirectional"))
      (node (ref "Q8") (pin "8") (pinfunction "D1_2_8") (pintype "bidirectional"))
      (node (ref "Q8") (pin "9") (pinfunction "D1_3_9") (pintype "bidirectional"))
    )
    (net (code "188") (name "OUT12") (class "Default")
      (node (ref "J15") (pin "5") (pinfunction "5_5") (pintype "bidirectional"))
      (node (ref "Q8") (pin "10") (pinfunction "D2_3_10") (pintype "bidirectional"))
      (node (ref "Q8") (pin "5") (pinfunction "D2_1_5") (pintype "bidirectional"))
      (node (ref "Q8") (pin "6") (pinfunction "D2_2_6") (pintype "bidirectional"))
    )
    (net (code "189") (name "OUT13") (class "Default")
      (node (ref "J15") (pin "6") (pinfunction "6_6") (pintype "bidirectional"))
      (node (ref "Q9") (pin "7") (pinfunction "D1_1_7") (pintype "bidirectional"))
      (node (ref "Q9") (pin "8") (pinfunction "D1_2_8") (pintype "bidirectional"))
      (node (ref "Q9") (pin "9") (pinfunction "D1_3_9") (pintype "bidirectional"))
    )
    (net (code "190") (name "OUT14") (class "Default")
      (node (ref "J15") (pin "7") (pinfunction "7_7") (pintype "bidirectional"))
      (node (ref "Q9") (pin "10") (pinfunction "D2_3_10") (pintype "bidirectional"))
      (node (ref "Q9") (pin "5") (pinfunction "D2_1_5") (pintype "bidirectional"))
      (node (ref "Q9") (pin "6") (pinfunction "D2_2_6") (pintype "bidirectional"))
    )
    (net (code "191") (name "OUT15") (class "Default")
      (node (ref "J15") (pin "8") (pinfunction "8_8") (pintype "bidirectional"))
      (node (ref "Q10") (pin "7") (pinfunction "D1_1_7") (pintype "bidirectional"))
      (node (ref "Q10") (pin "8") (pinfunction "D1_2_8") (pintype "bidirectional"))
      (node (ref "Q10") (pin "9") (pinfunction "D1_3_9") (pintype "bidirectional"))
    )
    (net (code "192") (name "OUT16") (class "Default")
      (node (ref "J15") (pin "9") (pinfunction "9_9") (pintype "bidirectional"))
      (node (ref "Q10") (pin "10") (pinfunction "D2_3_10") (pintype "bidirectional"))
      (node (ref "Q10") (pin "5") (pinfunction "D2_1_5") (pintype "bidirectional"))
      (node (ref "Q10") (pin "6") (pinfunction "D2_2_6") (pintype "bidirectional"))
    )
    (net (code "193") (name "OUT17") (class "Default")
      (node (ref "J16") (pin "1") (pinfunction "1_1") (pintype "bidirectional"))
      (node (ref "Q11") (pin "7") (pinfunction "D1_1_7") (pintype "bidirectional"))
      (node (ref "Q11") (pin "8") (pinfunction "D1_2_8") (pintype "bidirectional"))
      (node (ref "Q11") (pin "9") (pinfunction "D1_3_9") (pintype "bidirectional"))
    )
    (net (code "194") (name "OUT18") (class "Default")
      (node (ref "J16") (pin "2") (pinfunction "2_2") (pintype "bidirectional"))
      (node (ref "Q11") (pin "10") (pinfunction "D2_3_10") (pintype "bidirectional"))
      (node (ref "Q11") (pin "5") (pinfunction "D2_1_5") (pintype "bidirectional"))
      (node (ref "Q11") (pin "6") (pinfunction "D2_2_6") (pintype "bidirectional"))
    )
    (net (code "195") (name "OUT19") (class "Default")
      (node (ref "J16") (pin "3") (pinfunction "3_3") (pintype "bidirectional"))
      (node (ref "Q12") (pin "7") (pinfunction "D1_1_7") (pintype "bidirectional"))
      (node (ref "Q12") (pin "8") (pinfunction "D1_2_8") (pintype "bidirectional"))
      (node (ref "Q12") (pin "9") (pinfunction "D1_3_9") (pintype "bidirectional"))
    )
    (net (code "196") (name "OUT20") (class "Default")
      (node (ref "J16") (pin "5") (pinfunction "5_5") (pintype "bidirectional"))
      (node (ref "Q12") (pin "10") (pinfunction "D2_3_10") (pintype "bidirectional"))
      (node (ref "Q12") (pin "5") (pinfunction "D2_1_5") (pintype "bidirectional"))
      (node (ref "Q12") (pin "6") (pinfunction "D2_2_6") (pintype "bidirectional"))
    )
    (net (code "197") (name "OUT21") (class "Default")
      (node (ref "J16") (pin "6") (pinfunction "6_6") (pintype "bidirectional"))
      (node (ref "Q13") (pin "7") (pinfunction "D1_1_7") (pintype "bidirectional"))
      (node (ref "Q13") (pin "8") (pinfunction "D1_2_8") (pintype "bidirectional"))
      (node (ref "Q13") (pin "9") (pinfunction "D1_3_9") (pintype "bidirectional"))
    )
    (net (code "198") (name "OUT22") (class "Default")
      (node (ref "J16") (pin "7") (pinfunction "7_7") (pintype "bidirectional"))
      (node (ref "Q13") (pin "10") (pinfunction "D2_3_10") (pintype "bidirectional"))
      (node (ref "Q13") (pin "5") (pinfunction "D2_1_5") (pintype "bidirectional"))
      (node (ref "Q13") (pin "6") (pinfunction "D2_2_6") (pintype "bidirectional"))
    )
    (net (code "199") (name "OUT23") (class "Default")
      (node (ref "J16") (pin "8") (pinfunction "8_8") (pintype "bidirectional"))
      (node (ref "Q14") (pin "7") (pinfunction "D1_1_7") (pintype "bidirectional"))
      (node (ref "Q14") (pin "8") (pinfunction "D1_2_8") (pintype "bidirectional"))
      (node (ref "Q14") (pin "9") (pinfunction "D1_3_9") (pintype "bidirectional"))
    )
    (net (code "200") (name "OUT24") (class "Default")
      (node (ref "J16") (pin "9") (pinfunction "9_9") (pintype "bidirectional"))
      (node (ref "Q14") (pin "10") (pinfunction "D2_3_10") (pintype "bidirectional"))
      (node (ref "Q14") (pin "5") (pinfunction "D2_1_5") (pintype "bidirectional"))
      (node (ref "Q14") (pin "6") (pinfunction "D2_2_6") (pintype "bidirectional"))
    )
    (net (code "201") (name "OUTCTL25") (class "Default")
      (node (ref "IC20") (pin "7") (pinfunction "7B_7") (pintype "bidirectional"))
      (node (ref "IC20") (pin "8") (pinfunction "8B_8") (pintype "bidirectional"))
      (node (ref "Q18") (pin "4") (pinfunction "C2_4") (pintype "bidirectional"))
    )
    (net (code "202") (name "OUTCTL26") (class "Default")
      (node (ref "IC20") (pin "5") (pinfunction "5B_5") (pintype "bidirectional"))
      (node (ref "IC20") (pin "6") (pinfunction "6B_6") (pintype "bidirectional"))
      (node (ref "Q18") (pin "5") (pinfunction "C1_5") (pintype "bidirectional"))
    )
    (net (code "203") (name "OUTCTL27") (class "Default")
      (node (ref "IC20") (pin "3") (pinfunction "3B_3") (pintype "bidirectional"))
      (node (ref "IC20") (pin "4") (pinfunction "4B_4") (pintype "bidirectional"))
      (node (ref "Q17") (pin "4") (pinfunction "C2_4") (pintype "bidirectional"))
    )
    (net (code "204") (name "OUTCTL28") (class "Default")
      (node (ref "IC20") (pin "1") (pinfunction "1B_1") (pintype "bidirectional"))
      (node (ref "IC20") (pin "2") (pinfunction "2B_2") (pintype "bidirectional"))
      (node (ref "Q17") (pin "5") (pinfunction "C1_5") (pintype "bidirectional"))
    )
    (net (code "205") (name "OUTCTL29") (class "Default")
      (node (ref "IC19") (pin "7") (pinfunction "7B_7") (pintype "bidirectional"))
      (node (ref "IC19") (pin "8") (pinfunction "8B_8") (pintype "bidirectional"))
      (node (ref "Q16") (pin "4") (pinfunction "C2_4") (pintype "bidirectional"))
    )
    (net (code "206") (name "OUTCTL30") (class "Default")
      (node (ref "IC19") (pin "5") (pinfunction "5B_5") (pintype "bidirectional"))
      (node (ref "IC19") (pin "6") (pinfunction "6B_6") (pintype "bidirectional"))
      (node (ref "Q16") (pin "5") (pinfunction "C1_5") (pintype "bidirectional"))
    )
    (net (code "207") (name "OUTCTL31") (class "Default")
      (node (ref "IC19") (pin "3") (pinfunction "3B_3") (pintype "bidirectional"))
      (node (ref "IC19") (pin "4") (pinfunction "4B_4") (pintype "bidirectional"))
      (node (ref "Q15") (pin "4") (pinfunction "C2_4") (pintype "bidirectional"))
    )
    (net (code "208") (name "OUTCTL32") (class "Default")
      (node (ref "IC19") (pin "1") (pinfunction "1B_1") (pintype "bidirectional"))
      (node (ref "IC19") (pin "2") (pinfunction "2B_2") (pintype "bidirectional"))
      (node (ref "Q15") (pin "5") (pinfunction "C1_5") (pintype "bidirectional"))
    )
    (net (code "209") (name "OUTCTL33") (class "Default")
      (node (ref "IC22") (pin "7") (pinfunction "7B_7") (pintype "bidirectional"))
      (node (ref "IC22") (pin "8") (pinfunction "8B_8") (pintype "bidirectional"))
      (node (ref "Q22") (pin "4") (pinfunction "C2_4") (pintype "bidirectional"))
    )
    (net (code "210") (name "OUTCTL34") (class "Default")
      (node (ref "IC22") (pin "5") (pinfunction "5B_5") (pintype "bidirectional"))
      (node (ref "IC22") (pin "6") (pinfunction "6B_6") (pintype "bidirectional"))
      (node (ref "Q22") (pin "5") (pinfunction "C1_5") (pintype "bidirectional"))
    )
    (net (code "211") (name "OUTCTL35") (class "Default")
      (node (ref "IC22") (pin "3") (pinfunction "3B_3") (pintype "bidirectional"))
      (node (ref "IC22") (pin "4") (pinfunction "4B_4") (pintype "bidirectional"))
      (node (ref "Q21") (pin "4") (pinfunction "C2_4") (pintype "bidirectional"))
    )
    (net (code "212") (name "OUTCTL36") (class "Default")
      (node (ref "IC22") (pin "1") (pinfunction "1B_1") (pintype "bidirectional"))
      (node (ref "IC22") (pin "2") (pinfunction "2B_2") (pintype "bidirectional"))
      (node (ref "Q21") (pin "5") (pinfunction "C1_5") (pintype "bidirectional"))
    )
    (net (code "213") (name "OUTCTL37") (class "Default")
      (node (ref "IC21") (pin "7") (pinfunction "7B_7") (pintype "bidirectional"))
      (node (ref "IC21") (pin "8") (pinfunction "8B_8") (pintype "bidirectional"))
      (node (ref "Q20") (pin "4") (pinfunction "C2_4") (pintype "bidirectional"))
    )
    (net (code "214") (name "OUTCTL38") (class "Default")
      (node (ref "IC21") (pin "5") (pinfunction "5B_5") (pintype "bidirectional"))
      (node (ref "IC21") (pin "6") (pinfunction "6B_6") (pintype "bidirectional"))
      (node (ref "Q20") (pin "5") (pinfunction "C1_5") (pintype "bidirectional"))
    )
    (net (code "215") (name "OUTCTL39") (class "Default")
      (node (ref "IC21") (pin "3") (pinfunction "3B_3") (pintype "bidirectional"))
      (node (ref "IC21") (pin "4") (pinfunction "4B_4") (pintype "bidirectional"))
      (node (ref "Q19") (pin "4") (pinfunction "C2_4") (pintype "bidirectional"))
    )
    (net (code "216") (name "OUTCTL40") (class "Default")
      (node (ref "IC21") (pin "1") (pinfunction "1B_1") (pintype "bidirectional"))
      (node (ref "IC21") (pin "2") (pinfunction "2B_2") (pintype "bidirectional"))
      (node (ref "Q19") (pin "5") (pinfunction "C1_5") (pintype "bidirectional"))
    )
    (net (code "217") (name "OUTCTL41") (class "Default")
      (node (ref "IC23") (pin "8") (pinfunction "8B_8") (pintype "bidirectional"))
      (node (ref "Q26") (pin "4") (pinfunction "C2_4") (pintype "bidirectional"))
    )
    (net (code "218") (name "OUTCTL42") (class "Default")
      (node (ref "IC23") (pin "7") (pinfunction "7B_7") (pintype "bidirectional"))
      (node (ref "Q26") (pin "5") (pinfunction "C1_5") (pintype "bidirectional"))
    )
    (net (code "219") (name "OUTCTL43") (class "Default")
      (node (ref "IC23") (pin "6") (pinfunction "6B_6") (pintype "bidirectional"))
      (node (ref "Q25") (pin "4") (pinfunction "C2_4") (pintype "bidirectional"))
    )
    (net (code "220") (name "OUTCTL44") (class "Default")
      (node (ref "IC23") (pin "5") (pinfunction "5B_5") (pintype "bidirectional"))
      (node (ref "Q25") (pin "5") (pinfunction "C1_5") (pintype "bidirectional"))
    )
    (net (code "221") (name "OUTCTL45") (class "Default")
      (node (ref "IC23") (pin "4") (pinfunction "4B_4") (pintype "bidirectional"))
      (node (ref "Q24") (pin "4") (pinfunction "C2_4") (pintype "bidirectional"))
    )
    (net (code "222") (name "OUTCTL46") (class "Default")
      (node (ref "IC23") (pin "3") (pinfunction "3B_3") (pintype "bidirectional"))
      (node (ref "Q24") (pin "5") (pinfunction "C1_5") (pintype "bidirectional"))
    )
    (net (code "223") (name "OUTCTL47") (class "Default")
      (node (ref "IC23") (pin "2") (pinfunction "2B_2") (pintype "bidirectional"))
      (node (ref "Q23") (pin "4") (pinfunction "C2_4") (pintype "bidirectional"))
    )
    (net (code "224") (name "OUTCTL48") (class "Default")
      (node (ref "IC23") (pin "1") (pinfunction "1B_1") (pintype "bidirectional"))
      (node (ref "Q23") (pin "5") (pinfunction "C1_5") (pintype "bidirectional"))
    )
    (net (code "225") (name "PLUNGER_ADC") (class "Default")
      (node (ref "IC32") (pin "4") (pinfunction "AIN0_4") (pintype "bidirectional"))
      (node (ref "J8") (pin "8") (pinfunction "8_8") (pintype "bidirectional"))
      (node (ref "PICO1") (pin "GP28_A2") (pinfunction "GP28_A2_GP28_A2") (pintype "bidirectional"))
    )
    (net (code "226") (name "PLUNGER_IRQ1_SCL") (class "Default")
      (node (ref "J8") (pin "6") (pinfunction "6_6") (pintype "bidirectional"))
      (node (ref "PICO1") (pin "GP11") (pinfunction "GP11_GP11") (pintype "bidirectional"))
    )
    (net (code "227") (name "PLUNGER_IRQ2") (class "Default")
      (node (ref "J8") (pin "5") (pinfunction "5_5") (pintype "bidirectional"))
      (node (ref "PICO1") (pin "GP13") (pinfunction "GP13_GP13") (pintype "bidirectional"))
    )
    (net (code "228") (name "PLUNGER_SDA") (class "Default")
      (node (ref "J8") (pin "1") (pinfunction "1_1") (pintype "bidirectional"))
      (node (ref "PICO1") (pin "GP10") (pinfunction "GP10_GP10") (pintype "bidirectional"))
    )
    (net (code "229") (name "PSU2_STATUS_SENSE") (class "Default")
      (node (ref "IC31") (pin "5") (pinfunction "E_1_5") (pintype "bidirectional"))
      (node (ref "PICO1") (pin "GP19") (pinfunction "GP19_GP19") (pintype "bidirectional"))
      (node (ref "R33") (pin "2") (pinfunction "2_2") (pintype "passive"))
    )
    (net (code "230") (name "PSU2_STATUS_SET") (class "Default")
      (node (ref "IC31") (pin "1") (pinfunction "A_1_1") (pintype "bidirectional"))
      (node (ref "PICO1") (pin "GP20") (pinfunction "GP20_GP20") (pintype "bidirectional"))
    )
    (net (code "231") (name "SCL") (class "Default")
      (node (ref "IC15") (pin "25") (pinfunction "SCL_25") (pintype "bidirectional"))
      (node (ref "IC16") (pin "25") (pinfunction "SCL_25") (pintype "bidirectional"))
      (node (ref "IC17") (pin "25") (pinfunction "SCL_25") (pintype "bidirectional"))
      (node (ref "IC18") (pin "25") (pinfunction "SCL_25") (pintype "bidirectional"))
      (node (ref "IC28") (pin "4") (pinfunction "SCL/SPC_4") (pintype "bidirectional"))
      (node (ref "IC32") (pin "10") (pinfunction "SCL_10") (pintype "bidirectional"))
      (node (ref "IC34") (pin "8") (pinfunction "SCL_8") (pintype "bidirectional"))
      (node (ref "PICO1") (pin "GP5") (pinfunction "GP5_GP5") (pintype "bidirectional"))
      (node (ref "R40") (pin "1") (pinfunction "1_1") (pintype "passive"))
    )
    (net (code "232") (name "SDA") (class "Default")
      (node (ref "IC15") (pin "26") (pinfunction "SDA_26") (pintype "bidirectional"))
      (node (ref "IC16") (pin "26") (pinfunction "SDA_26") (pintype "bidirectional"))
      (node (ref "IC17") (pin "26") (pinfunction "SDA_26") (pintype "bidirectional"))
      (node (ref "IC18") (pin "26") (pinfunction "SDA_26") (pintype "bidirectional"))
      (node (ref "IC28") (pin "6") (pinfunction "SDA/SDI/SDO_6") (pintype "bidirectional"))
      (node (ref "IC32") (pin "9") (pinfunction "SDA_9") (pintype "bidirectional"))
      (node (ref "IC34") (pin "2") (pinfunction "SDA_2") (pintype "bidirectional"))
      (node (ref "PICO1") (pin "GP4") (pinfunction "GP4_GP4") (pintype "bidirectional"))
      (node (ref "R41") (pin "1") (pinfunction "1_1") (pintype "passive"))
    )
    (net (code "233") (name "UART0_RX") (class "Default")
      (node (ref "J17") (pin "3") (pinfunction "3_3") (pintype "passive"))
      (node (ref "PICO1") (pin "GP17") (pinfunction "GP17_GP17") (pintype "bidirectional"))
    )
    (net (code "234") (name "UART0_TX") (class "Default")
      (node (ref "J17") (pin "1") (pinfunction "1_1") (pintype "passive"))
      (node (ref "PICO1") (pin "GP16") (pinfunction "GP16_GP16") (pintype "bidirectional"))
    )
    (net (code "235") (name "VBUS") (class "Default")
      (node (ref "C38") (pin "1") (pinfunction "1_1") (pintype "passive"))
      (node (ref "IC33") (pin "1") (pinfunction "IN_1") (pintype "power_in"))
      (node (ref "PICO1") (pin "VBUS") (pinfunction "VBUS_VBUS") (pintype "bidirectional"))
    )
    (net (code "236") (name "unconnected-(IC15-N.C._1-Pad12)") (class "Default")
      (node (ref "IC15") (pin "12") (pinfunction "N.C._1_12") (pintype "bidirectional"))
    )
    (net (code "237") (name "unconnected-(IC15-N.C._2-Pad28)") (class "Default")
      (node (ref "IC15") (pin "28") (pinfunction "N.C._2_28") (pintype "bidirectional"))
    )
    (net (code "238") (name "unconnected-(IC15-N.C._3-Pad29)") (class "Default")
      (node (ref "IC15") (pin "29") (pinfunction "N.C._3_29") (pintype "bidirectional"))
    )
    (net (code "239") (name "unconnected-(IC15-N.C._4-Pad30)") (class "Default")
      (node (ref "IC15") (pin "30") (pinfunction "N.C._4_30") (pintype "bidirectional"))
    )
    (net (code "240") (name "unconnected-(IC15-~{N.C.}-Pad13)") (class "Default")
      (node (ref "IC15") (pin "13") (pinfunction "~{N.C.}_13") (pintype "bidirectional"))
    )
    (net (code "241") (name "unconnected-(IC16-N.C._1-Pad12)") (class "Default")
      (node (ref "IC16") (pin "12") (pinfunction "N.C._1_12") (pintype "bidirectional"))
    )
    (net (code "242") (name "unconnected-(IC16-N.C._2-Pad28)") (class "Default")
      (node (ref "IC16") (pin "28") (pinfunction "N.C._2_28") (pintype "bidirectional"))
    )
    (net (code "243") (name "unconnected-(IC16-N.C._3-Pad29)") (class "Default")
      (node (ref "IC16") (pin "29") (pinfunction "N.C._3_29") (pintype "bidirectional"))
    )
    (net (code "244") (name "unconnected-(IC16-N.C._4-Pad30)") (class "Default")
      (node (ref "IC16") (pin "30") (pinfunction "N.C._4_30") (pintype "bidirectional"))
    )
    (net (code "245") (name "unconnected-(IC16-~{N.C.}-Pad13)") (class "Default")
      (node (ref "IC16") (pin "13") (pinfunction "~{N.C.}_13") (pintype "bidirectional"))
    )
    (net (code "246") (name "unconnected-(IC17-N.C._1-Pad12)") (class "Default")
      (node (ref "IC17") (pin "12") (pinfunction "N.C._1_12") (pintype "bidirectional"))
    )
    (net (code "247") (name "unconnected-(IC17-N.C._2-Pad28)") (class "Default")
      (node (ref "IC17") (pin "28") (pinfunction "N.C._2_28") (pintype "bidirectional"))
    )
    (net (code "248") (name "unconnected-(IC17-N.C._3-Pad29)") (class "Default")
      (node (ref "IC17") (pin "29") (pinfunction "N.C._3_29") (pintype "bidirectional"))
    )
    (net (code "249") (name "unconnected-(IC17-N.C._4-Pad30)") (class "Default")
      (node (ref "IC17") (pin "30") (pinfunction "N.C._4_30") (pintype "bidirectional"))
    )
    (net (code "250") (name "unconnected-(IC17-~{N.C.}-Pad13)") (class "Default")
      (node (ref "IC17") (pin "13") (pinfunction "~{N.C.}_13") (pintype "bidirectional"))
    )
    (net (code "251") (name "unconnected-(IC18-N.C._1-Pad12)") (class "Default")
      (node (ref "IC18") (pin "12") (pinfunction "N.C._1_12") (pintype "bidirectional"))
    )
    (net (code "252") (name "unconnected-(IC18-N.C._2-Pad28)") (class "Default")
      (node (ref "IC18") (pin "28") (pinfunction "N.C._2_28") (pintype "bidirectional"))
    )
    (net (code "253") (name "unconnected-(IC18-N.C._3-Pad29)") (class "Default")
      (node (ref "IC18") (pin "29") (pinfunction "N.C._3_29") (pintype "bidirectional"))
    )
    (net (code "254") (name "unconnected-(IC18-N.C._4-Pad30)") (class "Default")
      (node (ref "IC18") (pin "30") (pinfunction "N.C._4_30") (pintype "bidirectional"))
    )
    (net (code "255") (name "unconnected-(IC18-~{N.C.}-Pad13)") (class "Default")
      (node (ref "IC18") (pin "13") (pinfunction "~{N.C.}_13") (pintype "bidirectional"))
    )
    (net (code "256") (name "unconnected-(IC19-COM-Pad12)") (class "Default")
      (node (ref "IC19") (pin "12") (pinfunction "COM_12") (pintype "bidirectional"))
    )
    (net (code "257") (name "unconnected-(IC19-NC_1-Pad10)") (class "Default")
      (node (ref "IC19") (pin "10") (pinfunction "NC_1_10") (pintype "bidirectional"))
    )
    (net (code "258") (name "unconnected-(IC19-NC_2-Pad11)") (class "Default")
      (node (ref "IC19") (pin "11") (pinfunction "NC_2_11") (pintype "bidirectional"))
    )
    (net (code "259") (name "unconnected-(IC20-COM-Pad12)") (class "Default")
      (node (ref "IC20") (pin "12") (pinfunction "COM_12") (pintype "bidirectional"))
    )
    (net (code "260") (name "unconnected-(IC20-NC_1-Pad10)") (class "Default")
      (node (ref "IC20") (pin "10") (pinfunction "NC_1_10") (pintype "bidirectional"))
    )
    (net (code "261") (name "unconnected-(IC20-NC_2-Pad11)") (class "Default")
      (node (ref "IC20") (pin "11") (pinfunction "NC_2_11") (pintype "bidirectional"))
    )
    (net (code "262") (name "unconnected-(IC21-COM-Pad12)") (class "Default")
      (node (ref "IC21") (pin "12") (pinfunction "COM_12") (pintype "bidirectional"))
    )
    (net (code "263") (name "unconnected-(IC21-NC_1-Pad10)") (class "Default")
      (node (ref "IC21") (pin "10") (pinfunction "NC_1_10") (pintype "bidirectional"))
    )
    (net (code "264") (name "unconnected-(IC21-NC_2-Pad11)") (class "Default")
      (node (ref "IC21") (pin "11") (pinfunction "NC_2_11") (pintype "bidirectional"))
    )
    (net (code "265") (name "unconnected-(IC22-COM-Pad12)") (class "Default")
      (node (ref "IC22") (pin "12") (pinfunction "COM_12") (pintype "bidirectional"))
    )
    (net (code "266") (name "unconnected-(IC22-NC_1-Pad10)") (class "Default")
      (node (ref "IC22") (pin "10") (pinfunction "NC_1_10") (pintype "bidirectional"))
    )
    (net (code "267") (name "unconnected-(IC22-NC_2-Pad11)") (class "Default")
      (node (ref "IC22") (pin "11") (pinfunction "NC_2_11") (pintype "bidirectional"))
    )
    (net (code "268") (name "unconnected-(IC23-COM-Pad12)") (class "Default")
      (node (ref "IC23") (pin "12") (pinfunction "COM_12") (pintype "bidirectional"))
    )
    (net (code "269") (name "unconnected-(IC23-NC_1-Pad10)") (class "Default")
      (node (ref "IC23") (pin "10") (pinfunction "NC_1_10") (pintype "bidirectional"))
    )
    (net (code "270") (name "unconnected-(IC23-NC_2-Pad11)") (class "Default")
      (node (ref "IC23") (pin "11") (pinfunction "NC_2_11") (pintype "bidirectional"))
    )
    (net (code "271") (name "unconnected-(IC24-~{QH}-Pad7)") (class "Default")
      (node (ref "IC24") (pin "7") (pinfunction "~{QH}_7") (pintype "bidirectional"))
    )
    (net (code "272") (name "unconnected-(IC25-~{QH}-Pad7)") (class "Default")
      (node (ref "IC25") (pin "7") (pinfunction "~{QH}_7") (pintype "bidirectional"))
    )
    (net (code "273") (name "unconnected-(IC26-~{QH}-Pad7)") (class "Default")
      (node (ref "IC26") (pin "7") (pinfunction "~{QH}_7") (pintype "bidirectional"))
    )
    (net (code "274") (name "unconnected-(IC27-SER-Pad10)") (class "Default")
      (node (ref "IC27") (pin "10") (pinfunction "SER_10") (pintype "bidirectional"))
    )
    (net (code "275") (name "unconnected-(IC27-~{QH}-Pad7)") (class "Default")
      (node (ref "IC27") (pin "7") (pinfunction "~{QH}_7") (pintype "bidirectional"))
    )
    (net (code "276") (name "unconnected-(IC28-INT2-Pad9)") (class "Default")
      (node (ref "IC28") (pin "9") (pinfunction "INT2_9") (pintype "input"))
    )
    (net (code "277") (name "unconnected-(IC28-NC_1-Pad2)") (class "Default")
      (node (ref "IC28") (pin "2") (pinfunction "NC_1_2") (pintype "bidirectional"))
    )
    (net (code "278") (name "unconnected-(IC28-NC_2-Pad3)") (class "Default")
      (node (ref "IC28") (pin "3") (pinfunction "NC_2_3") (pintype "bidirectional"))
    )
    (net (code "279") (name "unconnected-(IC33-NC-Pad4)") (class "Default")
      (node (ref "IC33") (pin "4") (pinfunction "NC_4") (pintype "no_connect"))
    )
    (net (code "280") (name "unconnected-(IC34-CLKOUT-Pad7)") (class "Default")
      (node (ref "IC34") (pin "7") (pinfunction "CLKOUT_7") (pintype "bidirectional"))
    )
    (net (code "281") (name "unconnected-(IC34-~{INT}-Pad3)") (class "Default")
      (node (ref "IC34") (pin "3") (pinfunction "~{INT}_3") (pintype "bidirectional"))
    )
    (net (code "282") (name "unconnected-(J3-Pad2)") (class "Default")
      (node (ref "J3") (pin "2") (pinfunction "2_2") (pintype "bidirectional"))
    )
    (net (code "283") (name "unconnected-(J4-Pad3)") (class "Default")
      (node (ref "J4") (pin "3") (pinfunction "3_3") (pintype "bidirectional"))
    )
    (net (code "284") (name "unconnected-(J5-Pad2)") (class "Default")
      (node (ref "J5") (pin "2") (pinfunction "2_2") (pintype "bidirectional"))
    )
    (net (code "285") (name "unconnected-(J8-Pad7)") (class "Default")
      (node (ref "J8") (pin "7") (pinfunction "7_7") (pintype "bidirectional"))
    )
    (net (code "286") (name "unconnected-(J9-Pad3)") (class "Default")
      (node (ref "J9") (pin "3") (pinfunction "3_3") (pintype "bidirectional"))
    )
    (net (code "287") (name "unconnected-(J10-Pad4)") (class "Default")
      (node (ref "J10") (pin "4") (pinfunction "4_4") (pintype "bidirectional"))
    )
    (net (code "288") (name "unconnected-(J11-Pad5)") (class "Default")
      (node (ref "J11") (pin "5") (pinfunction "5_5") (pintype "bidirectional"))
    )
    (net (code "289") (name "unconnected-(J12-Pad6)") (class "Default")
      (node (ref "J12") (pin "6") (pinfunction "6_6") (pintype "bidirectional"))
    )
    (net (code "290") (name "unconnected-(J13-Pad2)") (class "Default")
      (node (ref "J13") (pin "2") (pinfunction "2_2") (pintype "bidirectional"))
    )
    (net (code "291") (name "unconnected-(J14-Pad2)") (class "Default")
      (node (ref "J14") (pin "2") (pinfunction "2_2") (pintype "bidirectional"))
    )
    (net (code "292") (name "unconnected-(J15-Pad3)") (class "Default")
      (node (ref "J15") (pin "3") (pinfunction "3_3") (pintype "bidirectional"))
    )
    (net (code "293") (name "unconnected-(J16-Pad4)") (class "Default")
      (node (ref "J16") (pin "4") (pinfunction "4_4") (pintype "bidirectional"))
    )
    (net (code "294") (name "unconnected-(J19-Pad4)") (class "Default")
      (node (ref "J19") (pin "4") (pinfunction "4_4") (pintype "passive"))
    )
    (net (code "295") (name "unconnected-(PICO1-Pad3V3_EN)") (class "Default")
      (node (ref "PICO1") (pin "3V3_EN") (pinfunction "3V3_EN_3V3_EN") (pintype "bidirectional"))
    )
    (net (code "296") (name "unconnected-(PICO1-PadADC_VREF)") (class "Default")
      (node (ref "PICO1") (pin "ADC_VREF") (pinfunction "ADC_VREF_ADC_VREF") (pintype "bidirectional"))
    )
    (net (code "297") (name "unconnected-(PICO1-PadVSYS)") (class "Default")
      (node (ref "PICO1") (pin "VSYS") (pinfunction "VSYS_VSYS") (pintype "bidirectional"))
    )
    (net (code "298") (name "{slash}MOTORCTL1") (class "Default")
      (node (ref "IC1") (pin "2") (pinfunction "INA_2") (pintype "bidirectional"))
      (node (ref "PICO1") (pin "GP8") (pinfunction "GP8_GP8") (pintype "bidirectional"))
    )
    (net (code "299") (name "{slash}MOTORCTL2") (class "Default")
      (node (ref "IC1") (pin "4") (pinfunction "INB_4") (pintype "bidirectional"))
      (node (ref "PICO1") (pin "GP9") (pinfunction "GP9_GP9") (pintype "bidirectional"))
    )
    (net (code "300") (name "{slash}MOTORCTL3") (class "Default")
      (node (ref "IC2") (pin "2") (pinfunction "INA_2") (pintype "bidirectional"))
      (node (ref "PICO1") (pin "GP14") (pinfunction "GP14_GP14") (pintype "bidirectional"))
    )
    (net (code "301") (name "{slash}MOTORCTL4") (class "Default")
      (node (ref "IC2") (pin "4") (pinfunction "INB_4") (pintype "bidirectional"))
      (node (ref "PICO1") (pin "GP15") (pinfunction "GP15_GP15") (pintype "bidirectional"))
    )
    (net (code "302") (name "{slash}OUTCTL1") (class "Default")
      (node (ref "IC15") (pin "22") (pinfunction "~{OUT15}_22") (pintype "bidirectional"))
      (node (ref "IC3") (pin "2") (pinfunction "INA_2") (pintype "bidirectional"))
    )
    (net (code "303") (name "{slash}OUTCTL2") (class "Default")
      (node (ref "IC15") (pin "21") (pinfunction "~{OUT14}_21") (pintype "bidirectional"))
      (node (ref "IC3") (pin "4") (pinfunction "INB_4") (pintype "bidirectional"))
    )
    (net (code "304") (name "{slash}OUTCTL3") (class "Default")
      (node (ref "IC15") (pin "20") (pinfunction "~{OUT13}_20") (pintype "bidirectional"))
      (node (ref "IC4") (pin "2") (pinfunction "INA_2") (pintype "bidirectional"))
    )
    (net (code "305") (name "{slash}OUTCTL4") (class "Default")
      (node (ref "IC15") (pin "19") (pinfunction "~{OUT12}_19") (pintype "bidirectional"))
      (node (ref "IC4") (pin "4") (pinfunction "INB_4") (pintype "bidirectional"))
    )
    (net (code "306") (name "{slash}OUTCTL5") (class "Default")
      (node (ref "IC15") (pin "17") (pinfunction "~{OUT11}_17") (pintype "bidirectional"))
      (node (ref "IC5") (pin "2") (pinfunction "INA_2") (pintype "bidirectional"))
    )
    (net (code "307") (name "{slash}OUTCTL6") (class "Default")
      (node (ref "IC15") (pin "16") (pinfunction "~{OUT10}_16") (pintype "bidirectional"))
      (node (ref "IC5") (pin "4") (pinfunction "INB_4") (pintype "bidirectional"))
    )
    (net (code "308") (name "{slash}OUTCTL7") (class "Default")
      (node (ref "IC15") (pin "15") (pinfunction "~{OUT9}_15") (pintype "bidirectional"))
      (node (ref "IC6") (pin "2") (pinfunction "INA_2") (pintype "bidirectional"))
    )
    (net (code "309") (name "{slash}OUTCTL8") (class "Default")
      (node (ref "IC15") (pin "14") (pinfunction "~{OUT8}_14") (pintype "bidirectional"))
      (node (ref "IC6") (pin "4") (pinfunction "INB_4") (pintype "bidirectional"))
    )
    (net (code "310") (name "{slash}OUTCTL9") (class "Default")
      (node (ref "IC15") (pin "11") (pinfunction "~{OUT7}_11") (pintype "bidirectional"))
      (node (ref "IC7") (pin "2") (pinfunction "INA_2") (pintype "bidirectional"))
    )
    (net (code "311") (name "{slash}OUTCTL10") (class "Default")
      (node (ref "IC15") (pin "10") (pinfunction "~{OUT6}_10") (pintype "bidirectional"))
      (node (ref "IC7") (pin "4") (pinfunction "INB_4") (pintype "bidirectional"))
    )
    (net (code "312") (name "{slash}OUTCTL11") (class "Default")
      (node (ref "IC15") (pin "9") (pinfunction "~{OUT5}_9") (pintype "bidirectional"))
      (node (ref "IC8") (pin "2") (pinfunction "INA_2") (pintype "bidirectional"))
    )
    (net (code "313") (name "{slash}OUTCTL12") (class "Default")
      (node (ref "IC15") (pin "8") (pinfunction "~{OUT4}_8") (pintype "bidirectional"))
      (node (ref "IC8") (pin "4") (pinfunction "INB_4") (pintype "bidirectional"))
    )
    (net (code "314") (name "{slash}OUTCTL13") (class "Default")
      (node (ref "IC15") (pin "6") (pinfunction "~{OUT3}_6") (pintype "bidirectional"))
      (node (ref "IC9") (pin "2") (pinfunction "INA_2") (pintype "bidirectional"))
    )
    (net (code "315") (name "{slash}OUTCTL14") (class "Default")
      (node (ref "IC15") (pin "5") (pinfunction "~{OUT2}_5") (pintype "bidirectional"))
      (node (ref "IC9") (pin "4") (pinfunction "INB_4") (pintype "bidirectional"))
    )
    (net (code "316") (name "{slash}OUTCTL15") (class "Default")
      (node (ref "IC10") (pin "2") (pinfunction "INA_2") (pintype "bidirectional"))
      (node (ref "IC15") (pin "4") (pinfunction "~{OUT1}_4") (pintype "bidirectional"))
    )
    (net (code "317") (name "{slash}OUTCTL16") (class "Default")
      (node (ref "IC10") (pin "4") (pinfunction "INB_4") (pintype "bidirectional"))
      (node (ref "IC15") (pin "3") (pinfunction "~{OUT0}_3") (pintype "bidirectional"))
    )
    (net (code "318") (name "{slash}OUTCTL17") (class "Default")
      (node (ref "IC11") (pin "2") (pinfunction "INA_2") (pintype "bidirectional"))
      (node (ref "IC16") (pin "22") (pinfunction "~{OUT15}_22") (pintype "bidirectional"))
    )
    (net (code "319") (name "{slash}OUTCTL18") (class "Default")
      (node (ref "IC11") (pin "4") (pinfunction "INB_4") (pintype "bidirectional"))
      (node (ref "IC16") (pin "21") (pinfunction "~{OUT14}_21") (pintype "bidirectional"))
    )
    (net (code "320") (name "{slash}OUTCTL19") (class "Default")
      (node (ref "IC12") (pin "2") (pinfunction "INA_2") (pintype "bidirectional"))
      (node (ref "IC16") (pin "20") (pinfunction "~{OUT13}_20") (pintype "bidirectional"))
    )
    (net (code "321") (name "{slash}OUTCTL20") (class "Default")
      (node (ref "IC12") (pin "4") (pinfunction "INB_4") (pintype "bidirectional"))
      (node (ref "IC16") (pin "19") (pinfunction "~{OUT12}_19") (pintype "bidirectional"))
    )
    (net (code "322") (name "{slash}OUTCTL21") (class "Default")
      (node (ref "IC13") (pin "2") (pinfunction "INA_2") (pintype "bidirectional"))
      (node (ref "IC16") (pin "17") (pinfunction "~{OUT11}_17") (pintype "bidirectional"))
    )
    (net (code "323") (name "{slash}OUTCTL22") (class "Default")
      (node (ref "IC13") (pin "4") (pinfunction "INB_4") (pintype "bidirectional"))
      (node (ref "IC16") (pin "16") (pinfunction "~{OUT10}_16") (pintype "bidirectional"))
    )
    (net (code "324") (name "{slash}OUTCTL23") (class "Default")
      (node (ref "IC14") (pin "2") (pinfunction "INA_2") (pintype "bidirectional"))
      (node (ref "IC16") (pin "15") (pinfunction "~{OUT9}_15") (pintype "bidirectional"))
    )
    (net (code "325") (name "{slash}OUTCTL24") (class "Default")
      (node (ref "IC14") (pin "4") (pinfunction "INB_4") (pintype "bidirectional"))
      (node (ref "IC16") (pin "14") (pinfunction "~{OUT8}_14") (pintype "bidirectional"))
    )
    (net (code "326") (name "{slash}OUTCTL25") (class "Default")
      (node (ref "IC16") (pin "3") (pinfunction "~{OUT0}_3") (pintype "bidirectional"))
      (node (ref "Q18") (pin "3") (pinfunction "B2_3") (pintype "bidirectional"))
    )
    (net (code "327") (name "{slash}OUTCTL26") (class "Default")
      (node (ref "IC16") (pin "4") (pinfunction "~{OUT1}_4") (pintype "bidirectional"))
      (node (ref "Q18") (pin "1") (pinfunction "B1_1") (pintype "bidirectional"))
    )
    (net (code "328") (name "{slash}OUTCTL27") (class "Default")
      (node (ref "IC16") (pin "5") (pinfunction "~{OUT2}_5") (pintype "bidirectional"))
      (node (ref "Q17") (pin "3") (pinfunction "B2_3") (pintype "bidirectional"))
    )
    (net (code "329") (name "{slash}OUTCTL28") (class "Default")
      (node (ref "IC16") (pin "6") (pinfunction "~{OUT3}_6") (pintype "bidirectional"))
      (node (ref "Q17") (pin "1") (pinfunction "B1_1") (pintype "bidirectional"))
    )
    (net (code "330") (name "{slash}OUTCTL29") (class "Default")
      (node (ref "IC16") (pin "8") (pinfunction "~{OUT4}_8") (pintype "bidirectional"))
      (node (ref "Q16") (pin "3") (pinfunction "B2_3") (pintype "bidirectional"))
    )
    (net (code "331") (name "{slash}OUTCTL30") (class "Default")
      (node (ref "IC16") (pin "9") (pinfunction "~{OUT5}_9") (pintype "bidirectional"))
      (node (ref "Q16") (pin "1") (pinfunction "B1_1") (pintype "bidirectional"))
    )
    (net (code "332") (name "{slash}OUTCTL31") (class "Default")
      (node (ref "IC16") (pin "10") (pinfunction "~{OUT6}_10") (pintype "bidirectional"))
      (node (ref "Q15") (pin "3") (pinfunction "B2_3") (pintype "bidirectional"))
    )
    (net (code "333") (name "{slash}OUTCTL32") (class "Default")
      (node (ref "IC16") (pin "11") (pinfunction "~{OUT7}_11") (pintype "bidirectional"))
      (node (ref "Q15") (pin "1") (pinfunction "B1_1") (pintype "bidirectional"))
    )
    (net (code "334") (name "{slash}OUTCTL33") (class "Default")
      (node (ref "IC17") (pin "14") (pinfunction "~{OUT8}_14") (pintype "bidirectional"))
      (node (ref "Q22") (pin "3") (pinfunction "B2_3") (pintype "bidirectional"))
    )
    (net (code "335") (name "{slash}OUTCTL34") (class "Default")
      (node (ref "IC17") (pin "15") (pinfunction "~{OUT9}_15") (pintype "bidirectional"))
      (node (ref "Q22") (pin "1") (pinfunction "B1_1") (pintype "bidirectional"))
    )
    (net (code "336") (name "{slash}OUTCTL35") (class "Default")
      (node (ref "IC17") (pin "16") (pinfunction "~{OUT10}_16") (pintype "bidirectional"))
      (node (ref "Q21") (pin "3") (pinfunction "B2_3") (pintype "bidirectional"))
    )
    (net (code "337") (name "{slash}OUTCTL36") (class "Default")
      (node (ref "IC17") (pin "17") (pinfunction "~{OUT11}_17") (pintype "bidirectional"))
      (node (ref "Q21") (pin "1") (pinfunction "B1_1") (pintype "bidirectional"))
    )
    (net (code "338") (name "{slash}OUTCTL37") (class "Default")
      (node (ref "IC17") (pin "19") (pinfunction "~{OUT12}_19") (pintype "bidirectional"))
      (node (ref "Q20") (pin "3") (pinfunction "B2_3") (pintype "bidirectional"))
    )
    (net (code "339") (name "{slash}OUTCTL38") (class "Default")
      (node (ref "IC17") (pin "20") (pinfunction "~{OUT13}_20") (pintype "bidirectional"))
      (node (ref "Q20") (pin "1") (pinfunction "B1_1") (pintype "bidirectional"))
    )
    (net (code "340") (name "{slash}OUTCTL39") (class "Default")
      (node (ref "IC17") (pin "21") (pinfunction "~{OUT14}_21") (pintype "bidirectional"))
      (node (ref "Q19") (pin "3") (pinfunction "B2_3") (pintype "bidirectional"))
    )
    (net (code "341") (name "{slash}OUTCTL40") (class "Default")
      (node (ref "IC17") (pin "22") (pinfunction "~{OUT15}_22") (pintype "bidirectional"))
      (node (ref "Q19") (pin "1") (pinfunction "B1_1") (pintype "bidirectional"))
    )
    (net (code "342") (name "{slash}OUTCTL41") (class "Default")
      (node (ref "IC17") (pin "3") (pinfunction "~{OUT0}_3") (pintype "bidirectional"))
      (node (ref "Q26") (pin "3") (pinfunction "B2_3") (pintype "bidirectional"))
    )
    (net (code "343") (name "{slash}OUTCTL42") (class "Default")
      (node (ref "IC17") (pin "4") (pinfunction "~{OUT1}_4") (pintype "bidirectional"))
      (node (ref "Q26") (pin "1") (pinfunction "B1_1") (pintype "bidirectional"))
    )
    (net (code "344") (name "{slash}OUTCTL43") (class "Default")
      (node (ref "IC17") (pin "5") (pinfunction "~{OUT2}_5") (pintype "bidirectional"))
      (node (ref "Q25") (pin "3") (pinfunction "B2_3") (pintype "bidirectional"))
    )
    (net (code "345") (name "{slash}OUTCTL44") (class "Default")
      (node (ref "IC17") (pin "6") (pinfunction "~{OUT3}_6") (pintype "bidirectional"))
      (node (ref "Q25") (pin "1") (pinfunction "B1_1") (pintype "bidirectional"))
    )
    (net (code "346") (name "{slash}OUTCTL45") (class "Default")
      (node (ref "IC17") (pin "8") (pinfunction "~{OUT4}_8") (pintype "bidirectional"))
      (node (ref "Q24") (pin "3") (pinfunction "B2_3") (pintype "bidirectional"))
    )
    (net (code "347") (name "{slash}OUTCTL46") (class "Default")
      (node (ref "IC17") (pin "9") (pinfunction "~{OUT5}_9") (pintype "bidirectional"))
      (node (ref "Q24") (pin "1") (pinfunction "B1_1") (pintype "bidirectional"))
    )
    (net (code "348") (name "{slash}OUTCTL47") (class "Default")
      (node (ref "IC17") (pin "10") (pinfunction "~{OUT6}_10") (pintype "bidirectional"))
      (node (ref "Q23") (pin "3") (pinfunction "B2_3") (pintype "bidirectional"))
    )
    (net (code "349") (name "{slash}OUTCTL48") (class "Default")
      (node (ref "IC17") (pin "11") (pinfunction "~{OUT7}_11") (pintype "bidirectional"))
      (node (ref "Q23") (pin "1") (pinfunction "B1_1") (pintype "bidirectional"))
    )
  )
)
